# dt.net
KiCad netlist of a schematic drawn in EAGLE
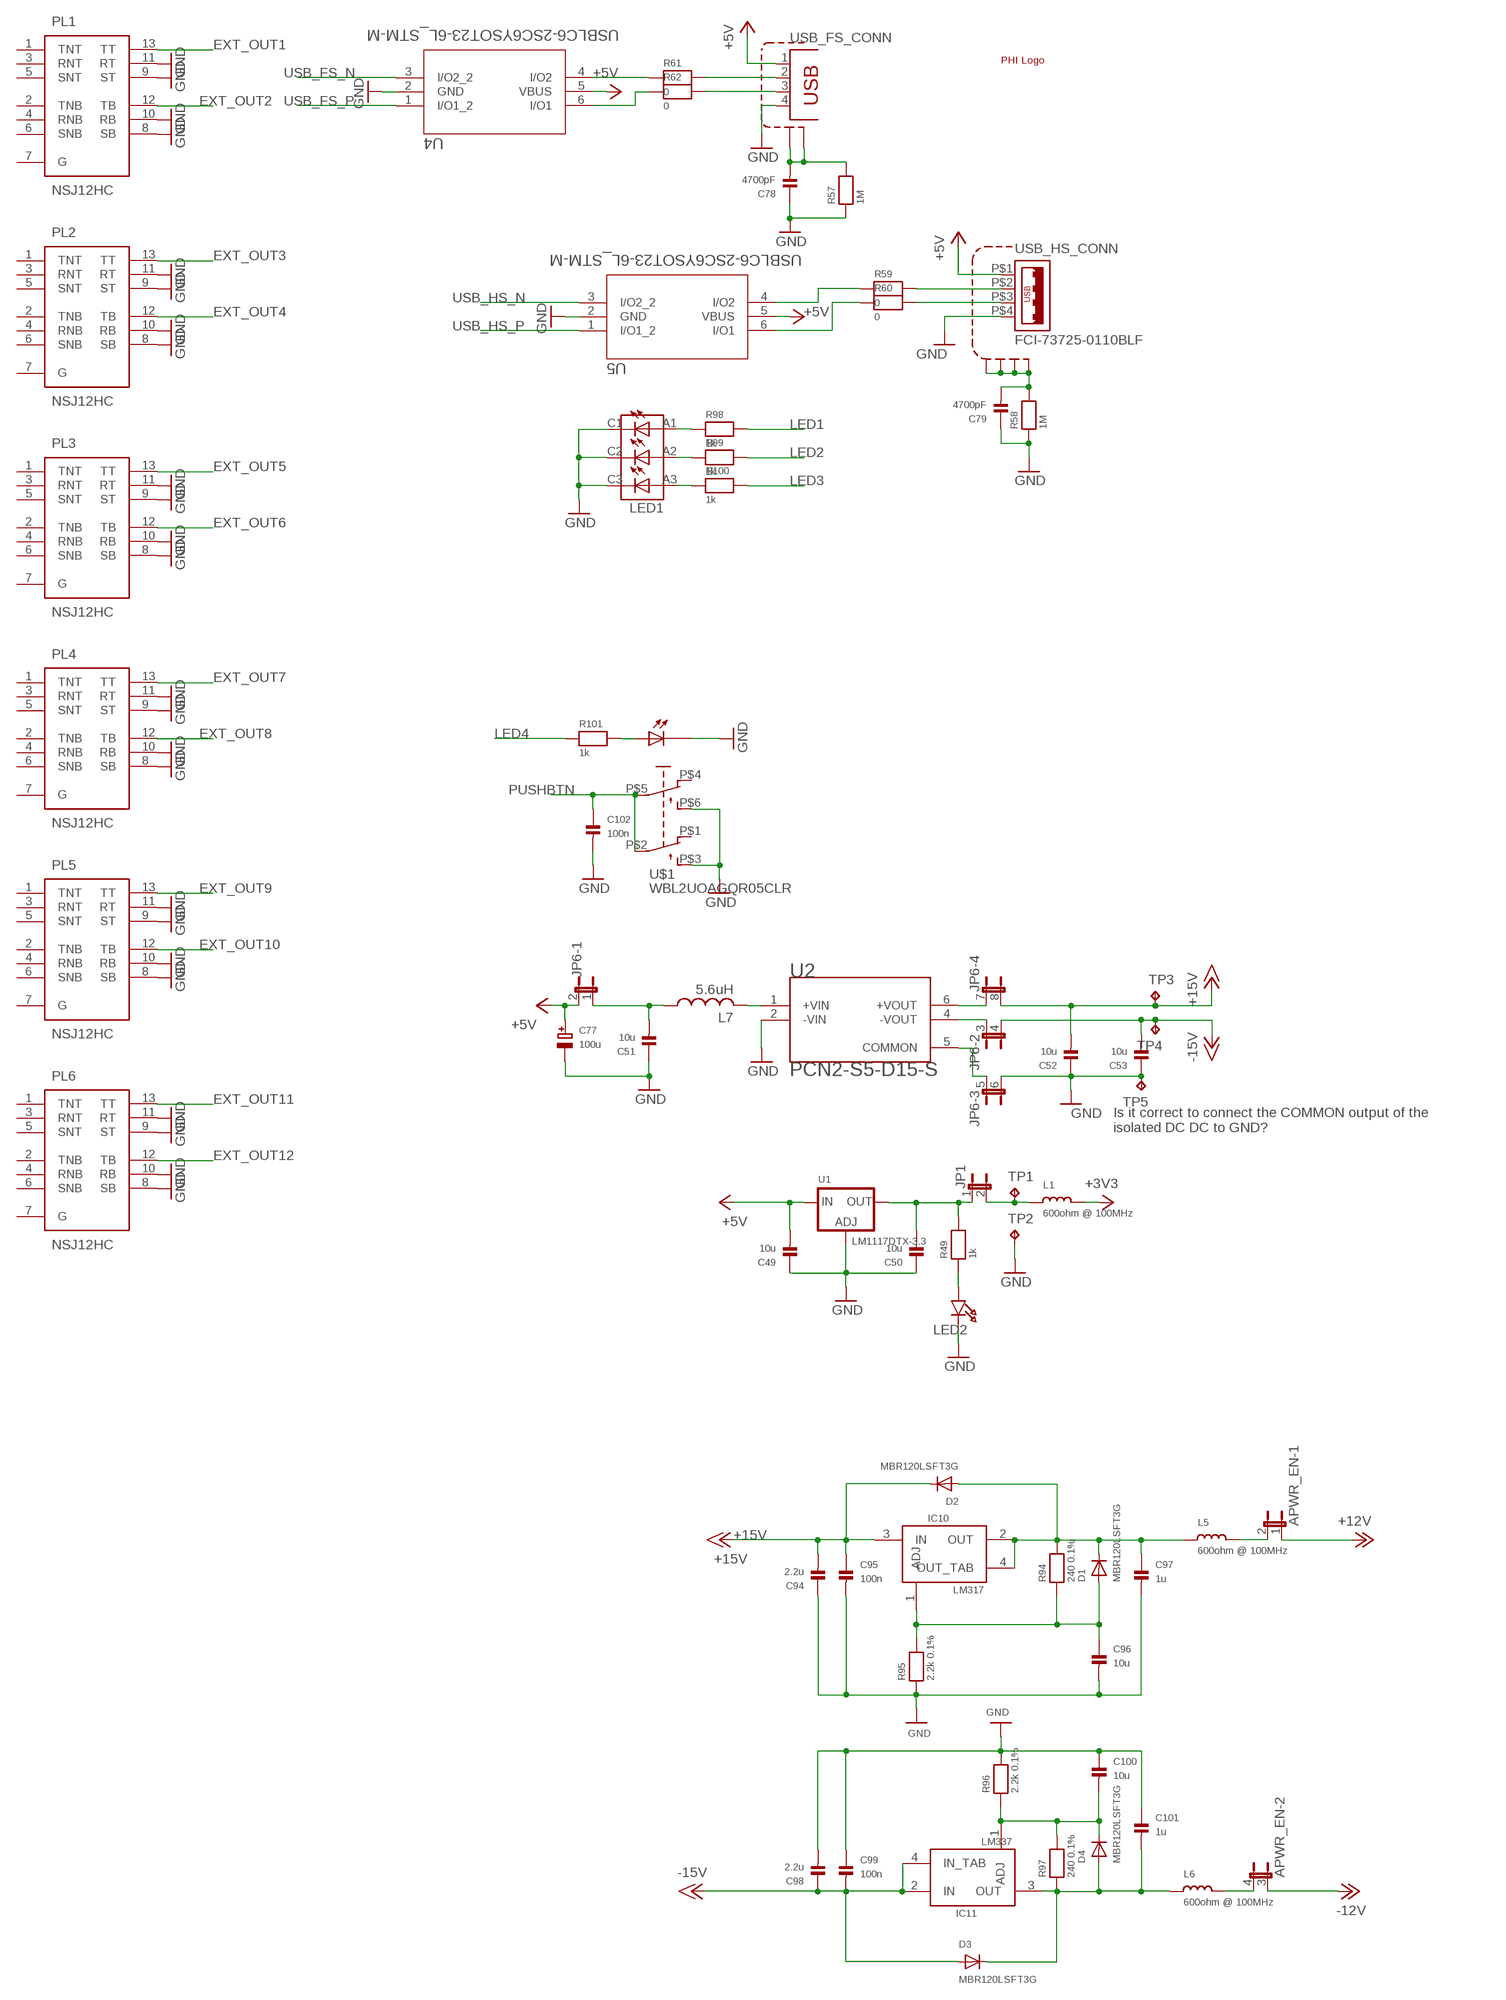
[diagram p0: schematic, sheet 1]
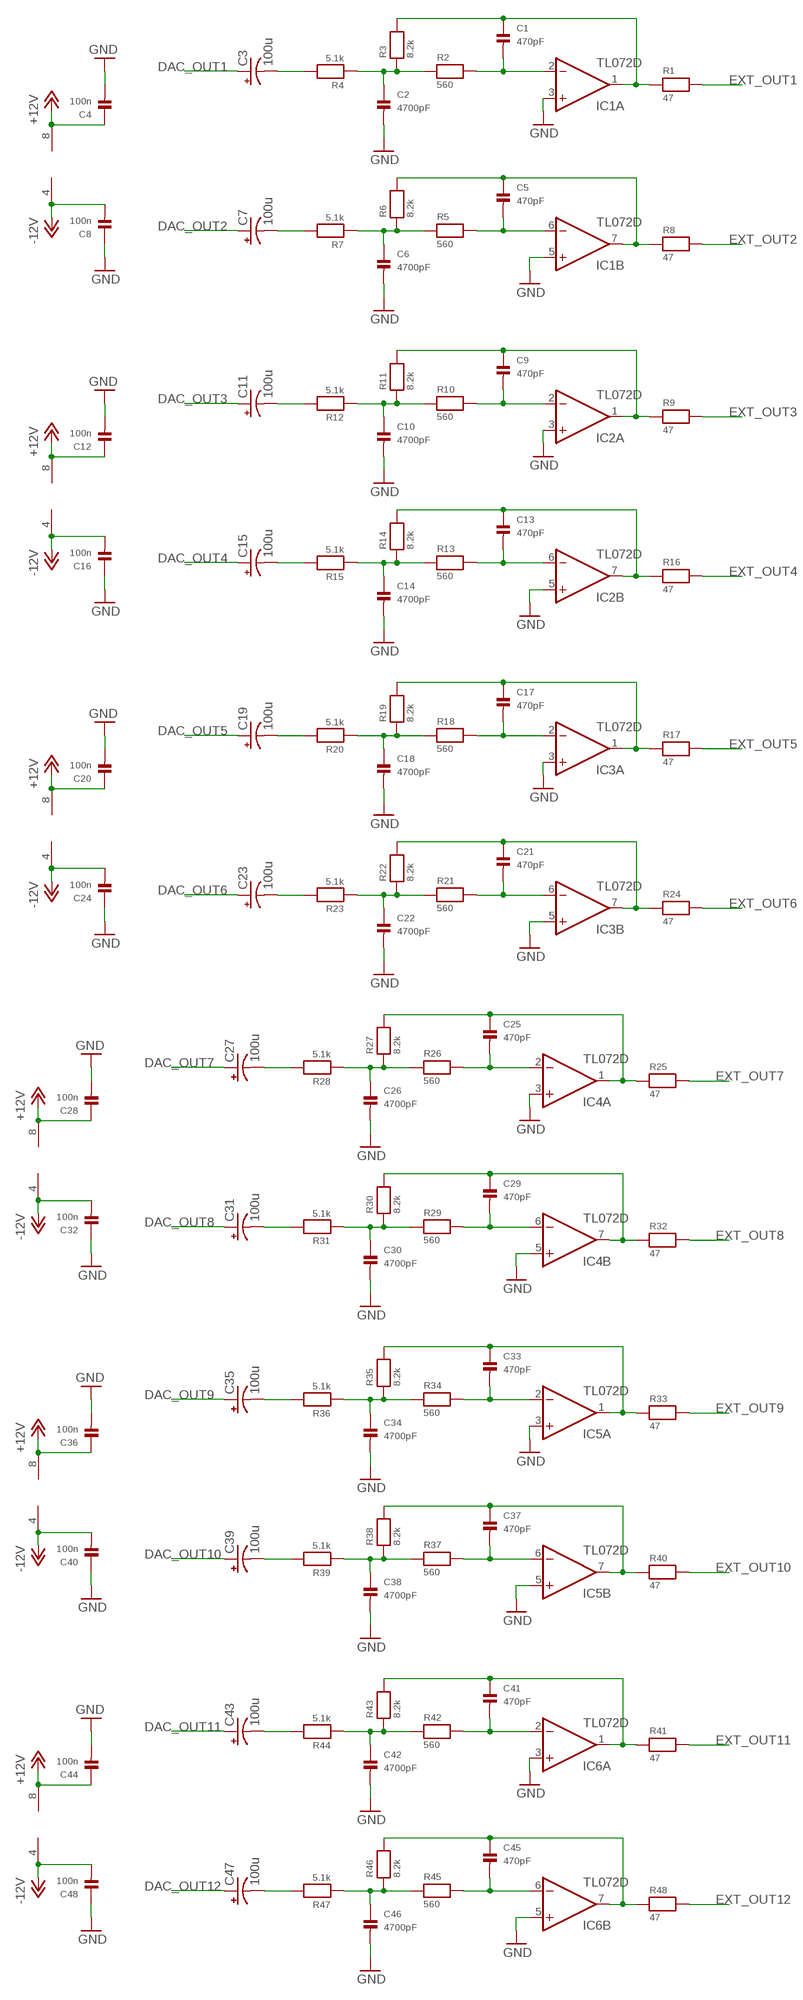
[diagram p1: schematic, sheet 2]
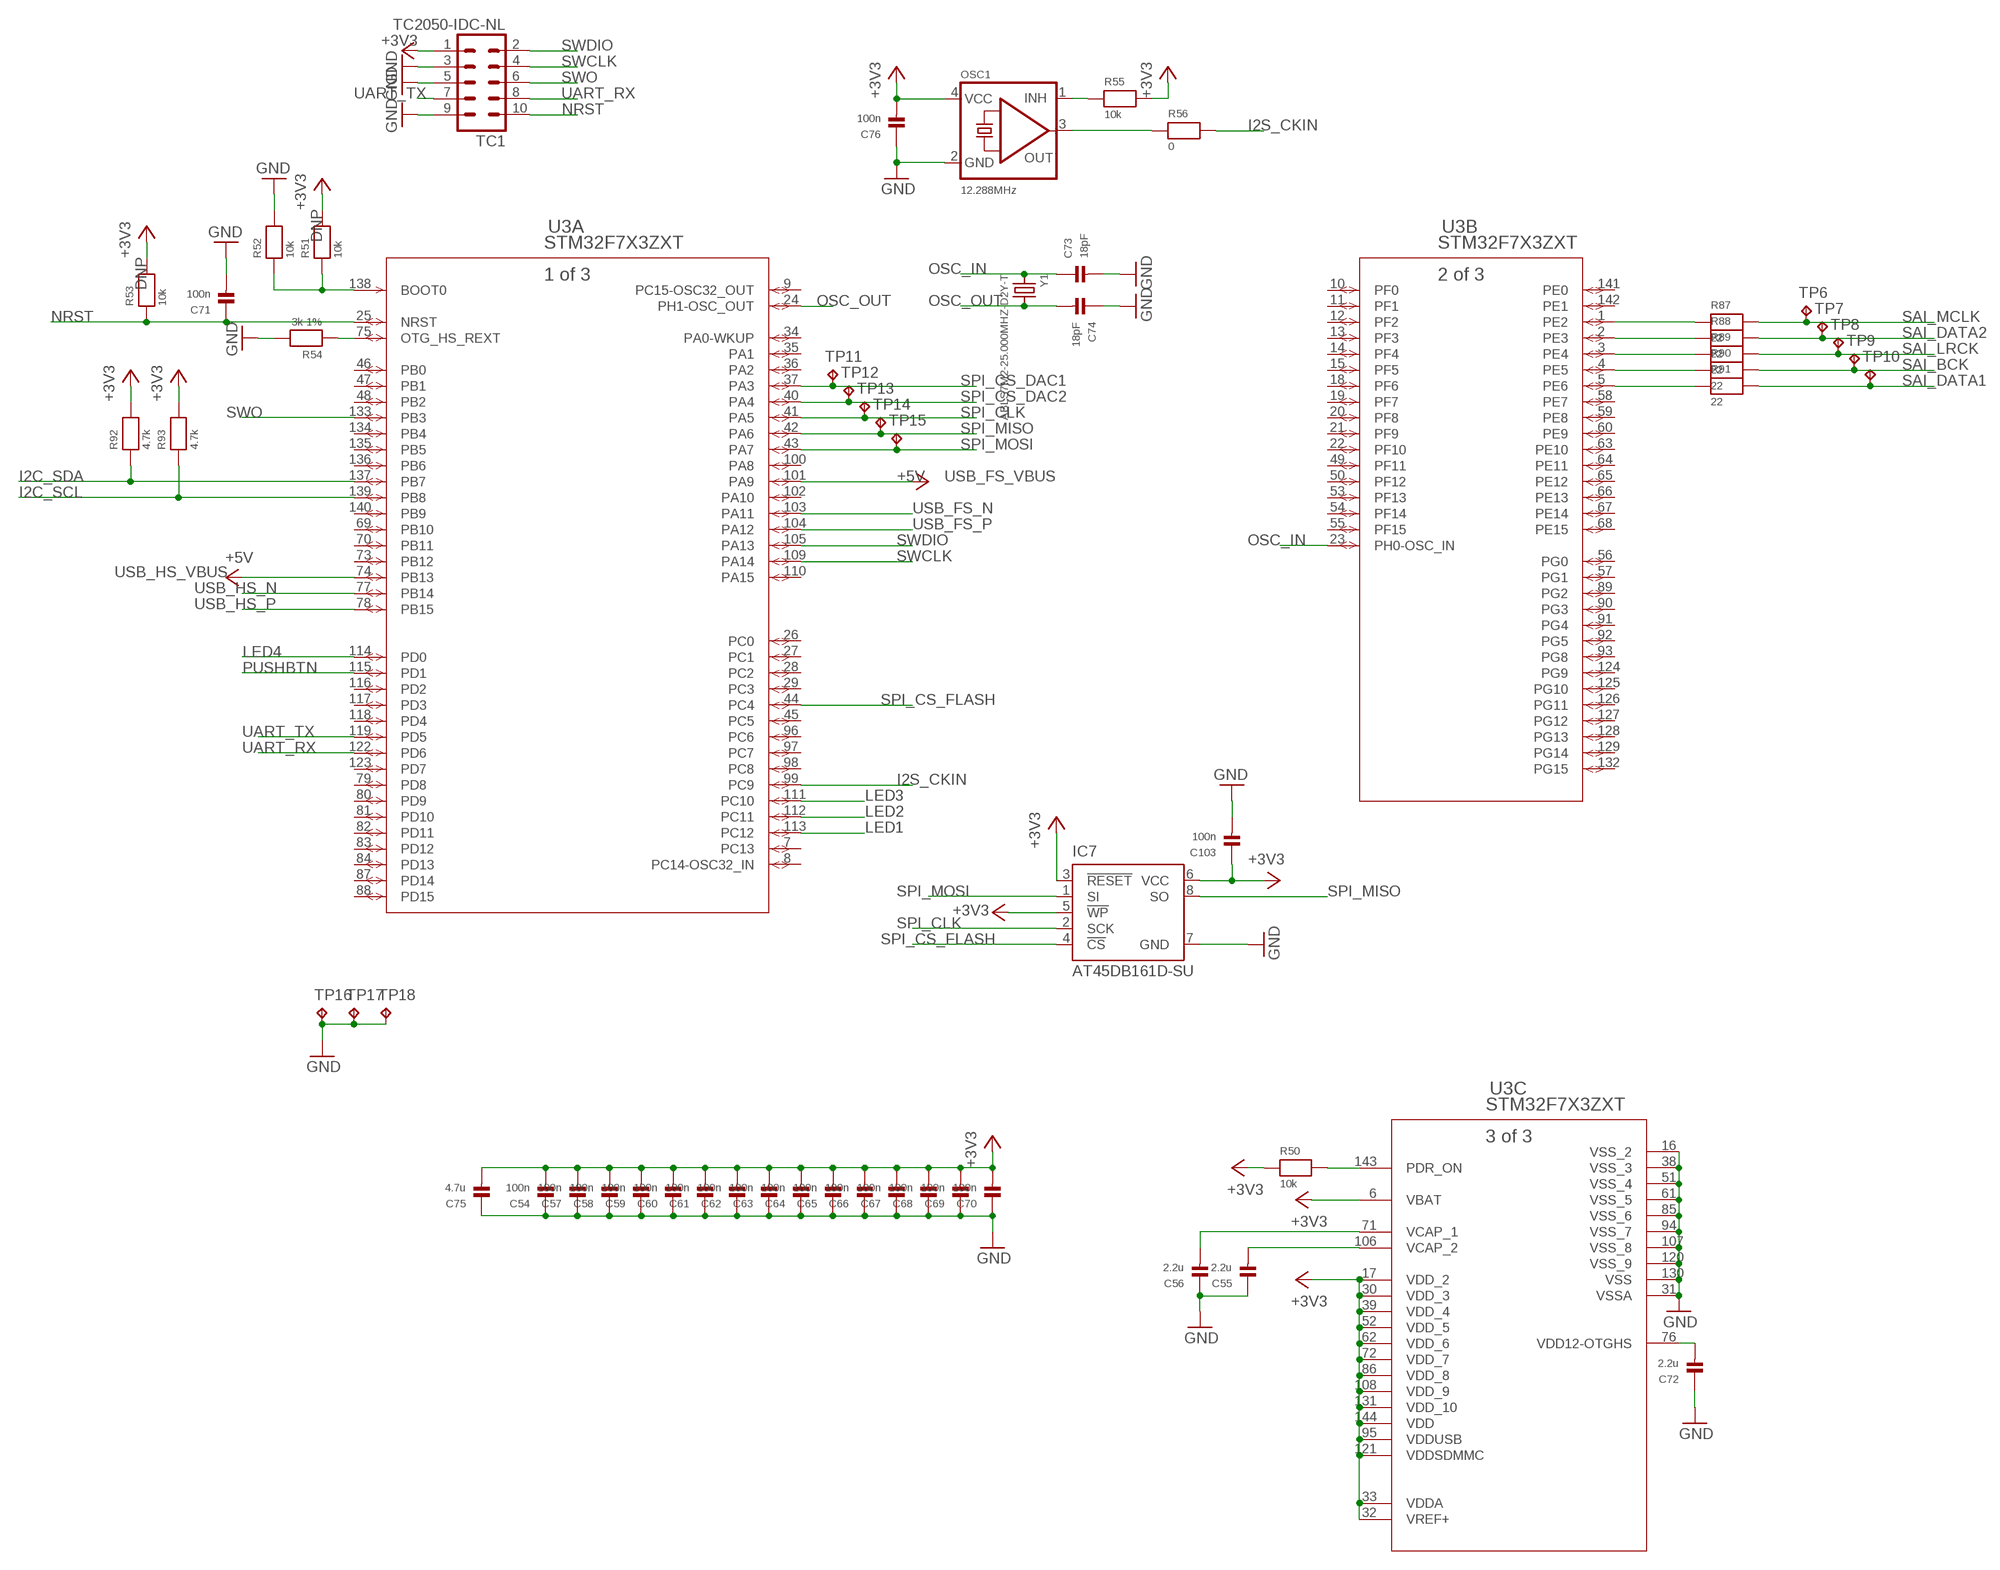
[diagram p2: schematic, sheet 3]
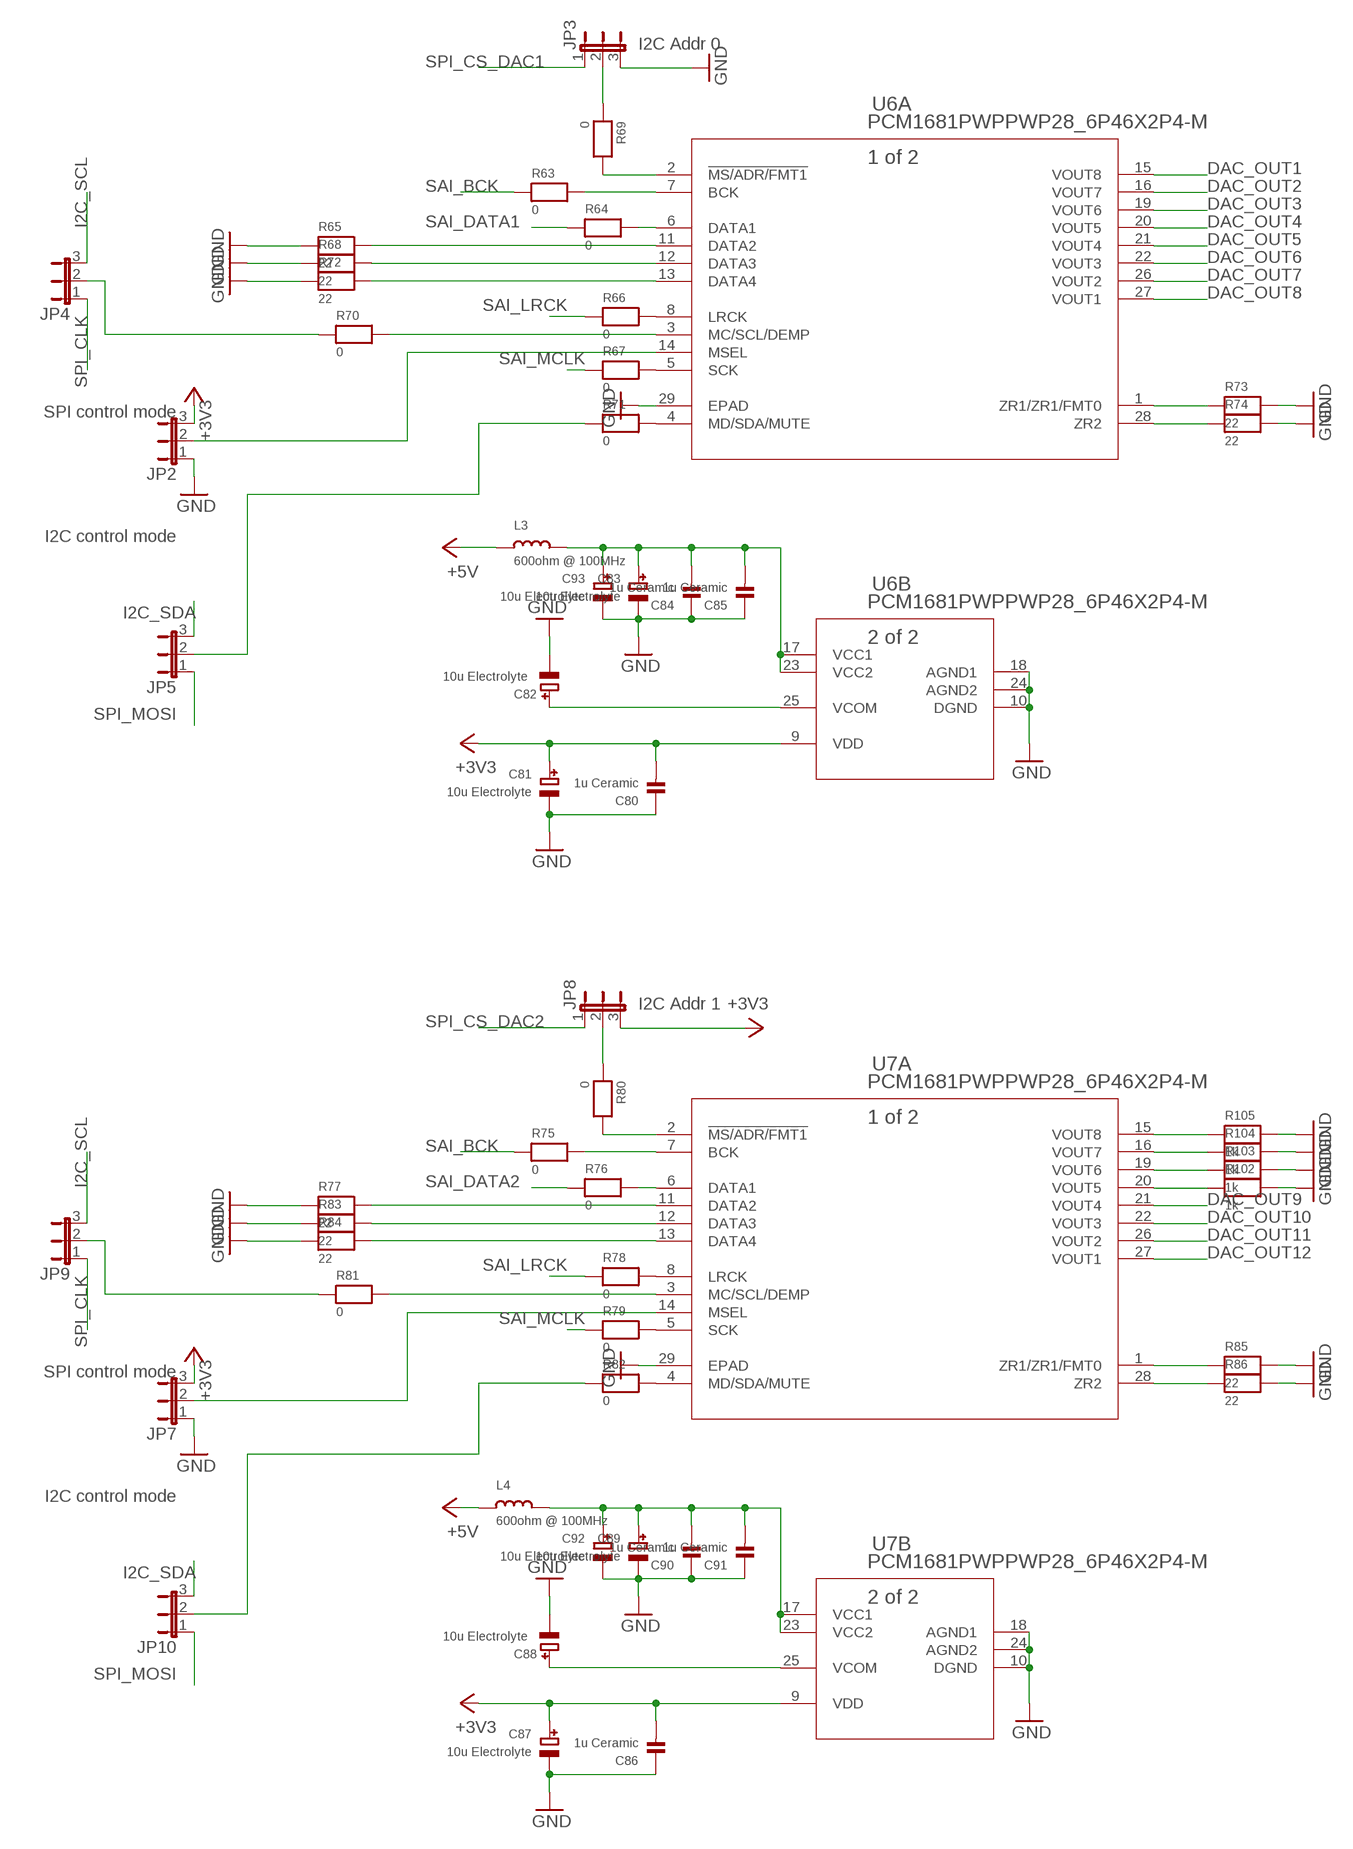
[diagram p3: schematic, sheet 4]

(export (version "E")
  (design (tool "Eeschema 10.0.6"))
  (components
    (comp (ref "APWR_EN")
      (value "JP2QE")
      (footprint "eagle-import:JP2Q")
      (fields (field (name "PARTNO") "TSW-102-07-T-D"))
      (libsource (lib "eagle-import") (part "JP2QE"))
    )
    (comp (ref "C49")
      (value "10u")
      (footprint "eagle-import:0805")
      (fields (field (name "PARTNO") "CL21A106KAYNNNE"))
      (libsource (lib "eagle-import") (part "CAP_CERAMIC0805"))
    )
    (comp (ref "C50")
      (value "10u")
      (footprint "eagle-import:0805")
      (fields (field (name "PARTNO") "CL21A106KAYNNNE"))
      (libsource (lib "eagle-import") (part "CAP_CERAMIC0805"))
    )
    (comp (ref "C51")
      (value "10u")
      (footprint "eagle-import:0805")
      (fields (field (name "PARTNO") "CL21A106KAYNNNE"))
      (libsource (lib "eagle-import") (part "CAP_CERAMIC0805"))
    )
    (comp (ref "C52")
      (value "10u")
      (footprint "eagle-import:0805")
      (fields (field (name "PARTNO") "CL21A106KAYNNNE"))
      (libsource (lib "eagle-import") (part "CAP_CERAMIC0805"))
    )
    (comp (ref "C53")
      (value "10u")
      (footprint "eagle-import:0805")
      (fields (field (name "PARTNO") "CL21A106KAYNNNE"))
      (libsource (lib "eagle-import") (part "CAP_CERAMIC0805"))
    )
    (comp (ref "C77")
      (value "100u")
      (footprint "eagle-import:PANASONIC_D")
      (fields (field (name "PARTNO") "EEE-HAV101XAP"))
      (libsource (lib "eagle-import") (part "CAP_ELECTROLYTICPANASONIC_D"))
    )
    (comp (ref "C78")
      (value "4700pF")
      (footprint "eagle-import:0603")
      (fields (field (name "PARTNO") "GRM1885C1H472JA01D"))
      (libsource (lib "eagle-import") (part "CAP_CERAMIC0603"))
    )
    (comp (ref "C79")
      (value "4700pF")
      (footprint "eagle-import:0603")
      (fields (field (name "PARTNO") "GRM1885C1H472JA01D"))
      (libsource (lib "eagle-import") (part "CAP_CERAMIC0603"))
    )
    (comp (ref "C94")
      (value "2.2u")
      (footprint "eagle-import:0805")
      (fields (field (name "PARTNO") "UMK212BB7225KG-T"))
      (libsource (lib "eagle-import") (part "CAP_CERAMIC0805"))
    )
    (comp (ref "C95")
      (value "100n")
      (footprint "eagle-import:0603")
      (fields (field (name "PARTNO") "CC0603KRX7R9BB104"))
      (libsource (lib "eagle-import") (part "CAP_CERAMIC0603"))
    )
    (comp (ref "C96")
      (value "10u")
      (footprint "eagle-import:0805")
      (fields (field (name "PARTNO") "CL21A106KAYNNNE"))
      (libsource (lib "eagle-import") (part "CAP_CERAMIC0805"))
    )
    (comp (ref "C97")
      (value "1u")
      (footprint "eagle-import:1206")
      (fields (field (name "PARTNO") "12065C105M4Z2A"))
      (libsource (lib "eagle-import") (part "CAP_CERAMIC1206"))
    )
    (comp (ref "C98")
      (value "2.2u")
      (footprint "eagle-import:0805")
      (fields (field (name "PARTNO") "UMK212BB7225KG-T"))
      (libsource (lib "eagle-import") (part "CAP_CERAMIC0805"))
    )
    (comp (ref "C99")
      (value "100n")
      (footprint "eagle-import:0603")
      (fields (field (name "PARTNO") "CC0603KRX7R9BB104"))
      (libsource (lib "eagle-import") (part "CAP_CERAMIC0603"))
    )
    (comp (ref "C100")
      (value "10u")
      (footprint "eagle-import:0805")
      (fields (field (name "PARTNO") "CL21A106KAYNNNE"))
      (libsource (lib "eagle-import") (part "CAP_CERAMIC0805"))
    )
    (comp (ref "C101")
      (value "1u")
      (footprint "eagle-import:1206")
      (fields (field (name "PARTNO") "12065C105M4Z2A"))
      (libsource (lib "eagle-import") (part "CAP_CERAMIC1206"))
    )
    (comp (ref "C102")
      (value "100n")
      (footprint "eagle-import:0603")
      (fields (field (name "PARTNO") "CC0603KRX7R9BB104"))
      (libsource (lib "eagle-import") (part "CAP_CERAMIC0603"))
    )
    (comp (ref "D1")
      (value "MBR120LSFT3G")
      (footprint "eagle-import:SOD-123")
      (libsource (lib "eagle-import") (part "DIODESOD-123"))
    )
    (comp (ref "D2")
      (value "MBR120LSFT3G")
      (footprint "eagle-import:SOD-123")
      (libsource (lib "eagle-import") (part "DIODESOD-123"))
    )
    (comp (ref "D3")
      (value "MBR120LSFT3G")
      (footprint "eagle-import:SOD-123")
      (libsource (lib "eagle-import") (part "DIODESOD-123"))
    )
    (comp (ref "D4")
      (value "MBR120LSFT3G")
      (footprint "eagle-import:SOD-123")
      (libsource (lib "eagle-import") (part "DIODESOD-123"))
    )
    (comp (ref "IC10")
      (value "LM317")
      (footprint "eagle-import:SOT223")
      (fields (field (name "PARTNO") "LM317MBSTT3G"))
      (libsource (lib "eagle-import") (part "LM317"))
    )
    (comp (ref "IC11")
      (value "LM337")
      (footprint "eagle-import:SOT223")
      (fields (field (name "PARTNO") "LM337IMPX/NOPB"))
      (libsource (lib "eagle-import") (part "LM337"))
    )
    (comp (ref "JP1")
      (value "JP1E")
      (footprint "eagle-import:JP1")
      (fields (field (name "PARTNO") "G800W306018EU"))
      (libsource (lib "eagle-import") (part "JP1E"))
    )
    (comp (ref "JP6")
      (value "JP4QE")
      (footprint "eagle-import:JP4Q")
      (fields (field (name "PARTNO") "M20-9760446"))
      (libsource (lib "eagle-import") (part "JP4QE"))
    )
    (comp (ref "L1")
      (value "600ohm @ 100MHz")
      (footprint "eagle-import:0603")
      (fields (field (name "PARTNO") "BLM18KG601SN1D"))
      (libsource (lib "eagle-import") (part "INDUCTOR0603"))
    )
    (comp (ref "L5")
      (value "600ohm @ 100MHz")
      (footprint "eagle-import:0603")
      (fields (field (name "PARTNO") "BLM18KG601SN1D"))
      (libsource (lib "eagle-import") (part "INDUCTOR0603"))
    )
    (comp (ref "L6")
      (value "600ohm @ 100MHz")
      (footprint "eagle-import:0603")
      (fields (field (name "PARTNO") "BLM18KG601SN1D"))
      (libsource (lib "eagle-import") (part "INDUCTOR0603"))
    )
    (comp (ref "L7")
      (value "5.6uH")
      (footprint "eagle-import:L1812")
      (fields (field (name "PARTNO") "PM1812-5R6J-RC"))
      (libsource (lib "eagle-import") (part "L-USL1812"))
    )
    (comp (ref "LED1")
      (value "WP934SA_LILYLGDLED")
      (footprint "eagle-import:WP934SALILYLGD")
      (fields (field (name "PARTNO") "WP934SA/LILYLGD"))
      (libsource (lib "eagle-import") (part "WP934SA_LILYLGDLED"))
    )
    (comp (ref "LED2")
      (value "LED0805")
      (footprint "eagle-import:CHIPLED_0805")
      (fields (field (name "PARTNO") "AP2012HD"))
      (libsource (lib "eagle-import") (part "LED0805"))
    )
    (comp (ref "PL1")
      (value "NSJ12HC")
      (footprint "eagle-import:NSJ12HF1")
      (fields
        (field (name "MANUFACTURER_PART_NUMBER") "NSJ12HF-1")
        (field (name "MOUSER_PART_NUMBER") "568-NSJ12HF-1")
      )
      (libsource (lib "eagle-import") (part "NSJ12HF-1"))
    )
    (comp (ref "PL2")
      (value "NSJ12HC")
      (footprint "eagle-import:NSJ12HF1")
      (fields
        (field (name "MANUFACTURER_PART_NUMBER") "NSJ12HF-1")
        (field (name "MOUSER_PART_NUMBER") "568-NSJ12HF-1")
      )
      (libsource (lib "eagle-import") (part "NSJ12HF-1"))
    )
    (comp (ref "PL3")
      (value "NSJ12HC")
      (footprint "eagle-import:NSJ12HF1")
      (fields
        (field (name "MANUFACTURER_PART_NUMBER") "NSJ12HF-1")
        (field (name "MOUSER_PART_NUMBER") "568-NSJ12HF-1")
      )
      (libsource (lib "eagle-import") (part "NSJ12HF-1"))
    )
    (comp (ref "PL4")
      (value "NSJ12HC")
      (footprint "eagle-import:NSJ12HF1")
      (fields
        (field (name "MANUFACTURER_PART_NUMBER") "NSJ12HF-1")
        (field (name "MOUSER_PART_NUMBER") "568-NSJ12HF-1")
      )
      (libsource (lib "eagle-import") (part "NSJ12HF-1"))
    )
    (comp (ref "PL5")
      (value "NSJ12HC")
      (footprint "eagle-import:NSJ12HF1")
      (fields
        (field (name "MANUFACTURER_PART_NUMBER") "NSJ12HF-1")
        (field (name "MOUSER_PART_NUMBER") "568-NSJ12HF-1")
      )
      (libsource (lib "eagle-import") (part "NSJ12HF-1"))
    )
    (comp (ref "PL6")
      (value "NSJ12HC")
      (footprint "eagle-import:NSJ12HF1")
      (fields
        (field (name "MANUFACTURER_PART_NUMBER") "NSJ12HF-1")
        (field (name "MOUSER_PART_NUMBER") "568-NSJ12HF-1")
      )
      (libsource (lib "eagle-import") (part "NSJ12HF-1"))
    )
    (comp (ref "R49")
      (value "1k")
      (footprint "eagle-import:0603")
      (fields (field (name "PARTNO") "CRCW06031K00FKEAC"))
      (libsource (lib "eagle-import") (part "RESISTOR0603"))
    )
    (comp (ref "R57")
      (value "1M")
      (footprint "eagle-import:0603")
      (fields (field (name "PARTNO") "AC0603FR-131ML"))
      (libsource (lib "eagle-import") (part "RESISTOR0603"))
    )
    (comp (ref "R58")
      (value "1M")
      (footprint "eagle-import:0603")
      (fields (field (name "PARTNO") "AC0603FR-131ML"))
      (libsource (lib "eagle-import") (part "RESISTOR0603"))
    )
    (comp (ref "R59")
      (value "0")
      (footprint "eagle-import:0603")
      (fields (field (name "PARTNO") "CRCW06030000Z0EBC"))
      (libsource (lib "eagle-import") (part "RESISTOR0603"))
    )
    (comp (ref "R60")
      (value "0")
      (footprint "eagle-import:0603")
      (fields (field (name "PARTNO") "CRCW06030000Z0EBC"))
      (libsource (lib "eagle-import") (part "RESISTOR0603"))
    )
    (comp (ref "R61")
      (value "0")
      (footprint "eagle-import:0603")
      (fields (field (name "PARTNO") "CRCW06030000Z0EBC"))
      (libsource (lib "eagle-import") (part "RESISTOR0603"))
    )
    (comp (ref "R62")
      (value "0")
      (footprint "eagle-import:0603")
      (fields (field (name "PARTNO") "CRCW06030000Z0EBC"))
      (libsource (lib "eagle-import") (part "RESISTOR0603"))
    )
    (comp (ref "R94")
      (value "240 0.1%")
      (footprint "eagle-import:0603")
      (fields (field (name "PARTNO") "ERA-3AEB241V"))
      (libsource (lib "eagle-import") (part "RESISTOR0603"))
    )
    (comp (ref "R95")
      (value "2.2k 0.1%")
      (footprint "eagle-import:0603")
      (fields (field (name "PARTNO") "ERA-3VEB2201V"))
      (libsource (lib "eagle-import") (part "RESISTOR0603"))
    )
    (comp (ref "R96")
      (value "2.2k 0.1%")
      (footprint "eagle-import:0603")
      (fields (field (name "PARTNO") "ERA-3VEB2201V"))
      (libsource (lib "eagle-import") (part "RESISTOR0603"))
    )
    (comp (ref "R97")
      (value "240 0.1%")
      (footprint "eagle-import:0603")
      (fields (field (name "PARTNO") "ERA-3AEB241V"))
      (libsource (lib "eagle-import") (part "RESISTOR0603"))
    )
    (comp (ref "R98")
      (value "1k")
      (footprint "eagle-import:0603")
      (fields (field (name "PARTNO") "CRCW06031K00FKEAC"))
      (libsource (lib "eagle-import") (part "RESISTOR0603"))
    )
    (comp (ref "R99")
      (value "1k")
      (footprint "eagle-import:0603")
      (fields (field (name "PARTNO") "CRCW06031K00FKEAC"))
      (libsource (lib "eagle-import") (part "RESISTOR0603"))
    )
    (comp (ref "R100")
      (value "1k")
      (footprint "eagle-import:0603")
      (fields (field (name "PARTNO") "CRCW06031K00FKEAC"))
      (libsource (lib "eagle-import") (part "RESISTOR0603"))
    )
    (comp (ref "R101")
      (value "1k")
      (footprint "eagle-import:0603")
      (fields (field (name "PARTNO") "CRCW06031K00FKEAC"))
      (libsource (lib "eagle-import") (part "RESISTOR0603"))
    )
    (comp (ref "TP1")
      (value "TPPAD1-13")
      (footprint "eagle-import:P1-13")
      (fields (field (name "PARTNO") "5001"))
      (libsource (lib "eagle-import") (part "TPPAD1-13"))
    )
    (comp (ref "TP2")
      (value "TPPAD1-13")
      (footprint "eagle-import:P1-13")
      (fields (field (name "PARTNO") "5001"))
      (libsource (lib "eagle-import") (part "TPPAD1-13"))
    )
    (comp (ref "TP3")
      (value "TPPAD1-13")
      (footprint "eagle-import:P1-13")
      (fields (field (name "PARTNO") "5001"))
      (libsource (lib "eagle-import") (part "TPPAD1-13"))
    )
    (comp (ref "TP4")
      (value "TPPAD1-13")
      (footprint "eagle-import:P1-13")
      (fields (field (name "PARTNO") "5001"))
      (libsource (lib "eagle-import") (part "TPPAD1-13"))
    )
    (comp (ref "TP5")
      (value "TPPAD1-13")
      (footprint "eagle-import:P1-13")
      (fields (field (name "PARTNO") "5001"))
      (libsource (lib "eagle-import") (part "TPPAD1-13"))
    )
    (comp (ref "U$1")
      (value "WBL2UOAGQR05CLR")
      (footprint "eagle-import:WBL2UOAGQ")
      (libsource (lib "eagle-import") (part "WBL2UOAGQR05CLR"))
    )
    (comp (ref "U$2")
      (value "PHI-LOGO")
      (footprint "eagle-import:PHI-LOGO")
      (libsource (lib "eagle-import") (part "PHI-LOGO"))
    )
    (comp (ref "U1")
      (value "LM1117DTX-3.3")
      (footprint "eagle-import:TO252")
      (fields (field (name "PARTNO") "LM1117DTX-3.3/NOPB"))
      (libsource (lib "eagle-import") (part "LM1117TO252"))
    )
    (comp (ref "U2")
      (value "PCN2-S5-D15-S")
      (footprint "eagle-import:CONV_PCN2-S5-D12-S")
      (fields (field (name "MANUFACTURER") "CUI INC"))
      (libsource (lib "eagle-import") (part "PCN2-S5-D12-S"))
    )
    (comp (ref "U4")
      (value "USBLC6-2SC6YSOT23-6L_STM-M")
      (footprint "eagle-import:SOT23-6L_STM-M")
      (fields (field (name "MANUFACTURER_PART_NUMBER") "USBLC6-2SC6Y"))
      (libsource (lib "eagle-import") (part "USBLC6-2SC6YSOT23-6L_STM-M"))
    )
    (comp (ref "U5")
      (value "USBLC6-2SC6YSOT23-6L_STM-M")
      (footprint "eagle-import:SOT23-6L_STM-M")
      (fields (field (name "MANUFACTURER_PART_NUMBER") "USBLC6-2SC6Y"))
      (libsource (lib "eagle-import") (part "USBLC6-2SC6YSOT23-6L_STM-M"))
    )
    (comp (ref "USB_FS")
      (value "TE-292304-1")
      (footprint "eagle-import:TE-292304-1")
      (fields (field (name "MPN") "292304-1 ") (field (name "PARTNO") "292304-1"))
      (libsource (lib "eagle-import") (part "TE-292304-1"))
    )
    (comp (ref "USB_HS")
      (value "FCI-73725-0110BLF")
      (footprint "eagle-import:FCI-73725-0110BLF")
      (fields (field (name "PARTNO") "73725-0110BLF"))
      (libsource (lib "eagle-import") (part "FCI-73725-0110BLF"))
    )
    (comp (ref "C54")
      (value "100n")
      (footprint "eagle-import:0603")
      (fields (field (name "PARTNO") "CC0603KRX7R9BB104"))
      (libsource (lib "eagle-import") (part "CAP_CERAMIC0603"))
    )
    (comp (ref "C55")
      (value "2.2u")
      (footprint "eagle-import:1206")
      (fields (field (name "PARTNO") "CL31B225KBHNNNE"))
      (libsource (lib "eagle-import") (part "CAP_CERAMIC1206"))
    )
    (comp (ref "C56")
      (value "2.2u")
      (footprint "eagle-import:1206")
      (fields (field (name "PARTNO") "CL31B225KBHNNNE"))
      (libsource (lib "eagle-import") (part "CAP_CERAMIC1206"))
    )
    (comp (ref "C57")
      (value "100n")
      (footprint "eagle-import:0603")
      (fields (field (name "PARTNO") "CC0603KRX7R9BB104"))
      (libsource (lib "eagle-import") (part "CAP_CERAMIC0603"))
    )
    (comp (ref "C58")
      (value "100n")
      (footprint "eagle-import:0603")
      (fields (field (name "PARTNO") "CC0603KRX7R9BB104"))
      (libsource (lib "eagle-import") (part "CAP_CERAMIC0603"))
    )
    (comp (ref "C59")
      (value "100n")
      (footprint "eagle-import:0603")
      (fields (field (name "PARTNO") "CC0603KRX7R9BB104"))
      (libsource (lib "eagle-import") (part "CAP_CERAMIC0603"))
    )
    (comp (ref "C60")
      (value "100n")
      (footprint "eagle-import:0603")
      (fields (field (name "PARTNO") "CC0603KRX7R9BB104"))
      (libsource (lib "eagle-import") (part "CAP_CERAMIC0603"))
    )
    (comp (ref "C61")
      (value "100n")
      (footprint "eagle-import:0603")
      (fields (field (name "PARTNO") "CC0603KRX7R9BB104"))
      (libsource (lib "eagle-import") (part "CAP_CERAMIC0603"))
    )
    (comp (ref "C62")
      (value "100n")
      (footprint "eagle-import:0603")
      (fields (field (name "PARTNO") "CC0603KRX7R9BB104"))
      (libsource (lib "eagle-import") (part "CAP_CERAMIC0603"))
    )
    (comp (ref "C63")
      (value "100n")
      (footprint "eagle-import:0603")
      (fields (field (name "PARTNO") "CC0603KRX7R9BB104"))
      (libsource (lib "eagle-import") (part "CAP_CERAMIC0603"))
    )
    (comp (ref "C64")
      (value "100n")
      (footprint "eagle-import:0603")
      (fields (field (name "PARTNO") "CC0603KRX7R9BB104"))
      (libsource (lib "eagle-import") (part "CAP_CERAMIC0603"))
    )
    (comp (ref "C65")
      (value "100n")
      (footprint "eagle-import:0603")
      (fields (field (name "PARTNO") "CC0603KRX7R9BB104"))
      (libsource (lib "eagle-import") (part "CAP_CERAMIC0603"))
    )
    (comp (ref "C66")
      (value "100n")
      (footprint "eagle-import:0603")
      (fields (field (name "PARTNO") "CC0603KRX7R9BB104"))
      (libsource (lib "eagle-import") (part "CAP_CERAMIC0603"))
    )
    (comp (ref "C67")
      (value "100n")
      (footprint "eagle-import:0603")
      (fields (field (name "PARTNO") "CC0603KRX7R9BB104"))
      (libsource (lib "eagle-import") (part "CAP_CERAMIC0603"))
    )
    (comp (ref "C68")
      (value "100n")
      (footprint "eagle-import:0603")
      (fields (field (name "PARTNO") "CC0603KRX7R9BB104"))
      (libsource (lib "eagle-import") (part "CAP_CERAMIC0603"))
    )
    (comp (ref "C69")
      (value "100n")
      (footprint "eagle-import:0603")
      (fields (field (name "PARTNO") "CC0603KRX7R9BB104"))
      (libsource (lib "eagle-import") (part "CAP_CERAMIC0603"))
    )
    (comp (ref "C70")
      (value "100n")
      (footprint "eagle-import:0603")
      (fields (field (name "PARTNO") "CC0603KRX7R9BB104"))
      (libsource (lib "eagle-import") (part "CAP_CERAMIC0603"))
    )
    (comp (ref "C71")
      (value "100n")
      (footprint "eagle-import:0603")
      (fields (field (name "PARTNO") "CC0603KRX7R9BB104"))
      (libsource (lib "eagle-import") (part "CAP_CERAMIC0603"))
    )
    (comp (ref "C72")
      (value "2.2u")
      (footprint "eagle-import:1206")
      (fields (field (name "PARTNO") "CL31B225KBHNNNE"))
      (libsource (lib "eagle-import") (part "CAP_CERAMIC1206"))
    )
    (comp (ref "C73")
      (value "18pF")
      (footprint "eagle-import:0603")
      (fields (field (name "PARTNO") "06035A180JAT2A"))
      (libsource (lib "eagle-import") (part "CAP_CERAMIC0603"))
    )
    (comp (ref "C74")
      (value "18pF")
      (footprint "eagle-import:0603")
      (fields (field (name "PARTNO") "06035A180JAT2A"))
      (libsource (lib "eagle-import") (part "CAP_CERAMIC0603"))
    )
    (comp (ref "C75")
      (value "4.7u")
      (footprint "eagle-import:0603")
      (fields (field (name "PARTNO") "GRM188Z71A475ME15D"))
      (libsource (lib "eagle-import") (part "CAP_CERAMIC0603"))
    )
    (comp (ref "C76")
      (value "100n")
      (footprint "eagle-import:0603")
      (fields (field (name "PARTNO") "CC0603KRX7R9BB104"))
      (libsource (lib "eagle-import") (part "CAP_CERAMIC0603"))
    )
    (comp (ref "C103")
      (value "100n")
      (footprint "eagle-import:0603")
      (fields (field (name "PARTNO") "CC0603KRX7R9BB104"))
      (libsource (lib "eagle-import") (part "CAP_CERAMIC0603"))
    )
    (comp (ref "IC7")
      (value "AT45DB161D-SU")
      (footprint "eagle-import:SOIC8")
      (fields (field (name "MF") "ATMEL"))
      (libsource (lib "eagle-import") (part "AT45DB161D-SU"))
    )
    (comp (ref "OSC1")
      (value "12.288MHz")
      (footprint "eagle-import:OSC_7X5MM")
      (fields (field (name "PARTNO") "C3391-12.288"))
      (libsource (lib "eagle-import") (part "OSCILLATOR"))
    )
    (comp (ref "R50")
      (value "10k")
      (footprint "eagle-import:0603")
      (fields (field (name "PARTNO") "CRCW060310K0JNEBC"))
      (libsource (lib "eagle-import") (part "RESISTOR0603"))
    )
    (comp (ref "R51")
      (value "10k")
      (footprint "eagle-import:0603")
      (fields (field (name "PARTNO") "CRCW060310K0JNEBC"))
      (libsource (lib "eagle-import") (part "RESISTOR0603"))
    )
    (comp (ref "R52")
      (value "10k")
      (footprint "eagle-import:0603")
      (fields (field (name "PARTNO") "CRCW060310K0JNEBC"))
      (libsource (lib "eagle-import") (part "RESISTOR0603"))
    )
    (comp (ref "R53")
      (value "10k")
      (footprint "eagle-import:0603")
      (fields (field (name "PARTNO") "CRCW060310K0JNEBC"))
      (libsource (lib "eagle-import") (part "RESISTOR0603"))
    )
    (comp (ref "R54")
      (value "3k 1%")
      (footprint "eagle-import:0603")
      (fields (field (name "PARTNO") "AF0603FR-073KL"))
      (libsource (lib "eagle-import") (part "RESISTOR0603"))
    )
    (comp (ref "R55")
      (value "10k")
      (footprint "eagle-import:0603")
      (fields (field (name "PARTNO") "CRCW060310K0JNEBC"))
      (libsource (lib "eagle-import") (part "RESISTOR0603"))
    )
    (comp (ref "R56")
      (value "0")
      (footprint "eagle-import:0603")
      (fields (field (name "PARTNO") "CRCW06030000Z0EBC"))
      (libsource (lib "eagle-import") (part "RESISTOR0603"))
    )
    (comp (ref "R87")
      (value "22")
      (footprint "eagle-import:0603")
      (fields (field (name "PARTNO") "CRCW060322R0FKEAC"))
      (libsource (lib "eagle-import") (part "RESISTOR0603"))
    )
    (comp (ref "R88")
      (value "22")
      (footprint "eagle-import:0603")
      (fields (field (name "PARTNO") "CRCW060322R0FKEAC"))
      (libsource (lib "eagle-import") (part "RESISTOR0603"))
    )
    (comp (ref "R89")
      (value "22")
      (footprint "eagle-import:0603")
      (fields (field (name "PARTNO") "CRCW060322R0FKEAC"))
      (libsource (lib "eagle-import") (part "RESISTOR0603"))
    )
    (comp (ref "R90")
      (value "22")
      (footprint "eagle-import:0603")
      (fields (field (name "PARTNO") "CRCW060322R0FKEAC"))
      (libsource (lib "eagle-import") (part "RESISTOR0603"))
    )
    (comp (ref "R91")
      (value "22")
      (footprint "eagle-import:0603")
      (fields (field (name "PARTNO") "CRCW060322R0FKEAC"))
      (libsource (lib "eagle-import") (part "RESISTOR0603"))
    )
    (comp (ref "R92")
      (value "4.7k")
      (footprint "eagle-import:0603")
      (fields (field (name "PARTNO") "CRCW06034K70FKEA"))
      (libsource (lib "eagle-import") (part "RESISTOR0603"))
    )
    (comp (ref "R93")
      (value "4.7k")
      (footprint "eagle-import:0603")
      (fields (field (name "PARTNO") "CRCW06034K70FKEA"))
      (libsource (lib "eagle-import") (part "RESISTOR0603"))
    )
    (comp (ref "TC1")
      (value "TC2050-IDC-NL")
      (footprint "eagle-import:TC2050-IDC-NL")
      (libsource (lib "eagle-import") (part "TC2050-IDC-NL"))
    )
    (comp (ref "TP6")
      (value "TPPAD1-13")
      (footprint "eagle-import:P1-13")
      (libsource (lib "eagle-import") (part "TPPAD1-13"))
    )
    (comp (ref "TP7")
      (value "TPPAD1-13")
      (footprint "eagle-import:P1-13")
      (libsource (lib "eagle-import") (part "TPPAD1-13"))
    )
    (comp (ref "TP8")
      (value "TPPAD1-13")
      (footprint "eagle-import:P1-13")
      (libsource (lib "eagle-import") (part "TPPAD1-13"))
    )
    (comp (ref "TP9")
      (value "TPPAD1-13")
      (footprint "eagle-import:P1-13")
      (libsource (lib "eagle-import") (part "TPPAD1-13"))
    )
    (comp (ref "TP10")
      (value "TPPAD1-13")
      (footprint "eagle-import:P1-13")
      (libsource (lib "eagle-import") (part "TPPAD1-13"))
    )
    (comp (ref "TP11")
      (value "TPPAD1-13")
      (footprint "eagle-import:P1-13")
      (libsource (lib "eagle-import") (part "TPPAD1-13"))
    )
    (comp (ref "TP12")
      (value "TPPAD1-13")
      (footprint "eagle-import:P1-13")
      (libsource (lib "eagle-import") (part "TPPAD1-13"))
    )
    (comp (ref "TP13")
      (value "TPPAD1-13")
      (footprint "eagle-import:P1-13")
      (libsource (lib "eagle-import") (part "TPPAD1-13"))
    )
    (comp (ref "TP14")
      (value "TPPAD1-13")
      (footprint "eagle-import:P1-13")
      (libsource (lib "eagle-import") (part "TPPAD1-13"))
    )
    (comp (ref "TP15")
      (value "TPPAD1-13")
      (footprint "eagle-import:P1-13")
      (libsource (lib "eagle-import") (part "TPPAD1-13"))
    )
    (comp (ref "TP16")
      (value "TPPAD1-13")
      (footprint "eagle-import:P1-13")
      (libsource (lib "eagle-import") (part "TPPAD1-13"))
    )
    (comp (ref "TP17")
      (value "TPPAD1-13")
      (footprint "eagle-import:P1-13")
      (libsource (lib "eagle-import") (part "TPPAD1-13"))
    )
    (comp (ref "TP18")
      (value "TPPAD1-13")
      (footprint "eagle-import:P1-13")
      (libsource (lib "eagle-import") (part "TPPAD1-13"))
    )
    (comp (ref "U3")
      (value "STM32F7X3ZXT")
      (footprint "eagle-import:LQFP144-20X20MM")
      (fields
        (field (name "PARTNO") "STM32F733ZET6")
        (field (name "COPYRIGHT") "Copyright (C) 2016 Accelerated Designs. All rights reserved")
      )
      (libsource (lib "eagle-import") (part "STM32F7X3ZXT"))
    )
    (comp (ref "Y1")
      (value "ABLS7M2-25.000MHZ-D2Y-T")
      (footprint "eagle-import:ABLS7M225000MHZD2YT")
      (libsource (lib "eagle-import") (part "CRYSTALABLS7M2"))
    )
    (comp (ref "C80")
      (value "1u Ceramic")
      (footprint "eagle-import:0603")
      (fields (field (name "PARTNO") "GMK107AB7105KAHT"))
      (libsource (lib "eagle-import") (part "CAP_CERAMIC0603"))
    )
    (comp (ref "C81")
      (value "10u Electrolyte")
      (footprint "eagle-import:PANASONIC_C")
      (fields (field (name "PARTNO") "EEE-HA1V100R"))
      (libsource (lib "eagle-import") (part "CAP_ELECTROLYTICPANASONIC_C"))
    )
    (comp (ref "C82")
      (value "10u Electrolyte")
      (footprint "eagle-import:PANASONIC_C")
      (fields (field (name "PARTNO") "EEE-HA1V100R"))
      (libsource (lib "eagle-import") (part "CAP_ELECTROLYTICPANASONIC_C"))
    )
    (comp (ref "C83")
      (value "10u Electrolyte")
      (footprint "eagle-import:PANASONIC_C")
      (fields (field (name "PARTNO") "EEE-HA1V100R"))
      (libsource (lib "eagle-import") (part "CAP_ELECTROLYTICPANASONIC_C"))
    )
    (comp (ref "C84")
      (value "1u Ceramic")
      (footprint "eagle-import:0603")
      (fields (field (name "PARTNO") "GMK107AB7105KAHT"))
      (libsource (lib "eagle-import") (part "CAP_CERAMIC0603"))
    )
    (comp (ref "C85")
      (value "1u Ceramic")
      (footprint "eagle-import:0603")
      (fields (field (name "PARTNO") "GMK107AB7105KAHT"))
      (libsource (lib "eagle-import") (part "CAP_CERAMIC0603"))
    )
    (comp (ref "C86")
      (value "1u Ceramic")
      (footprint "eagle-import:0603")
      (fields (field (name "PARTNO") "GMK107AB7105KAHT"))
      (libsource (lib "eagle-import") (part "CAP_CERAMIC0603"))
    )
    (comp (ref "C87")
      (value "10u Electrolyte")
      (footprint "eagle-import:PANASONIC_C")
      (fields (field (name "PARTNO") "EEE-HA1V100R"))
      (libsource (lib "eagle-import") (part "CAP_ELECTROLYTICPANASONIC_C"))
    )
    (comp (ref "C88")
      (value "10u Electrolyte")
      (footprint "eagle-import:PANASONIC_C")
      (fields (field (name "PARTNO") "EEE-HA1V100R"))
      (libsource (lib "eagle-import") (part "CAP_ELECTROLYTICPANASONIC_C"))
    )
    (comp (ref "C89")
      (value "10u Electrolyte")
      (footprint "eagle-import:PANASONIC_C")
      (fields (field (name "PARTNO") "EEE-HA1V100R"))
      (libsource (lib "eagle-import") (part "CAP_ELECTROLYTICPANASONIC_C"))
    )
    (comp (ref "C90")
      (value "1u Ceramic")
      (footprint "eagle-import:0603")
      (fields (field (name "PARTNO") "GMK107AB7105KAHT"))
      (libsource (lib "eagle-import") (part "CAP_CERAMIC0603"))
    )
    (comp (ref "C91")
      (value "1u Ceramic")
      (footprint "eagle-import:0603")
      (fields (field (name "PARTNO") "GMK107AB7105KAHT"))
      (libsource (lib "eagle-import") (part "CAP_CERAMIC0603"))
    )
    (comp (ref "C92")
      (value "10u Electrolyte")
      (footprint "eagle-import:PANASONIC_C")
      (fields (field (name "PARTNO") "EEE-HA1V100R"))
      (libsource (lib "eagle-import") (part "CAP_ELECTROLYTICPANASONIC_C"))
    )
    (comp (ref "C93")
      (value "10u Electrolyte")
      (footprint "eagle-import:PANASONIC_C")
      (fields (field (name "PARTNO") "EEE-HA1V100R"))
      (libsource (lib "eagle-import") (part "CAP_ELECTROLYTICPANASONIC_C"))
    )
    (comp (ref "JP2")
      (value "JP2E")
      (footprint "eagle-import:JP2")
      (fields (field (name "PARTNO") "61300311121"))
      (libsource (lib "eagle-import") (part "JP2E"))
    )
    (comp (ref "JP3")
      (value "JP2E")
      (footprint "eagle-import:JP2")
      (fields (field (name "PARTNO") "61300311121"))
      (libsource (lib "eagle-import") (part "JP2E"))
    )
    (comp (ref "JP4")
      (value "JP2E")
      (footprint "eagle-import:JP2")
      (fields (field (name "PARTNO") "61300311121"))
      (libsource (lib "eagle-import") (part "JP2E"))
    )
    (comp (ref "JP5")
      (value "JP2E")
      (footprint "eagle-import:JP2")
      (fields (field (name "PARTNO") "61300311121"))
      (libsource (lib "eagle-import") (part "JP2E"))
    )
    (comp (ref "JP7")
      (value "JP2E")
      (footprint "eagle-import:JP2")
      (fields (field (name "PARTNO") "61300311121"))
      (libsource (lib "eagle-import") (part "JP2E"))
    )
    (comp (ref "JP8")
      (value "JP2E")
      (footprint "eagle-import:JP2")
      (fields (field (name "PARTNO") "61300311121"))
      (libsource (lib "eagle-import") (part "JP2E"))
    )
    (comp (ref "JP9")
      (value "JP2E")
      (footprint "eagle-import:JP2")
      (fields (field (name "PARTNO") "61300311121"))
      (libsource (lib "eagle-import") (part "JP2E"))
    )
    (comp (ref "JP10")
      (value "JP2E")
      (footprint "eagle-import:JP2")
      (fields (field (name "PARTNO") "61300311121"))
      (libsource (lib "eagle-import") (part "JP2E"))
    )
    (comp (ref "L3")
      (value "600ohm @ 100MHz")
      (footprint "eagle-import:0603")
      (fields (field (name "PARTNO") "BLM18KG601SN1D"))
      (libsource (lib "eagle-import") (part "INDUCTOR0603"))
    )
    (comp (ref "L4")
      (value "600ohm @ 100MHz")
      (footprint "eagle-import:0603")
      (fields (field (name "PARTNO") "BLM18KG601SN1D"))
      (libsource (lib "eagle-import") (part "INDUCTOR0603"))
    )
    (comp (ref "R63")
      (value "0")
      (footprint "eagle-import:0603")
      (fields (field (name "PARTNO") "CRCW06030000Z0EBC"))
      (libsource (lib "eagle-import") (part "RESISTOR0603"))
    )
    (comp (ref "R64")
      (value "0")
      (footprint "eagle-import:0603")
      (fields (field (name "PARTNO") "CRCW06030000Z0EBC"))
      (libsource (lib "eagle-import") (part "RESISTOR0603"))
    )
    (comp (ref "R65")
      (value "22")
      (footprint "eagle-import:0603")
      (fields (field (name "PARTNO") "CRCW060322R0FKEAC"))
      (libsource (lib "eagle-import") (part "RESISTOR0603"))
    )
    (comp (ref "R66")
      (value "0")
      (footprint "eagle-import:0603")
      (fields (field (name "PARTNO") "CRCW06030000Z0EBC"))
      (libsource (lib "eagle-import") (part "RESISTOR0603"))
    )
    (comp (ref "R67")
      (value "0")
      (footprint "eagle-import:0603")
      (fields (field (name "PARTNO") "CRCW06030000Z0EBC"))
      (libsource (lib "eagle-import") (part "RESISTOR0603"))
    )
    (comp (ref "R68")
      (value "22")
      (footprint "eagle-import:0603")
      (fields (field (name "PARTNO") "CRCW060322R0FKEAC"))
      (libsource (lib "eagle-import") (part "RESISTOR0603"))
    )
    (comp (ref "R69")
      (value "0")
      (footprint "eagle-import:0603")
      (fields (field (name "PARTNO") "CRCW06030000Z0EBC"))
      (libsource (lib "eagle-import") (part "RESISTOR0603"))
    )
    (comp (ref "R70")
      (value "0")
      (footprint "eagle-import:0603")
      (fields (field (name "PARTNO") "CRCW06030000Z0EBC"))
      (libsource (lib "eagle-import") (part "RESISTOR0603"))
    )
    (comp (ref "R71")
      (value "0")
      (footprint "eagle-import:0603")
      (fields (field (name "PARTNO") "CRCW06030000Z0EBC"))
      (libsource (lib "eagle-import") (part "RESISTOR0603"))
    )
    (comp (ref "R72")
      (value "22")
      (footprint "eagle-import:0603")
      (fields (field (name "PARTNO") "CRCW060322R0FKEAC"))
      (libsource (lib "eagle-import") (part "RESISTOR0603"))
    )
    (comp (ref "R73")
      (value "22")
      (footprint "eagle-import:0603")
      (fields (field (name "PARTNO") "CRCW060322R0FKEAC"))
      (libsource (lib "eagle-import") (part "RESISTOR0603"))
    )
    (comp (ref "R74")
      (value "22")
      (footprint "eagle-import:0603")
      (fields (field (name "PARTNO") "CRCW060322R0FKEAC"))
      (libsource (lib "eagle-import") (part "RESISTOR0603"))
    )
    (comp (ref "R75")
      (value "0")
      (footprint "eagle-import:0603")
      (fields (field (name "PARTNO") "CRCW06030000Z0EBC"))
      (libsource (lib "eagle-import") (part "RESISTOR0603"))
    )
    (comp (ref "R76")
      (value "0")
      (footprint "eagle-import:0603")
      (fields (field (name "PARTNO") "CRCW06030000Z0EBC"))
      (libsource (lib "eagle-import") (part "RESISTOR0603"))
    )
    (comp (ref "R77")
      (value "22")
      (footprint "eagle-import:0603")
      (fields (field (name "PARTNO") "CRCW060322R0FKEAC"))
      (libsource (lib "eagle-import") (part "RESISTOR0603"))
    )
    (comp (ref "R78")
      (value "0")
      (footprint "eagle-import:0603")
      (fields (field (name "PARTNO") "CRCW06030000Z0EBC"))
      (libsource (lib "eagle-import") (part "RESISTOR0603"))
    )
    (comp (ref "R79")
      (value "0")
      (footprint "eagle-import:0603")
      (fields (field (name "PARTNO") "CRCW06030000Z0EBC"))
      (libsource (lib "eagle-import") (part "RESISTOR0603"))
    )
    (comp (ref "R80")
      (value "0")
      (footprint "eagle-import:0603")
      (fields (field (name "PARTNO") "CRCW06030000Z0EBC"))
      (libsource (lib "eagle-import") (part "RESISTOR0603"))
    )
    (comp (ref "R81")
      (value "0")
      (footprint "eagle-import:0603")
      (fields (field (name "PARTNO") "CRCW06030000Z0EBC"))
      (libsource (lib "eagle-import") (part "RESISTOR0603"))
    )
    (comp (ref "R82")
      (value "0")
      (footprint "eagle-import:0603")
      (fields (field (name "PARTNO") "CRCW06030000Z0EBC"))
      (libsource (lib "eagle-import") (part "RESISTOR0603"))
    )
    (comp (ref "R83")
      (value "22")
      (footprint "eagle-import:0603")
      (fields (field (name "PARTNO") "CRCW060322R0FKEAC"))
      (libsource (lib "eagle-import") (part "RESISTOR0603"))
    )
    (comp (ref "R84")
      (value "22")
      (footprint "eagle-import:0603")
      (fields (field (name "PARTNO") "CRCW060322R0FKEAC"))
      (libsource (lib "eagle-import") (part "RESISTOR0603"))
    )
    (comp (ref "R85")
      (value "22")
      (footprint "eagle-import:0603")
      (fields (field (name "PARTNO") "CRCW060322R0FKEAC"))
      (libsource (lib "eagle-import") (part "RESISTOR0603"))
    )
    (comp (ref "R86")
      (value "22")
      (footprint "eagle-import:0603")
      (fields (field (name "PARTNO") "CRCW060322R0FKEAC"))
      (libsource (lib "eagle-import") (part "RESISTOR0603"))
    )
    (comp (ref "R102")
      (value "1k")
      (footprint "eagle-import:0603")
      (fields (field (name "PARTNO") "CRCW06031K00FKEAC"))
      (libsource (lib "eagle-import") (part "RESISTOR0603"))
    )
    (comp (ref "R103")
      (value "1k")
      (footprint "eagle-import:0603")
      (fields (field (name "PARTNO") "CRCW06031K00FKEAC"))
      (libsource (lib "eagle-import") (part "RESISTOR0603"))
    )
    (comp (ref "R104")
      (value "1k")
      (footprint "eagle-import:0603")
      (fields (field (name "PARTNO") "CRCW06031K00FKEAC"))
      (libsource (lib "eagle-import") (part "RESISTOR0603"))
    )
    (comp (ref "R105")
      (value "1k")
      (footprint "eagle-import:0603")
      (fields (field (name "PARTNO") "CRCW06031K00FKEAC"))
      (libsource (lib "eagle-import") (part "RESISTOR0603"))
    )
    (comp (ref "U6")
      (value "PCM1681PWPPWP28_6P46X2P4-M")
      (footprint "eagle-import:PWP28_6P46X2P4-M")
      (fields
        (field (name "GENERIC_PART_NUMBER") "PCM1681")
        (field (name "MANUFACTURER") "Texas Instruments")
        (field (name "MANUFACTURER_PART_NUMBER") "PCM1681PWP")
        (field (name "PARTNO") "PCM1681PWP")
      )
      (libsource (lib "eagle-import") (part "PCM1681PWPPWP28_6P46X2P4-M"))
    )
    (comp (ref "U7")
      (value "PCM1681PWPPWP28_6P46X2P4-M")
      (footprint "eagle-import:PWP28_6P46X2P4-M")
      (fields
        (field (name "GENERIC_PART_NUMBER") "PCM1681")
        (field (name "MANUFACTURER") "Texas Instruments")
        (field (name "MANUFACTURER_PART_NUMBER") "PCM1681PWP")
        (field (name "PARTNO") "PCM1681PWP")
      )
      (libsource (lib "eagle-import") (part "PCM1681PWPPWP28_6P46X2P4-M"))
    )
    (comp (ref "C1")
      (value "470pF")
      (footprint "eagle-import:0603")
      (fields (field (name "PARTNO") "C0603C471J5GACTU"))
      (libsource (lib "eagle-import") (part "CAP_CERAMIC0603"))
    )
    (comp (ref "C2")
      (value "4700pF")
      (footprint "eagle-import:0603")
      (fields (field (name "PARTNO") "GRM1885C1H472JA01D"))
      (libsource (lib "eagle-import") (part "CAP_CERAMIC0603"))
    )
    (comp (ref "C3")
      (value "100u")
      (footprint "eagle-import:E2-5")
      (fields (field (name "PARTNO") "ESK107M025AC3AA"))
      (libsource (lib "eagle-import") (part "CPOL-USE2-5"))
    )
    (comp (ref "C4")
      (value "100n")
      (footprint "eagle-import:0603")
      (fields (field (name "PARTNO") "CC0603KRX7R9BB104"))
      (libsource (lib "eagle-import") (part "CAP_CERAMIC0603"))
    )
    (comp (ref "C5")
      (value "470pF")
      (footprint "eagle-import:0603")
      (fields (field (name "PARTNO") "C0603C471J5GACTU"))
      (libsource (lib "eagle-import") (part "CAP_CERAMIC0603"))
    )
    (comp (ref "C6")
      (value "4700pF")
      (footprint "eagle-import:0603")
      (fields (field (name "PARTNO") "GRM1885C1H472JA01D"))
      (libsource (lib "eagle-import") (part "CAP_CERAMIC0603"))
    )
    (comp (ref "C7")
      (value "100u")
      (footprint "eagle-import:E2-5")
      (fields (field (name "PARTNO") "ESK107M025AC3AA"))
      (libsource (lib "eagle-import") (part "CPOL-USE2-5"))
    )
    (comp (ref "C8")
      (value "100n")
      (footprint "eagle-import:0603")
      (fields (field (name "PARTNO") "CC0603KRX7R9BB104"))
      (libsource (lib "eagle-import") (part "CAP_CERAMIC0603"))
    )
    (comp (ref "C9")
      (value "470pF")
      (footprint "eagle-import:0603")
      (fields (field (name "PARTNO") "C0603C471J5GACTU"))
      (libsource (lib "eagle-import") (part "CAP_CERAMIC0603"))
    )
    (comp (ref "C10")
      (value "4700pF")
      (footprint "eagle-import:0603")
      (fields (field (name "PARTNO") "GRM1885C1H472JA01D"))
      (libsource (lib "eagle-import") (part "CAP_CERAMIC0603"))
    )
    (comp (ref "C11")
      (value "100u")
      (footprint "eagle-import:E2-5")
      (fields (field (name "PARTNO") "ESK107M025AC3AA"))
      (libsource (lib "eagle-import") (part "CPOL-USE2-5"))
    )
    (comp (ref "C12")
      (value "100n")
      (footprint "eagle-import:0603")
      (fields (field (name "PARTNO") "CC0603KRX7R9BB104"))
      (libsource (lib "eagle-import") (part "CAP_CERAMIC0603"))
    )
    (comp (ref "C13")
      (value "470pF")
      (footprint "eagle-import:0603")
      (fields (field (name "PARTNO") "C0603C471J5GACTU"))
      (libsource (lib "eagle-import") (part "CAP_CERAMIC0603"))
    )
    (comp (ref "C14")
      (value "4700pF")
      (footprint "eagle-import:0603")
      (fields (field (name "PARTNO") "GRM1885C1H472JA01D"))
      (libsource (lib "eagle-import") (part "CAP_CERAMIC0603"))
    )
    (comp (ref "C15")
      (value "100u")
      (footprint "eagle-import:E2-5")
      (fields (field (name "PARTNO") "ESK107M025AC3AA"))
      (libsource (lib "eagle-import") (part "CPOL-USE2-5"))
    )
    (comp (ref "C16")
      (value "100n")
      (footprint "eagle-import:0603")
      (fields (field (name "PARTNO") "CC0603KRX7R9BB104"))
      (libsource (lib "eagle-import") (part "CAP_CERAMIC0603"))
    )
    (comp (ref "C17")
      (value "470pF")
      (footprint "eagle-import:0603")
      (fields (field (name "PARTNO") "C0603C471J5GACTU"))
      (libsource (lib "eagle-import") (part "CAP_CERAMIC0603"))
    )
    (comp (ref "C18")
      (value "4700pF")
      (footprint "eagle-import:0603")
      (fields (field (name "PARTNO") "GRM1885C1H472JA01D"))
      (libsource (lib "eagle-import") (part "CAP_CERAMIC0603"))
    )
    (comp (ref "C19")
      (value "100u")
      (footprint "eagle-import:E2-5")
      (fields (field (name "PARTNO") "ESK107M025AC3AA"))
      (libsource (lib "eagle-import") (part "CPOL-USE2-5"))
    )
    (comp (ref "C20")
      (value "100n")
      (footprint "eagle-import:0603")
      (fields (field (name "PARTNO") "CC0603KRX7R9BB104"))
      (libsource (lib "eagle-import") (part "CAP_CERAMIC0603"))
    )
    (comp (ref "C21")
      (value "470pF")
      (footprint "eagle-import:0603")
      (fields (field (name "PARTNO") "C0603C471J5GACTU"))
      (libsource (lib "eagle-import") (part "CAP_CERAMIC0603"))
    )
    (comp (ref "C22")
      (value "4700pF")
      (footprint "eagle-import:0603")
      (fields (field (name "PARTNO") "GRM1885C1H472JA01D"))
      (libsource (lib "eagle-import") (part "CAP_CERAMIC0603"))
    )
    (comp (ref "C23")
      (value "100u")
      (footprint "eagle-import:E2-5")
      (fields (field (name "PARTNO") "ESK107M025AC3AA"))
      (libsource (lib "eagle-import") (part "CPOL-USE2-5"))
    )
    (comp (ref "C24")
      (value "100n")
      (footprint "eagle-import:0603")
      (fields (field (name "PARTNO") "CC0603KRX7R9BB104"))
      (libsource (lib "eagle-import") (part "CAP_CERAMIC0603"))
    )
    (comp (ref "C25")
      (value "470pF")
      (footprint "eagle-import:0603")
      (fields (field (name "PARTNO") "C0603C471J5GACTU"))
      (libsource (lib "eagle-import") (part "CAP_CERAMIC0603"))
    )
    (comp (ref "C26")
      (value "4700pF")
      (footprint "eagle-import:0603")
      (fields (field (name "PARTNO") "GRM1885C1H472JA01D"))
      (libsource (lib "eagle-import") (part "CAP_CERAMIC0603"))
    )
    (comp (ref "C27")
      (value "100u")
      (footprint "eagle-import:E2-5")
      (fields (field (name "PARTNO") "ESK107M025AC3AA"))
      (libsource (lib "eagle-import") (part "CPOL-USE2-5"))
    )
    (comp (ref "C28")
      (value "100n")
      (footprint "eagle-import:0603")
      (fields (field (name "PARTNO") "CC0603KRX7R9BB104"))
      (libsource (lib "eagle-import") (part "CAP_CERAMIC0603"))
    )
    (comp (ref "C29")
      (value "470pF")
      (footprint "eagle-import:0603")
      (fields (field (name "PARTNO") "C0603C471J5GACTU"))
      (libsource (lib "eagle-import") (part "CAP_CERAMIC0603"))
    )
    (comp (ref "C30")
      (value "4700pF")
      (footprint "eagle-import:0603")
      (fields (field (name "PARTNO") "GRM1885C1H472JA01D"))
      (libsource (lib "eagle-import") (part "CAP_CERAMIC0603"))
    )
    (comp (ref "C31")
      (value "100u")
      (footprint "eagle-import:E2-5")
      (fields (field (name "PARTNO") "ESK107M025AC3AA"))
      (libsource (lib "eagle-import") (part "CPOL-USE2-5"))
    )
    (comp (ref "C32")
      (value "100n")
      (footprint "eagle-import:0603")
      (fields (field (name "PARTNO") "CC0603KRX7R9BB104"))
      (libsource (lib "eagle-import") (part "CAP_CERAMIC0603"))
    )
    (comp (ref "C33")
      (value "470pF")
      (footprint "eagle-import:0603")
      (fields (field (name "PARTNO") "C0603C471J5GACTU"))
      (libsource (lib "eagle-import") (part "CAP_CERAMIC0603"))
    )
    (comp (ref "C34")
      (value "4700pF")
      (footprint "eagle-import:0603")
      (fields (field (name "PARTNO") "GRM1885C1H472JA01D"))
      (libsource (lib "eagle-import") (part "CAP_CERAMIC0603"))
    )
    (comp (ref "C35")
      (value "100u")
      (footprint "eagle-import:E2-5")
      (fields (field (name "PARTNO") "ESK107M025AC3AA"))
      (libsource (lib "eagle-import") (part "CPOL-USE2-5"))
    )
    (comp (ref "C36")
      (value "100n")
      (footprint "eagle-import:0603")
      (fields (field (name "PARTNO") "CC0603KRX7R9BB104"))
      (libsource (lib "eagle-import") (part "CAP_CERAMIC0603"))
    )
    (comp (ref "C37")
      (value "470pF")
      (footprint "eagle-import:0603")
      (fields (field (name "PARTNO") "C0603C471J5GACTU"))
      (libsource (lib "eagle-import") (part "CAP_CERAMIC0603"))
    )
    (comp (ref "C38")
      (value "4700pF")
      (footprint "eagle-import:0603")
      (fields (field (name "PARTNO") "GRM1885C1H472JA01D"))
      (libsource (lib "eagle-import") (part "CAP_CERAMIC0603"))
    )
    (comp (ref "C39")
      (value "100u")
      (footprint "eagle-import:E2-5")
      (fields (field (name "PARTNO") "ESK107M025AC3AA"))
      (libsource (lib "eagle-import") (part "CPOL-USE2-5"))
    )
    (comp (ref "C40")
      (value "100n")
      (footprint "eagle-import:0603")
      (fields (field (name "PARTNO") "CC0603KRX7R9BB104"))
      (libsource (lib "eagle-import") (part "CAP_CERAMIC0603"))
    )
    (comp (ref "C41")
      (value "470pF")
      (footprint "eagle-import:0603")
      (fields (field (name "PARTNO") "C0603C471J5GACTU"))
      (libsource (lib "eagle-import") (part "CAP_CERAMIC0603"))
    )
    (comp (ref "C42")
      (value "4700pF")
      (footprint "eagle-import:0603")
      (fields (field (name "PARTNO") "GRM1885C1H472JA01D"))
      (libsource (lib "eagle-import") (part "CAP_CERAMIC0603"))
    )
    (comp (ref "C43")
      (value "100u")
      (footprint "eagle-import:E2-5")
      (fields (field (name "PARTNO") "ESK107M025AC3AA"))
      (libsource (lib "eagle-import") (part "CPOL-USE2-5"))
    )
    (comp (ref "C44")
      (value "100n")
      (footprint "eagle-import:0603")
      (fields (field (name "PARTNO") "CC0603KRX7R9BB104"))
      (libsource (lib "eagle-import") (part "CAP_CERAMIC0603"))
    )
    (comp (ref "C45")
      (value "470pF")
      (footprint "eagle-import:0603")
      (fields (field (name "PARTNO") "C0603C471J5GACTU"))
      (libsource (lib "eagle-import") (part "CAP_CERAMIC0603"))
    )
    (comp (ref "C46")
      (value "4700pF")
      (footprint "eagle-import:0603")
      (fields (field (name "PARTNO") "GRM1885C1H472JA01D"))
      (libsource (lib "eagle-import") (part "CAP_CERAMIC0603"))
    )
    (comp (ref "C47")
      (value "100u")
      (footprint "eagle-import:E2-5")
      (fields (field (name "PARTNO") "ESK107M025AC3AA"))
      (libsource (lib "eagle-import") (part "CPOL-USE2-5"))
    )
    (comp (ref "C48")
      (value "100n")
      (footprint "eagle-import:0603")
      (fields (field (name "PARTNO") "CC0603KRX7R9BB104"))
      (libsource (lib "eagle-import") (part "CAP_CERAMIC0603"))
    )
    (comp (ref "IC1")
      (value "TL072D")
      (footprint "eagle-import:SO08")
      (fields (field (name "PARTNO") "TL072SG-13"))
      (libsource (lib "eagle-import") (part "TL072D"))
    )
    (comp (ref "IC2")
      (value "TL072D")
      (footprint "eagle-import:SO08")
      (fields (field (name "PARTNO") "TL072SG-13"))
      (libsource (lib "eagle-import") (part "TL072D"))
    )
    (comp (ref "IC3")
      (value "TL072D")
      (footprint "eagle-import:SO08")
      (fields (field (name "PARTNO") "TL072SG-13"))
      (libsource (lib "eagle-import") (part "TL072D"))
    )
    (comp (ref "IC4")
      (value "TL072D")
      (footprint "eagle-import:SO08")
      (fields (field (name "PARTNO") "TL072SG-13"))
      (libsource (lib "eagle-import") (part "TL072D"))
    )
    (comp (ref "IC5")
      (value "TL072D")
      (footprint "eagle-import:SO08")
      (fields (field (name "PARTNO") "TL072SG-13"))
      (libsource (lib "eagle-import") (part "TL072D"))
    )
    (comp (ref "IC6")
      (value "TL072D")
      (footprint "eagle-import:SO08")
      (fields (field (name "PARTNO") "TL072SG-13"))
      (libsource (lib "eagle-import") (part "TL072D"))
    )
    (comp (ref "R1")
      (value "47")
      (footprint "eagle-import:0603")
      (fields (field (name "PARTNO") "CRCW060347R0FKEAC"))
      (libsource (lib "eagle-import") (part "RESISTOR0603"))
    )
    (comp (ref "R2")
      (value "560")
      (footprint "eagle-import:0603")
      (fields (field (name "PARTNO") "RC0603FR-07560RL"))
      (libsource (lib "eagle-import") (part "RESISTOR0603"))
    )
    (comp (ref "R3")
      (value "8.2k")
      (footprint "eagle-import:0603")
      (fields (field (name "PARTNO") "ERJ-3EKF8201V"))
      (libsource (lib "eagle-import") (part "RESISTOR0603"))
    )
    (comp (ref "R4")
      (value "5.1k")
      (footprint "eagle-import:0603")
      (fields (field (name "PARTNO") "CRCW06035K10FKEAC"))
      (libsource (lib "eagle-import") (part "RESISTOR0603"))
    )
    (comp (ref "R5")
      (value "560")
      (footprint "eagle-import:0603")
      (fields (field (name "PARTNO") "RC0603FR-07560RL"))
      (libsource (lib "eagle-import") (part "RESISTOR0603"))
    )
    (comp (ref "R6")
      (value "8.2k")
      (footprint "eagle-import:0603")
      (fields (field (name "PARTNO") "ERJ-3EKF8201V"))
      (libsource (lib "eagle-import") (part "RESISTOR0603"))
    )
    (comp (ref "R7")
      (value "5.1k")
      (footprint "eagle-import:0603")
      (fields (field (name "PARTNO") "CRCW06035K10FKEAC"))
      (libsource (lib "eagle-import") (part "RESISTOR0603"))
    )
    (comp (ref "R8")
      (value "47")
      (footprint "eagle-import:0603")
      (fields (field (name "PARTNO") "CRCW060347R0FKEAC"))
      (libsource (lib "eagle-import") (part "RESISTOR0603"))
    )
    (comp (ref "R9")
      (value "47")
      (footprint "eagle-import:0603")
      (fields (field (name "PARTNO") "CRCW060347R0FKEAC"))
      (libsource (lib "eagle-import") (part "RESISTOR0603"))
    )
    (comp (ref "R10")
      (value "560")
      (footprint "eagle-import:0603")
      (fields (field (name "PARTNO") "RC0603FR-07560RL"))
      (libsource (lib "eagle-import") (part "RESISTOR0603"))
    )
    (comp (ref "R11")
      (value "8.2k")
      (footprint "eagle-import:0603")
      (fields (field (name "PARTNO") "ERJ-3EKF8201V"))
      (libsource (lib "eagle-import") (part "RESISTOR0603"))
    )
    (comp (ref "R12")
      (value "5.1k")
      (footprint "eagle-import:0603")
      (fields (field (name "PARTNO") "CRCW06035K10FKEAC"))
      (libsource (lib "eagle-import") (part "RESISTOR0603"))
    )
    (comp (ref "R13")
      (value "560")
      (footprint "eagle-import:0603")
      (fields (field (name "PARTNO") "RC0603FR-07560RL"))
      (libsource (lib "eagle-import") (part "RESISTOR0603"))
    )
    (comp (ref "R14")
      (value "8.2k")
      (footprint "eagle-import:0603")
      (fields (field (name "PARTNO") "ERJ-3EKF8201V"))
      (libsource (lib "eagle-import") (part "RESISTOR0603"))
    )
    (comp (ref "R15")
      (value "5.1k")
      (footprint "eagle-import:0603")
      (fields (field (name "PARTNO") "CRCW06035K10FKEAC"))
      (libsource (lib "eagle-import") (part "RESISTOR0603"))
    )
    (comp (ref "R16")
      (value "47")
      (footprint "eagle-import:0603")
      (fields (field (name "PARTNO") "CRCW060347R0FKEAC"))
      (libsource (lib "eagle-import") (part "RESISTOR0603"))
    )
    (comp (ref "R17")
      (value "47")
      (footprint "eagle-import:0603")
      (fields (field (name "PARTNO") "CRCW060347R0FKEAC"))
      (libsource (lib "eagle-import") (part "RESISTOR0603"))
    )
    (comp (ref "R18")
      (value "560")
      (footprint "eagle-import:0603")
      (fields (field (name "PARTNO") "RC0603FR-07560RL"))
      (libsource (lib "eagle-import") (part "RESISTOR0603"))
    )
    (comp (ref "R19")
      (value "8.2k")
      (footprint "eagle-import:0603")
      (fields (field (name "PARTNO") "ERJ-3EKF8201V"))
      (libsource (lib "eagle-import") (part "RESISTOR0603"))
    )
    (comp (ref "R20")
      (value "5.1k")
      (footprint "eagle-import:0603")
      (fields (field (name "PARTNO") "CRCW06035K10FKEAC"))
      (libsource (lib "eagle-import") (part "RESISTOR0603"))
    )
    (comp (ref "R21")
      (value "560")
      (footprint "eagle-import:0603")
      (fields (field (name "PARTNO") "RC0603FR-07560RL"))
      (libsource (lib "eagle-import") (part "RESISTOR0603"))
    )
    (comp (ref "R22")
      (value "8.2k")
      (footprint "eagle-import:0603")
      (fields (field (name "PARTNO") "ERJ-3EKF8201V"))
      (libsource (lib "eagle-import") (part "RESISTOR0603"))
    )
    (comp (ref "R23")
      (value "5.1k")
      (footprint "eagle-import:0603")
      (fields (field (name "PARTNO") "CRCW06035K10FKEAC"))
      (libsource (lib "eagle-import") (part "RESISTOR0603"))
    )
    (comp (ref "R24")
      (value "47")
      (footprint "eagle-import:0603")
      (fields (field (name "PARTNO") "CRCW060347R0FKEAC"))
      (libsource (lib "eagle-import") (part "RESISTOR0603"))
    )
    (comp (ref "R25")
      (value "47")
      (footprint "eagle-import:0603")
      (fields (field (name "PARTNO") "CRCW060347R0FKEAC"))
      (libsource (lib "eagle-import") (part "RESISTOR0603"))
    )
    (comp (ref "R26")
      (value "560")
      (footprint "eagle-import:0603")
      (fields (field (name "PARTNO") "RC0603FR-07560RL"))
      (libsource (lib "eagle-import") (part "RESISTOR0603"))
    )
    (comp (ref "R27")
      (value "8.2k")
      (footprint "eagle-import:0603")
      (fields (field (name "PARTNO") "ERJ-3EKF8201V"))
      (libsource (lib "eagle-import") (part "RESISTOR0603"))
    )
    (comp (ref "R28")
      (value "5.1k")
      (footprint "eagle-import:0603")
      (fields (field (name "PARTNO") "CRCW06035K10FKEAC"))
      (libsource (lib "eagle-import") (part "RESISTOR0603"))
    )
    (comp (ref "R29")
      (value "560")
      (footprint "eagle-import:0603")
      (fields (field (name "PARTNO") "RC0603FR-07560RL"))
      (libsource (lib "eagle-import") (part "RESISTOR0603"))
    )
    (comp (ref "R30")
      (value "8.2k")
      (footprint "eagle-import:0603")
      (fields (field (name "PARTNO") "ERJ-3EKF8201V"))
      (libsource (lib "eagle-import") (part "RESISTOR0603"))
    )
    (comp (ref "R31")
      (value "5.1k")
      (footprint "eagle-import:0603")
      (fields (field (name "PARTNO") "CRCW06035K10FKEAC"))
      (libsource (lib "eagle-import") (part "RESISTOR0603"))
    )
    (comp (ref "R32")
      (value "47")
      (footprint "eagle-import:0603")
      (fields (field (name "PARTNO") "CRCW060347R0FKEAC"))
      (libsource (lib "eagle-import") (part "RESISTOR0603"))
    )
    (comp (ref "R33")
      (value "47")
      (footprint "eagle-import:0603")
      (fields (field (name "PARTNO") "CRCW060347R0FKEAC"))
      (libsource (lib "eagle-import") (part "RESISTOR0603"))
    )
    (comp (ref "R34")
      (value "560")
      (footprint "eagle-import:0603")
      (fields (field (name "PARTNO") "RC0603FR-07560RL"))
      (libsource (lib "eagle-import") (part "RESISTOR0603"))
    )
    (comp (ref "R35")
      (value "8.2k")
      (footprint "eagle-import:0603")
      (fields (field (name "PARTNO") "ERJ-3EKF8201V"))
      (libsource (lib "eagle-import") (part "RESISTOR0603"))
    )
    (comp (ref "R36")
      (value "5.1k")
      (footprint "eagle-import:0603")
      (fields (field (name "PARTNO") "CRCW06035K10FKEAC"))
      (libsource (lib "eagle-import") (part "RESISTOR0603"))
    )
    (comp (ref "R37")
      (value "560")
      (footprint "eagle-import:0603")
      (fields (field (name "PARTNO") "RC0603FR-07560RL"))
      (libsource (lib "eagle-import") (part "RESISTOR0603"))
    )
    (comp (ref "R38")
      (value "8.2k")
      (footprint "eagle-import:0603")
      (fields (field (name "PARTNO") "ERJ-3EKF8201V"))
      (libsource (lib "eagle-import") (part "RESISTOR0603"))
    )
    (comp (ref "R39")
      (value "5.1k")
      (footprint "eagle-import:0603")
      (fields (field (name "PARTNO") "CRCW06035K10FKEAC"))
      (libsource (lib "eagle-import") (part "RESISTOR0603"))
    )
    (comp (ref "R40")
      (value "47")
      (footprint "eagle-import:0603")
      (fields (field (name "PARTNO") "CRCW060347R0FKEAC"))
      (libsource (lib "eagle-import") (part "RESISTOR0603"))
    )
    (comp (ref "R41")
      (value "47")
      (footprint "eagle-import:0603")
      (fields (field (name "PARTNO") "CRCW060347R0FKEAC"))
      (libsource (lib "eagle-import") (part "RESISTOR0603"))
    )
    (comp (ref "R42")
      (value "560")
      (footprint "eagle-import:0603")
      (fields (field (name "PARTNO") "RC0603FR-07560RL"))
      (libsource (lib "eagle-import") (part "RESISTOR0603"))
    )
    (comp (ref "R43")
      (value "8.2k")
      (footprint "eagle-import:0603")
      (fields (field (name "PARTNO") "ERJ-3EKF8201V"))
      (libsource (lib "eagle-import") (part "RESISTOR0603"))
    )
    (comp (ref "R44")
      (value "5.1k")
      (footprint "eagle-import:0603")
      (fields (field (name "PARTNO") "CRCW06035K10FKEAC"))
      (libsource (lib "eagle-import") (part "RESISTOR0603"))
    )
    (comp (ref "R45")
      (value "560")
      (footprint "eagle-import:0603")
      (fields (field (name "PARTNO") "RC0603FR-07560RL"))
      (libsource (lib "eagle-import") (part "RESISTOR0603"))
    )
    (comp (ref "R46")
      (value "8.2k")
      (footprint "eagle-import:0603")
      (fields (field (name "PARTNO") "ERJ-3EKF8201V"))
      (libsource (lib "eagle-import") (part "RESISTOR0603"))
    )
    (comp (ref "R47")
      (value "5.1k")
      (footprint "eagle-import:0603")
      (fields (field (name "PARTNO") "CRCW06035K10FKEAC"))
      (libsource (lib "eagle-import") (part "RESISTOR0603"))
    )
    (comp (ref "R48")
      (value "47")
      (footprint "eagle-import:0603")
      (fields (field (name "PARTNO") "CRCW060347R0FKEAC"))
      (libsource (lib "eagle-import") (part "RESISTOR0603"))
    )
  )
  (nets
    (net (code "1") (name "+3V3") (class "Default")
      (node (ref "C103") (pin "1") (pinfunction "P$1_1") (pintype "passive"))
      (node (ref "C54") (pin "2") (pinfunction "P$2_2") (pintype "passive"))
      (node (ref "C57") (pin "2") (pinfunction "P$2_2") (pintype "passive"))
      (node (ref "C58") (pin "2") (pinfunction "P$2_2") (pintype "passive"))
      (node (ref "C59") (pin "2") (pinfunction "P$2_2") (pintype "passive"))
      (node (ref "C60") (pin "2") (pinfunction "P$2_2") (pintype "passive"))
      (node (ref "C61") (pin "2") (pinfunction "P$2_2") (pintype "passive"))
      (node (ref "C62") (pin "2") (pinfunction "P$2_2") (pintype "passive"))
      (node (ref "C63") (pin "2") (pinfunction "P$2_2") (pintype "passive"))
      (node (ref "C64") (pin "2") (pinfunction "P$2_2") (pintype "passive"))
      (node (ref "C65") (pin "2") (pinfunction "P$2_2") (pintype "passive"))
      (node (ref "C66") (pin "2") (pinfunction "P$2_2") (pintype "passive"))
      (node (ref "C67") (pin "2") (pinfunction "P$2_2") (pintype "passive"))
      (node (ref "C68") (pin "2") (pinfunction "P$2_2") (pintype "passive"))
      (node (ref "C69") (pin "2") (pinfunction "P$2_2") (pintype "passive"))
      (node (ref "C70") (pin "2") (pinfunction "P$2_2") (pintype "passive"))
      (node (ref "C75") (pin "2") (pinfunction "P$2_2") (pintype "passive"))
      (node (ref "C76") (pin "2") (pinfunction "P$2_2") (pintype "passive"))
      (node (ref "C80") (pin "2") (pinfunction "P$2_2") (pintype "passive"))
      (node (ref "C81") (pin "+") (pinfunction "+_+") (pintype "passive"))
      (node (ref "C86") (pin "2") (pinfunction "P$2_2") (pintype "passive"))
      (node (ref "C87") (pin "+") (pinfunction "+_+") (pintype "passive"))
      (node (ref "IC7") (pin "3") (pinfunction "~{RESET}_3") (pintype "input"))
      (node (ref "IC7") (pin "5") (pinfunction "~{WP}_5") (pintype "input"))
      (node (ref "IC7") (pin "6") (pinfunction "VCC_6") (pintype "power_in"))
      (node (ref "JP2") (pin "3") (pinfunction "3_3") (pintype "passive"))
      (node (ref "JP7") (pin "3") (pinfunction "3_3") (pintype "passive"))
      (node (ref "JP8") (pin "3") (pinfunction "3_3") (pintype "passive"))
      (node (ref "L1") (pin "2") (pinfunction "2_2") (pintype "passive"))
      (node (ref "OSC1") (pin "4") (pinfunction "VCC_4") (pintype "power_in"))
      (node (ref "R50") (pin "1") (pinfunction "1_1") (pintype "passive"))
      (node (ref "R51") (pin "2") (pinfunction "2_2") (pintype "passive"))
      (node (ref "R53") (pin "2") (pinfunction "2_2") (pintype "passive"))
      (node (ref "R55") (pin "2") (pinfunction "2_2") (pintype "passive"))
      (node (ref "R92") (pin "2") (pinfunction "2_2") (pintype "passive"))
      (node (ref "R93") (pin "2") (pinfunction "2_2") (pintype "passive"))
      (node (ref "TC1") (pin "1") (pinfunction "1_1") (pintype "passive"))
      (node (ref "U3") (pin "108") (pinfunction "VDD_9_108") (pintype "power_in"))
      (node (ref "U3") (pin "121") (pinfunction "VDDSDMMC_121") (pintype "power_in"))
      (node (ref "U3") (pin "131") (pinfunction "VDD_10_131") (pintype "power_in"))
      (node (ref "U3") (pin "144") (pinfunction "VDD_144") (pintype "power_in"))
      (node (ref "U3") (pin "17") (pinfunction "VDD_2_17") (pintype "power_in"))
      (node (ref "U3") (pin "30") (pinfunction "VDD_3_30") (pintype "power_in"))
      (node (ref "U3") (pin "32") (pinfunction "VREF+_32") (pintype "power_in"))
      (node (ref "U3") (pin "33") (pinfunction "VDDA_33") (pintype "power_in"))
      (node (ref "U3") (pin "39") (pinfunction "VDD_4_39") (pintype "power_in"))
      (node (ref "U3") (pin "52") (pinfunction "VDD_5_52") (pintype "bidirectional"))
      (node (ref "U3") (pin "6") (pinfunction "VBAT_6") (pintype "power_in"))
      (node (ref "U3") (pin "62") (pinfunction "VDD_6_62") (pintype "power_in"))
      (node (ref "U3") (pin "72") (pinfunction "VDD_7_72") (pintype "power_in"))
      (node (ref "U3") (pin "86") (pinfunction "VDD_8_86") (pintype "power_in"))
      (node (ref "U3") (pin "95") (pinfunction "VDDUSB_95") (pintype "power_in"))
      (node (ref "U6") (pin "9") (pinfunction "VDD_9") (pintype "power_in"))
      (node (ref "U7") (pin "9") (pinfunction "VDD_9") (pintype "power_in"))
    )
    (net (code "2") (name "+5V") (class "Default")
      (node (ref "C49") (pin "2") (pinfunction "P$2_2") (pintype "passive"))
      (node (ref "C77") (pin "+") (pinfunction "+_+") (pintype "passive"))
      (node (ref "JP6") (pin "2") (pinfunction "2_2") (pintype "passive"))
      (node (ref "L3") (pin "1") (pinfunction "1_1") (pintype "passive"))
      (node (ref "L4") (pin "1") (pinfunction "1_1") (pintype "passive"))
      (node (ref "U1") (pin "2") (pinfunction "IN_2") (pintype "input"))
      (node (ref "U3") (pin "101") (pinfunction "PA9_101") (pintype "bidirectional"))
      (node (ref "U3") (pin "74") (pinfunction "PB13_74") (pintype "bidirectional"))
      (node (ref "U4") (pin "5") (pinfunction "VBUS_5") (pintype "power_in"))
      (node (ref "U5") (pin "5") (pinfunction "VBUS_5") (pintype "power_in"))
      (node (ref "USB_FS") (pin "1") (pinfunction "1_1") (pintype "bidirectional"))
      (node (ref "USB_HS") (pin "P$1") (pinfunction "1_P$1") (pintype "passive"))
    )
    (net (code "3") (name "+12V") (class "Default")
      (node (ref "APWR_EN") (pin "1") (pinfunction "1_1") (pintype "passive"))
      (node (ref "C12") (pin "1") (pinfunction "P$1_1") (pintype "passive"))
      (node (ref "C20") (pin "1") (pinfunction "P$1_1") (pintype "passive"))
      (node (ref "C28") (pin "1") (pinfunction "P$1_1") (pintype "passive"))
      (node (ref "C36") (pin "1") (pinfunction "P$1_1") (pintype "passive"))
      (node (ref "C4") (pin "1") (pinfunction "P$1_1") (pintype "passive"))
      (node (ref "C44") (pin "1") (pinfunction "P$1_1") (pintype "passive"))
      (node (ref "IC1") (pin "8") (pinfunction "V+_8") (pintype "power_in"))
      (node (ref "IC2") (pin "8") (pinfunction "V+_8") (pintype "power_in"))
      (node (ref "IC3") (pin "8") (pinfunction "V+_8") (pintype "power_in"))
      (node (ref "IC4") (pin "8") (pinfunction "V+_8") (pintype "power_in"))
      (node (ref "IC5") (pin "8") (pinfunction "V+_8") (pintype "power_in"))
      (node (ref "IC6") (pin "8") (pinfunction "V+_8") (pintype "power_in"))
    )
    (net (code "4") (name "+15V") (class "Default")
      (node (ref "C52") (pin "2") (pinfunction "P$2_2") (pintype "passive"))
      (node (ref "C94") (pin "2") (pinfunction "P$2_2") (pintype "passive"))
      (node (ref "C95") (pin "1") (pinfunction "P$1_1") (pintype "passive"))
      (node (ref "D2") (pin "C") (pinfunction "C_C") (pintype "passive"))
      (node (ref "IC10") (pin "3") (pinfunction "IN_3") (pintype "bidirectional"))
      (node (ref "JP6") (pin "8") (pinfunction "2_8") (pintype "passive"))
      (node (ref "TP3") (pin "TP") (pinfunction "TP_TP") (pintype "input"))
    )
    (net (code "5") (name "-12V") (class "Default")
      (node (ref "APWR_EN") (pin "3") (pinfunction "1_3") (pintype "passive"))
      (node (ref "C16") (pin "2") (pinfunction "P$2_2") (pintype "passive"))
      (node (ref "C24") (pin "2") (pinfunction "P$2_2") (pintype "passive"))
      (node (ref "C32") (pin "2") (pinfunction "P$2_2") (pintype "passive"))
      (node (ref "C40") (pin "2") (pinfunction "P$2_2") (pintype "passive"))
      (node (ref "C48") (pin "2") (pinfunction "P$2_2") (pintype "passive"))
      (node (ref "C8") (pin "2") (pinfunction "P$2_2") (pintype "passive"))
      (node (ref "IC1") (pin "4") (pinfunction "V-_4") (pintype "power_in"))
      (node (ref "IC2") (pin "4") (pinfunction "V-_4") (pintype "power_in"))
      (node (ref "IC3") (pin "4") (pinfunction "V-_4") (pintype "power_in"))
      (node (ref "IC4") (pin "4") (pinfunction "V-_4") (pintype "power_in"))
      (node (ref "IC5") (pin "4") (pinfunction "V-_4") (pintype "power_in"))
      (node (ref "IC6") (pin "4") (pinfunction "V-_4") (pintype "power_in"))
    )
    (net (code "6") (name "-15V") (class "Default")
      (node (ref "C53") (pin "2") (pinfunction "P$2_2") (pintype "passive"))
      (node (ref "C98") (pin "1") (pinfunction "P$1_1") (pintype "passive"))
      (node (ref "C99") (pin "2") (pinfunction "P$2_2") (pintype "passive"))
      (node (ref "D3") (pin "A") (pinfunction "A_A") (pintype "passive"))
      (node (ref "IC11") (pin "2") (pinfunction "IN_2") (pintype "bidirectional"))
      (node (ref "IC11") (pin "4") (pinfunction "IN_TAB_4") (pintype "bidirectional"))
      (node (ref "JP6") (pin "4") (pinfunction "2_4") (pintype "passive"))
      (node (ref "TP4") (pin "TP") (pinfunction "TP_TP") (pintype "input"))
    )
    (net (code "7") (name "DAC_OUT1") (class "Default")
      (node (ref "C3") (pin "+") (pinfunction "+_+") (pintype "passive"))
      (node (ref "U6") (pin "15") (pinfunction "VOUT8_15") (pintype "output"))
    )
    (net (code "8") (name "DAC_OUT2") (class "Default")
      (node (ref "C7") (pin "+") (pinfunction "+_+") (pintype "passive"))
      (node (ref "U6") (pin "16") (pinfunction "VOUT7_16") (pintype "output"))
    )
    (net (code "9") (name "DAC_OUT3") (class "Default")
      (node (ref "C11") (pin "+") (pinfunction "+_+") (pintype "passive"))
      (node (ref "U6") (pin "19") (pinfunction "VOUT6_19") (pintype "output"))
    )
    (net (code "10") (name "DAC_OUT4") (class "Default")
      (node (ref "C15") (pin "+") (pinfunction "+_+") (pintype "passive"))
      (node (ref "U6") (pin "20") (pinfunction "VOUT5_20") (pintype "output"))
    )
    (net (code "11") (name "DAC_OUT5") (class "Default")
      (node (ref "C19") (pin "+") (pinfunction "+_+") (pintype "passive"))
      (node (ref "U6") (pin "21") (pinfunction "VOUT4_21") (pintype "output"))
    )
    (net (code "12") (name "DAC_OUT6") (class "Default")
      (node (ref "C23") (pin "+") (pinfunction "+_+") (pintype "passive"))
      (node (ref "U6") (pin "22") (pinfunction "VOUT3_22") (pintype "output"))
    )
    (net (code "13") (name "DAC_OUT7") (class "Default")
      (node (ref "C27") (pin "+") (pinfunction "+_+") (pintype "passive"))
      (node (ref "U6") (pin "26") (pinfunction "VOUT2_26") (pintype "output"))
    )
    (net (code "14") (name "DAC_OUT8") (class "Default")
      (node (ref "C31") (pin "+") (pinfunction "+_+") (pintype "passive"))
      (node (ref "U6") (pin "27") (pinfunction "VOUT1_27") (pintype "output"))
    )
    (net (code "15") (name "DAC_OUT9") (class "Default")
      (node (ref "C35") (pin "+") (pinfunction "+_+") (pintype "passive"))
      (node (ref "U7") (pin "21") (pinfunction "VOUT4_21") (pintype "output"))
    )
    (net (code "16") (name "DAC_OUT10") (class "Default")
      (node (ref "C39") (pin "+") (pinfunction "+_+") (pintype "passive"))
      (node (ref "U7") (pin "22") (pinfunction "VOUT3_22") (pintype "output"))
    )
    (net (code "17") (name "DAC_OUT11") (class "Default")
      (node (ref "C43") (pin "+") (pinfunction "+_+") (pintype "passive"))
      (node (ref "U7") (pin "26") (pinfunction "VOUT2_26") (pintype "output"))
    )
    (net (code "18") (name "DAC_OUT12") (class "Default")
      (node (ref "C47") (pin "+") (pinfunction "+_+") (pintype "passive"))
      (node (ref "U7") (pin "27") (pinfunction "VOUT1_27") (pintype "output"))
    )
    (net (code "19") (name "EXT_OUT1") (class "Default")
      (node (ref "PL1") (pin "13") (pinfunction "TT_13") (pintype "bidirectional"))
      (node (ref "R1") (pin "2") (pinfunction "2_2") (pintype "passive"))
    )
    (net (code "20") (name "EXT_OUT2") (class "Default")
      (node (ref "PL1") (pin "12") (pinfunction "TB_12") (pintype "bidirectional"))
      (node (ref "R8") (pin "2") (pinfunction "2_2") (pintype "passive"))
    )
    (net (code "21") (name "EXT_OUT3") (class "Default")
      (node (ref "PL2") (pin "13") (pinfunction "TT_13") (pintype "bidirectional"))
      (node (ref "R9") (pin "2") (pinfunction "2_2") (pintype "passive"))
    )
    (net (code "22") (name "EXT_OUT4") (class "Default")
      (node (ref "PL2") (pin "12") (pinfunction "TB_12") (pintype "bidirectional"))
      (node (ref "R16") (pin "2") (pinfunction "2_2") (pintype "passive"))
    )
    (net (code "23") (name "EXT_OUT5") (class "Default")
      (node (ref "PL3") (pin "13") (pinfunction "TT_13") (pintype "bidirectional"))
      (node (ref "R17") (pin "2") (pinfunction "2_2") (pintype "passive"))
    )
    (net (code "24") (name "EXT_OUT6") (class "Default")
      (node (ref "PL3") (pin "12") (pinfunction "TB_12") (pintype "bidirectional"))
      (node (ref "R24") (pin "2") (pinfunction "2_2") (pintype "passive"))
    )
    (net (code "25") (name "EXT_OUT7") (class "Default")
      (node (ref "PL4") (pin "13") (pinfunction "TT_13") (pintype "bidirectional"))
      (node (ref "R25") (pin "2") (pinfunction "2_2") (pintype "passive"))
    )
    (net (code "26") (name "EXT_OUT8") (class "Default")
      (node (ref "PL4") (pin "12") (pinfunction "TB_12") (pintype "bidirectional"))
      (node (ref "R32") (pin "2") (pinfunction "2_2") (pintype "passive"))
    )
    (net (code "27") (name "EXT_OUT9") (class "Default")
      (node (ref "PL5") (pin "13") (pinfunction "TT_13") (pintype "bidirectional"))
      (node (ref "R33") (pin "2") (pinfunction "2_2") (pintype "passive"))
    )
    (net (code "28") (name "EXT_OUT10") (class "Default")
      (node (ref "PL5") (pin "12") (pinfunction "TB_12") (pintype "bidirectional"))
      (node (ref "R40") (pin "2") (pinfunction "2_2") (pintype "passive"))
    )
    (net (code "29") (name "EXT_OUT11") (class "Default")
      (node (ref "PL6") (pin "13") (pinfunction "TT_13") (pintype "bidirectional"))
      (node (ref "R41") (pin "2") (pinfunction "2_2") (pintype "passive"))
    )
    (net (code "30") (name "EXT_OUT12") (class "Default")
      (node (ref "PL6") (pin "12") (pinfunction "TB_12") (pintype "bidirectional"))
      (node (ref "R48") (pin "2") (pinfunction "2_2") (pintype "passive"))
    )
    (net (code "31") (name "GND") (class "Default")
      (node (ref "C10") (pin "2") (pinfunction "P$2_2") (pintype "passive"))
      (node (ref "C100") (pin "1") (pinfunction "P$1_1") (pintype "passive"))
      (node (ref "C101") (pin "1") (pinfunction "P$1_1") (pintype "passive"))
      (node (ref "C102") (pin "2") (pinfunction "P$2_2") (pintype "passive"))
      (node (ref "C103") (pin "2") (pinfunction "P$2_2") (pintype "passive"))
      (node (ref "C12") (pin "2") (pinfunction "P$2_2") (pintype "passive"))
      (node (ref "C14") (pin "2") (pinfunction "P$2_2") (pintype "passive"))
      (node (ref "C16") (pin "1") (pinfunction "P$1_1") (pintype "passive"))
      (node (ref "C18") (pin "2") (pinfunction "P$2_2") (pintype "passive"))
      (node (ref "C2") (pin "2") (pinfunction "P$2_2") (pintype "passive"))
      (node (ref "C20") (pin "2") (pinfunction "P$2_2") (pintype "passive"))
      (node (ref "C22") (pin "2") (pinfunction "P$2_2") (pintype "passive"))
      (node (ref "C24") (pin "1") (pinfunction "P$1_1") (pintype "passive"))
      (node (ref "C26") (pin "2") (pinfunction "P$2_2") (pintype "passive"))
      (node (ref "C28") (pin "2") (pinfunction "P$2_2") (pintype "passive"))
      (node (ref "C30") (pin "2") (pinfunction "P$2_2") (pintype "passive"))
      (node (ref "C32") (pin "1") (pinfunction "P$1_1") (pintype "passive"))
      (node (ref "C34") (pin "2") (pinfunction "P$2_2") (pintype "passive"))
      (node (ref "C36") (pin "2") (pinfunction "P$2_2") (pintype "passive"))
      (node (ref "C38") (pin "2") (pinfunction "P$2_2") (pintype "passive"))
      (node (ref "C4") (pin "2") (pinfunction "P$2_2") (pintype "passive"))
      (node (ref "C40") (pin "1") (pinfunction "P$1_1") (pintype "passive"))
      (node (ref "C42") (pin "2") (pinfunction "P$2_2") (pintype "passive"))
      (node (ref "C44") (pin "2") (pinfunction "P$2_2") (pintype "passive"))
      (node (ref "C46") (pin "2") (pinfunction "P$2_2") (pintype "passive"))
      (node (ref "C48") (pin "1") (pinfunction "P$1_1") (pintype "passive"))
      (node (ref "C49") (pin "1") (pinfunction "P$1_1") (pintype "passive"))
      (node (ref "C50") (pin "1") (pinfunction "P$1_1") (pintype "passive"))
      (node (ref "C51") (pin "1") (pinfunction "P$1_1") (pintype "passive"))
      (node (ref "C52") (pin "1") (pinfunction "P$1_1") (pintype "passive"))
      (node (ref "C53") (pin "1") (pinfunction "P$1_1") (pintype "passive"))
      (node (ref "C54") (pin "1") (pinfunction "P$1_1") (pintype "passive"))
      (node (ref "C55") (pin "1") (pinfunction "P$1_1") (pintype "passive"))
      (node (ref "C56") (pin "1") (pinfunction "P$1_1") (pintype "passive"))
      (node (ref "C57") (pin "1") (pinfunction "P$1_1") (pintype "passive"))
      (node (ref "C58") (pin "1") (pinfunction "P$1_1") (pintype "passive"))
      (node (ref "C59") (pin "1") (pinfunction "P$1_1") (pintype "passive"))
      (node (ref "C6") (pin "2") (pinfunction "P$2_2") (pintype "passive"))
      (node (ref "C60") (pin "1") (pinfunction "P$1_1") (pintype "passive"))
      (node (ref "C61") (pin "1") (pinfunction "P$1_1") (pintype "passive"))
      (node (ref "C62") (pin "1") (pinfunction "P$1_1") (pintype "passive"))
      (node (ref "C63") (pin "1") (pinfunction "P$1_1") (pintype "passive"))
      (node (ref "C64") (pin "1") (pinfunction "P$1_1") (pintype "passive"))
      (node (ref "C65") (pin "1") (pinfunction "P$1_1") (pintype "passive"))
      (node (ref "C66") (pin "1") (pinfunction "P$1_1") (pintype "passive"))
      (node (ref "C67") (pin "1") (pinfunction "P$1_1") (pintype "passive"))
      (node (ref "C68") (pin "1") (pinfunction "P$1_1") (pintype "passive"))
      (node (ref "C69") (pin "1") (pinfunction "P$1_1") (pintype "passive"))
      (node (ref "C70") (pin "1") (pinfunction "P$1_1") (pintype "passive"))
      (node (ref "C71") (pin "2") (pinfunction "P$2_2") (pintype "passive"))
      (node (ref "C72") (pin "1") (pinfunction "P$1_1") (pintype "passive"))
      (node (ref "C73") (pin "2") (pinfunction "P$2_2") (pintype "passive"))
      (node (ref "C74") (pin "1") (pinfunction "P$1_1") (pintype "passive"))
      (node (ref "C75") (pin "1") (pinfunction "P$1_1") (pintype "passive"))
      (node (ref "C76") (pin "1") (pinfunction "P$1_1") (pintype "passive"))
      (node (ref "C77") (pin "-") (pinfunction "-_-") (pintype "passive"))
      (node (ref "C78") (pin "1") (pinfunction "P$1_1") (pintype "passive"))
      (node (ref "C79") (pin "1") (pinfunction "P$1_1") (pintype "passive"))
      (node (ref "C8") (pin "1") (pinfunction "P$1_1") (pintype "passive"))
      (node (ref "C80") (pin "1") (pinfunction "P$1_1") (pintype "passive"))
      (node (ref "C81") (pin "-") (pinfunction "-_-") (pintype "passive"))
      (node (ref "C82") (pin "-") (pinfunction "-_-") (pintype "passive"))
      (node (ref "C83") (pin "-") (pinfunction "-_-") (pintype "passive"))
      (node (ref "C84") (pin "1") (pinfunction "P$1_1") (pintype "passive"))
      (node (ref "C85") (pin "1") (pinfunction "P$1_1") (pintype "passive"))
      (node (ref "C86") (pin "1") (pinfunction "P$1_1") (pintype "passive"))
      (node (ref "C87") (pin "-") (pinfunction "-_-") (pintype "passive"))
      (node (ref "C88") (pin "-") (pinfunction "-_-") (pintype "passive"))
      (node (ref "C89") (pin "-") (pinfunction "-_-") (pintype "passive"))
      (node (ref "C90") (pin "1") (pinfunction "P$1_1") (pintype "passive"))
      (node (ref "C91") (pin "1") (pinfunction "P$1_1") (pintype "passive"))
      (node (ref "C92") (pin "-") (pinfunction "-_-") (pintype "passive"))
      (node (ref "C93") (pin "-") (pinfunction "-_-") (pintype "passive"))
      (node (ref "C94") (pin "1") (pinfunction "P$1_1") (pintype "passive"))
      (node (ref "C95") (pin "2") (pinfunction "P$2_2") (pintype "passive"))
      (node (ref "C96") (pin "2") (pinfunction "P$2_2") (pintype "passive"))
      (node (ref "C97") (pin "2") (pinfunction "P$2_2") (pintype "passive"))
      (node (ref "C98") (pin "2") (pinfunction "P$2_2") (pintype "passive"))
      (node (ref "C99") (pin "1") (pinfunction "P$1_1") (pintype "passive"))
      (node (ref "IC1") (pin "3") (pinfunction "+IN_3") (pintype "input"))
      (node (ref "IC1") (pin "5") (pinfunction "+IN_5") (pintype "input"))
      (node (ref "IC2") (pin "3") (pinfunction "+IN_3") (pintype "input"))
      (node (ref "IC2") (pin "5") (pinfunction "+IN_5") (pintype "input"))
      (node (ref "IC3") (pin "3") (pinfunction "+IN_3") (pintype "input"))
      (node (ref "IC3") (pin "5") (pinfunction "+IN_5") (pintype "input"))
      (node (ref "IC4") (pin "3") (pinfunction "+IN_3") (pintype "input"))
      (node (ref "IC4") (pin "5") (pinfunction "+IN_5") (pintype "input"))
      (node (ref "IC5") (pin "3") (pinfunction "+IN_3") (pintype "input"))
      (node (ref "IC5") (pin "5") (pinfunction "+IN_5") (pintype "input"))
      (node (ref "IC6") (pin "3") (pinfunction "+IN_3") (pintype "input"))
      (node (ref "IC6") (pin "5") (pinfunction "+IN_5") (pintype "input"))
      (node (ref "IC7") (pin "7") (pinfunction "GND_7") (pintype "power_in"))
      (node (ref "JP2") (pin "1") (pinfunction "1_1") (pintype "passive"))
      (node (ref "JP3") (pin "3") (pinfunction "3_3") (pintype "passive"))
      (node (ref "JP6") (pin "6") (pinfunction "2_6") (pintype "passive"))
      (node (ref "JP7") (pin "1") (pinfunction "1_1") (pintype "passive"))
      (node (ref "LED1") (pin "C1") (pinfunction "K_1_C1") (pintype "bidirectional"))
      (node (ref "LED1") (pin "C2") (pinfunction "K_2_C2") (pintype "bidirectional"))
      (node (ref "LED1") (pin "C3") (pinfunction "K_3_C3") (pintype "bidirectional"))
      (node (ref "LED2") (pin "C") (pinfunction "C_C") (pintype "passive"))
      (node (ref "OSC1") (pin "2") (pinfunction "GND_2") (pintype "power_in"))
      (node (ref "PL1") (pin "10") (pinfunction "RB_10") (pintype "bidirectional"))
      (node (ref "PL1") (pin "11") (pinfunction "RT_11") (pintype "bidirectional"))
      (node (ref "PL1") (pin "8") (pinfunction "SB_8") (pintype "bidirectional"))
      (node (ref "PL1") (pin "9") (pinfunction "ST_9") (pintype "bidirectional"))
      (node (ref "PL2") (pin "10") (pinfunction "RB_10") (pintype "bidirectional"))
      (node (ref "PL2") (pin "11") (pinfunction "RT_11") (pintype "bidirectional"))
      (node (ref "PL2") (pin "8") (pinfunction "SB_8") (pintype "bidirectional"))
      (node (ref "PL2") (pin "9") (pinfunction "ST_9") (pintype "bidirectional"))
      (node (ref "PL3") (pin "10") (pinfunction "RB_10") (pintype "bidirectional"))
      (node (ref "PL3") (pin "11") (pinfunction "RT_11") (pintype "bidirectional"))
      (node (ref "PL3") (pin "8") (pinfunction "SB_8") (pintype "bidirectional"))
      (node (ref "PL3") (pin "9") (pinfunction "ST_9") (pintype "bidirectional"))
      (node (ref "PL4") (pin "10") (pinfunction "RB_10") (pintype "bidirectional"))
      (node (ref "PL4") (pin "11") (pinfunction "RT_11") (pintype "bidirectional"))
      (node (ref "PL4") (pin "8") (pinfunction "SB_8") (pintype "bidirectional"))
      (node (ref "PL4") (pin "9") (pinfunction "ST_9") (pintype "bidirectional"))
      (node (ref "PL5") (pin "10") (pinfunction "RB_10") (pintype "bidirectional"))
      (node (ref "PL5") (pin "11") (pinfunction "RT_11") (pintype "bidirectional"))
      (node (ref "PL5") (pin "8") (pinfunction "SB_8") (pintype "bidirectional"))
      (node (ref "PL5") (pin "9") (pinfunction "ST_9") (pintype "bidirectional"))
      (node (ref "PL6") (pin "10") (pinfunction "RB_10") (pintype "bidirectional"))
      (node (ref "PL6") (pin "11") (pinfunction "RT_11") (pintype "bidirectional"))
      (node (ref "PL6") (pin "8") (pinfunction "SB_8") (pintype "bidirectional"))
      (node (ref "PL6") (pin "9") (pinfunction "ST_9") (pintype "bidirectional"))
      (node (ref "R102") (pin "2") (pinfunction "2_2") (pintype "passive"))
      (node (ref "R103") (pin "2") (pinfunction "2_2") (pintype "passive"))
      (node (ref "R104") (pin "2") (pinfunction "2_2") (pintype "passive"))
      (node (ref "R105") (pin "2") (pinfunction "2_2") (pintype "passive"))
      (node (ref "R52") (pin "2") (pinfunction "2_2") (pintype "passive"))
      (node (ref "R54") (pin "2") (pinfunction "2_2") (pintype "passive"))
      (node (ref "R57") (pin "1") (pinfunction "1_1") (pintype "passive"))
      (node (ref "R58") (pin "1") (pinfunction "1_1") (pintype "passive"))
      (node (ref "R65") (pin "1") (pinfunction "1_1") (pintype "passive"))
      (node (ref "R68") (pin "1") (pinfunction "1_1") (pintype "passive"))
      (node (ref "R72") (pin "1") (pinfunction "1_1") (pintype "passive"))
      (node (ref "R73") (pin "2") (pinfunction "2_2") (pintype "passive"))
      (node (ref "R74") (pin "2") (pinfunction "2_2") (pintype "passive"))
      (node (ref "R77") (pin "1") (pinfunction "1_1") (pintype "passive"))
      (node (ref "R83") (pin "1") (pinfunction "1_1") (pintype "passive"))
      (node (ref "R84") (pin "1") (pinfunction "1_1") (pintype "passive"))
      (node (ref "R85") (pin "2") (pinfunction "2_2") (pintype "passive"))
      (node (ref "R86") (pin "2") (pinfunction "2_2") (pintype "passive"))
      (node (ref "R95") (pin "1") (pinfunction "1_1") (pintype "passive"))
      (node (ref "R96") (pin "2") (pinfunction "2_2") (pintype "passive"))
      (node (ref "TC1") (pin "3") (pinfunction "3_3") (pintype "passive"))
      (node (ref "TC1") (pin "5") (pinfunction "5_5") (pintype "passive"))
      (node (ref "TC1") (pin "9") (pinfunction "9_9") (pintype "passive"))
      (node (ref "TP16") (pin "TP") (pinfunction "TP_TP") (pintype "input"))
      (node (ref "TP17") (pin "TP") (pinfunction "TP_TP") (pintype "input"))
      (node (ref "TP18") (pin "TP") (pinfunction "TP_TP") (pintype "input"))
      (node (ref "TP2") (pin "TP") (pinfunction "TP_TP") (pintype "input"))
      (node (ref "TP5") (pin "TP") (pinfunction "TP_TP") (pintype "input"))
      (node (ref "U$1") (pin "LED-") (pinfunction "LED-_LED-") (pintype "passive"))
      (node (ref "U$1") (pin "P$3") (pinfunction "OUT1_NO_P$3") (pintype "passive"))
      (node (ref "U$1") (pin "P$6") (pinfunction "OUT2_NO_P$6") (pintype "passive"))
      (node (ref "U1") (pin "1") (pinfunction "ADJ_1") (pintype "input"))
      (node (ref "U2") (pin "2") (pinfunction "-VIN_2") (pintype "input"))
      (node (ref "U3") (pin "107") (pinfunction "VSS_8_107") (pintype "power_in"))
      (node (ref "U3") (pin "120") (pinfunction "VSS_9_120") (pintype "power_in"))
      (node (ref "U3") (pin "130") (pinfunction "VSS_130") (pintype "power_in"))
      (node (ref "U3") (pin "16") (pinfunction "VSS_2_16") (pintype "power_in"))
      (node (ref "U3") (pin "31") (pinfunction "VSSA_31") (pintype "power_in"))
      (node (ref "U3") (pin "38") (pinfunction "VSS_3_38") (pintype "power_in"))
      (node (ref "U3") (pin "51") (pinfunction "VSS_4_51") (pintype "power_in"))
      (node (ref "U3") (pin "61") (pinfunction "VSS_5_61") (pintype "power_in"))
      (node (ref "U3") (pin "85") (pinfunction "VSS_6_85") (pintype "power_in"))
      (node (ref "U3") (pin "94") (pinfunction "VSS_7_94") (pintype "power_in"))
      (node (ref "U4") (pin "2") (pinfunction "GND_2") (pintype "power_in"))
      (node (ref "U5") (pin "2") (pinfunction "GND_2") (pintype "power_in"))
      (node (ref "U6") (pin "10") (pinfunction "DGND_10") (pintype "power_in"))
      (node (ref "U6") (pin "18") (pinfunction "AGND1_18") (pintype "power_in"))
      (node (ref "U6") (pin "24") (pinfunction "AGND2_24") (pintype "power_in"))
      (node (ref "U6") (pin "29") (pinfunction "EPAD_29") (pintype "passive"))
      (node (ref "U7") (pin "10") (pinfunction "DGND_10") (pintype "power_in"))
      (node (ref "U7") (pin "18") (pinfunction "AGND1_18") (pintype "power_in"))
      (node (ref "U7") (pin "24") (pinfunction "AGND2_24") (pintype "power_in"))
      (node (ref "U7") (pin "29") (pinfunction "EPAD_29") (pintype "passive"))
      (node (ref "USB_FS") (pin "4") (pinfunction "4_4") (pintype "bidirectional"))
      (node (ref "USB_HS") (pin "P$4") (pinfunction "4_P$4") (pintype "passive"))
    )
    (net (code "32") (name "I2C_SCL") (class "Default")
      (node (ref "JP4") (pin "3") (pinfunction "3_3") (pintype "passive"))
      (node (ref "JP9") (pin "3") (pinfunction "3_3") (pintype "passive"))
      (node (ref "R93") (pin "1") (pinfunction "1_1") (pintype "passive"))
      (node (ref "U3") (pin "139") (pinfunction "PB8_139") (pintype "bidirectional"))
    )
    (net (code "33") (name "I2C_SDA") (class "Default")
      (node (ref "JP10") (pin "3") (pinfunction "3_3") (pintype "passive"))
      (node (ref "JP5") (pin "3") (pinfunction "3_3") (pintype "passive"))
      (node (ref "R92") (pin "1") (pinfunction "1_1") (pintype "passive"))
      (node (ref "U3") (pin "137") (pinfunction "PB7_137") (pintype "bidirectional"))
    )
    (net (code "34") (name "I2S_CKIN") (class "Default")
      (node (ref "R56") (pin "2") (pinfunction "2_2") (pintype "passive"))
      (node (ref "U3") (pin "99") (pinfunction "PC9_99") (pintype "bidirectional"))
    )
    (net (code "35") (name "LED1") (class "Default")
      (node (ref "R98") (pin "2") (pinfunction "2_2") (pintype "passive"))
      (node (ref "U3") (pin "113") (pinfunction "PC12_113") (pintype "bidirectional"))
    )
    (net (code "36") (name "LED2") (class "Default")
      (node (ref "R99") (pin "2") (pinfunction "2_2") (pintype "passive"))
      (node (ref "U3") (pin "112") (pinfunction "PC11_112") (pintype "bidirectional"))
    )
    (net (code "37") (name "LED3") (class "Default")
      (node (ref "R100") (pin "2") (pinfunction "2_2") (pintype "passive"))
      (node (ref "U3") (pin "111") (pinfunction "PC10_111") (pintype "bidirectional"))
    )
    (net (code "38") (name "LED4") (class "Default")
      (node (ref "R101") (pin "1") (pinfunction "1_1") (pintype "passive"))
      (node (ref "U3") (pin "114") (pinfunction "PD0_114") (pintype "bidirectional"))
    )
    (net (code "39") (name "NRST") (class "Default")
      (node (ref "C71") (pin "1") (pinfunction "P$1_1") (pintype "passive"))
      (node (ref "R53") (pin "1") (pinfunction "1_1") (pintype "passive"))
      (node (ref "TC1") (pin "10") (pinfunction "10_10") (pintype "passive"))
      (node (ref "U3") (pin "25") (pinfunction "NRST_25") (pintype "bidirectional"))
    )
    (net (code "40") (name "Net-(APWR_EN-Pad2)") (class "Default")
      (node (ref "APWR_EN") (pin "2") (pinfunction "2_2") (pintype "passive"))
      (node (ref "L5") (pin "2") (pinfunction "2_2") (pintype "passive"))
    )
    (net (code "41") (name "Net-(APWR_ENB-2)") (class "Default")
      (node (ref "APWR_EN") (pin "4") (pinfunction "2_4") (pintype "passive"))
      (node (ref "L6") (pin "2") (pinfunction "2_2") (pintype "passive"))
    )
    (net (code "42") (name "Net-(C1-P$1)") (class "Default")
      (node (ref "C1") (pin "1") (pinfunction "P$1_1") (pintype "passive"))
      (node (ref "IC1") (pin "1") (pinfunction "OUT_1") (pintype "output"))
      (node (ref "R1") (pin "1") (pinfunction "1_1") (pintype "passive"))
      (node (ref "R3") (pin "2") (pinfunction "2_2") (pintype "passive"))
    )
    (net (code "43") (name "Net-(C1-P$2)") (class "Default")
      (node (ref "C1") (pin "2") (pinfunction "P$2_2") (pintype "passive"))
      (node (ref "IC1") (pin "2") (pinfunction "-IN_2") (pintype "input"))
      (node (ref "R2") (pin "2") (pinfunction "2_2") (pintype "passive"))
    )
    (net (code "44") (name "Net-(C2-P$1)") (class "Default")
      (node (ref "C2") (pin "1") (pinfunction "P$1_1") (pintype "passive"))
      (node (ref "R2") (pin "1") (pinfunction "1_1") (pintype "passive"))
      (node (ref "R3") (pin "1") (pinfunction "1_1") (pintype "passive"))
      (node (ref "R4") (pin "1") (pinfunction "1_1") (pintype "passive"))
    )
    (net (code "45") (name "Net-(C3-Pad-)") (class "Default")
      (node (ref "C3") (pin "-") (pinfunction "-_-") (pintype "passive"))
      (node (ref "R4") (pin "2") (pinfunction "2_2") (pintype "passive"))
    )
    (net (code "46") (name "Net-(C5-P$1)") (class "Default")
      (node (ref "C5") (pin "1") (pinfunction "P$1_1") (pintype "passive"))
      (node (ref "IC1") (pin "7") (pinfunction "OUT_7") (pintype "output"))
      (node (ref "R6") (pin "2") (pinfunction "2_2") (pintype "passive"))
      (node (ref "R8") (pin "1") (pinfunction "1_1") (pintype "passive"))
    )
    (net (code "47") (name "Net-(C5-P$2)") (class "Default")
      (node (ref "C5") (pin "2") (pinfunction "P$2_2") (pintype "passive"))
      (node (ref "IC1") (pin "6") (pinfunction "-IN_6") (pintype "input"))
      (node (ref "R5") (pin "2") (pinfunction "2_2") (pintype "passive"))
    )
    (net (code "48") (name "Net-(C6-P$1)") (class "Default")
      (node (ref "C6") (pin "1") (pinfunction "P$1_1") (pintype "passive"))
      (node (ref "R5") (pin "1") (pinfunction "1_1") (pintype "passive"))
      (node (ref "R6") (pin "1") (pinfunction "1_1") (pintype "passive"))
      (node (ref "R7") (pin "1") (pinfunction "1_1") (pintype "passive"))
    )
    (net (code "49") (name "Net-(C7-Pad-)") (class "Default")
      (node (ref "C7") (pin "-") (pinfunction "-_-") (pintype "passive"))
      (node (ref "R7") (pin "2") (pinfunction "2_2") (pintype "passive"))
    )
    (net (code "50") (name "Net-(C9-P$1)") (class "Default")
      (node (ref "C9") (pin "1") (pinfunction "P$1_1") (pintype "passive"))
      (node (ref "IC2") (pin "1") (pinfunction "OUT_1") (pintype "output"))
      (node (ref "R11") (pin "2") (pinfunction "2_2") (pintype "passive"))
      (node (ref "R9") (pin "1") (pinfunction "1_1") (pintype "passive"))
    )
    (net (code "51") (name "Net-(C9-P$2)") (class "Default")
      (node (ref "C9") (pin "2") (pinfunction "P$2_2") (pintype "passive"))
      (node (ref "IC2") (pin "2") (pinfunction "-IN_2") (pintype "input"))
      (node (ref "R10") (pin "2") (pinfunction "2_2") (pintype "passive"))
    )
    (net (code "52") (name "Net-(C10-P$1)") (class "Default")
      (node (ref "C10") (pin "1") (pinfunction "P$1_1") (pintype "passive"))
      (node (ref "R10") (pin "1") (pinfunction "1_1") (pintype "passive"))
      (node (ref "R11") (pin "1") (pinfunction "1_1") (pintype "passive"))
      (node (ref "R12") (pin "1") (pinfunction "1_1") (pintype "passive"))
    )
    (net (code "53") (name "Net-(C11-Pad-)") (class "Default")
      (node (ref "C11") (pin "-") (pinfunction "-_-") (pintype "passive"))
      (node (ref "R12") (pin "2") (pinfunction "2_2") (pintype "passive"))
    )
    (net (code "54") (name "Net-(C13-P$1)") (class "Default")
      (node (ref "C13") (pin "1") (pinfunction "P$1_1") (pintype "passive"))
      (node (ref "IC2") (pin "7") (pinfunction "OUT_7") (pintype "output"))
      (node (ref "R14") (pin "2") (pinfunction "2_2") (pintype "passive"))
      (node (ref "R16") (pin "1") (pinfunction "1_1") (pintype "passive"))
    )
    (net (code "55") (name "Net-(C13-P$2)") (class "Default")
      (node (ref "C13") (pin "2") (pinfunction "P$2_2") (pintype "passive"))
      (node (ref "IC2") (pin "6") (pinfunction "-IN_6") (pintype "input"))
      (node (ref "R13") (pin "2") (pinfunction "2_2") (pintype "passive"))
    )
    (net (code "56") (name "Net-(C14-P$1)") (class "Default")
      (node (ref "C14") (pin "1") (pinfunction "P$1_1") (pintype "passive"))
      (node (ref "R13") (pin "1") (pinfunction "1_1") (pintype "passive"))
      (node (ref "R14") (pin "1") (pinfunction "1_1") (pintype "passive"))
      (node (ref "R15") (pin "1") (pinfunction "1_1") (pintype "passive"))
    )
    (net (code "57") (name "Net-(C15-Pad-)") (class "Default")
      (node (ref "C15") (pin "-") (pinfunction "-_-") (pintype "passive"))
      (node (ref "R15") (pin "2") (pinfunction "2_2") (pintype "passive"))
    )
    (net (code "58") (name "Net-(C17-P$1)") (class "Default")
      (node (ref "C17") (pin "1") (pinfunction "P$1_1") (pintype "passive"))
      (node (ref "IC3") (pin "1") (pinfunction "OUT_1") (pintype "output"))
      (node (ref "R17") (pin "1") (pinfunction "1_1") (pintype "passive"))
      (node (ref "R19") (pin "2") (pinfunction "2_2") (pintype "passive"))
    )
    (net (code "59") (name "Net-(C17-P$2)") (class "Default")
      (node (ref "C17") (pin "2") (pinfunction "P$2_2") (pintype "passive"))
      (node (ref "IC3") (pin "2") (pinfunction "-IN_2") (pintype "input"))
      (node (ref "R18") (pin "2") (pinfunction "2_2") (pintype "passive"))
    )
    (net (code "60") (name "Net-(C18-P$1)") (class "Default")
      (node (ref "C18") (pin "1") (pinfunction "P$1_1") (pintype "passive"))
      (node (ref "R18") (pin "1") (pinfunction "1_1") (pintype "passive"))
      (node (ref "R19") (pin "1") (pinfunction "1_1") (pintype "passive"))
      (node (ref "R20") (pin "1") (pinfunction "1_1") (pintype "passive"))
    )
    (net (code "61") (name "Net-(C19-Pad-)") (class "Default")
      (node (ref "C19") (pin "-") (pinfunction "-_-") (pintype "passive"))
      (node (ref "R20") (pin "2") (pinfunction "2_2") (pintype "passive"))
    )
    (net (code "62") (name "Net-(C21-P$1)") (class "Default")
      (node (ref "C21") (pin "1") (pinfunction "P$1_1") (pintype "passive"))
      (node (ref "IC3") (pin "7") (pinfunction "OUT_7") (pintype "output"))
      (node (ref "R22") (pin "2") (pinfunction "2_2") (pintype "passive"))
      (node (ref "R24") (pin "1") (pinfunction "1_1") (pintype "passive"))
    )
    (net (code "63") (name "Net-(C21-P$2)") (class "Default")
      (node (ref "C21") (pin "2") (pinfunction "P$2_2") (pintype "passive"))
      (node (ref "IC3") (pin "6") (pinfunction "-IN_6") (pintype "input"))
      (node (ref "R21") (pin "2") (pinfunction "2_2") (pintype "passive"))
    )
    (net (code "64") (name "Net-(C22-P$1)") (class "Default")
      (node (ref "C22") (pin "1") (pinfunction "P$1_1") (pintype "passive"))
      (node (ref "R21") (pin "1") (pinfunction "1_1") (pintype "passive"))
      (node (ref "R22") (pin "1") (pinfunction "1_1") (pintype "passive"))
      (node (ref "R23") (pin "1") (pinfunction "1_1") (pintype "passive"))
    )
    (net (code "65") (name "Net-(C23-Pad-)") (class "Default")
      (node (ref "C23") (pin "-") (pinfunction "-_-") (pintype "passive"))
      (node (ref "R23") (pin "2") (pinfunction "2_2") (pintype "passive"))
    )
    (net (code "66") (name "Net-(C25-P$1)") (class "Default")
      (node (ref "C25") (pin "1") (pinfunction "P$1_1") (pintype "passive"))
      (node (ref "IC4") (pin "1") (pinfunction "OUT_1") (pintype "output"))
      (node (ref "R25") (pin "1") (pinfunction "1_1") (pintype "passive"))
      (node (ref "R27") (pin "2") (pinfunction "2_2") (pintype "passive"))
    )
    (net (code "67") (name "Net-(C25-P$2)") (class "Default")
      (node (ref "C25") (pin "2") (pinfunction "P$2_2") (pintype "passive"))
      (node (ref "IC4") (pin "2") (pinfunction "-IN_2") (pintype "input"))
      (node (ref "R26") (pin "2") (pinfunction "2_2") (pintype "passive"))
    )
    (net (code "68") (name "Net-(C26-P$1)") (class "Default")
      (node (ref "C26") (pin "1") (pinfunction "P$1_1") (pintype "passive"))
      (node (ref "R26") (pin "1") (pinfunction "1_1") (pintype "passive"))
      (node (ref "R27") (pin "1") (pinfunction "1_1") (pintype "passive"))
      (node (ref "R28") (pin "1") (pinfunction "1_1") (pintype "passive"))
    )
    (net (code "69") (name "Net-(C27-Pad-)") (class "Default")
      (node (ref "C27") (pin "-") (pinfunction "-_-") (pintype "passive"))
      (node (ref "R28") (pin "2") (pinfunction "2_2") (pintype "passive"))
    )
    (net (code "70") (name "Net-(C29-P$1)") (class "Default")
      (node (ref "C29") (pin "1") (pinfunction "P$1_1") (pintype "passive"))
      (node (ref "IC4") (pin "7") (pinfunction "OUT_7") (pintype "output"))
      (node (ref "R30") (pin "2") (pinfunction "2_2") (pintype "passive"))
      (node (ref "R32") (pin "1") (pinfunction "1_1") (pintype "passive"))
    )
    (net (code "71") (name "Net-(C29-P$2)") (class "Default")
      (node (ref "C29") (pin "2") (pinfunction "P$2_2") (pintype "passive"))
      (node (ref "IC4") (pin "6") (pinfunction "-IN_6") (pintype "input"))
      (node (ref "R29") (pin "2") (pinfunction "2_2") (pintype "passive"))
    )
    (net (code "72") (name "Net-(C30-P$1)") (class "Default")
      (node (ref "C30") (pin "1") (pinfunction "P$1_1") (pintype "passive"))
      (node (ref "R29") (pin "1") (pinfunction "1_1") (pintype "passive"))
      (node (ref "R30") (pin "1") (pinfunction "1_1") (pintype "passive"))
      (node (ref "R31") (pin "1") (pinfunction "1_1") (pintype "passive"))
    )
    (net (code "73") (name "Net-(C31-Pad-)") (class "Default")
      (node (ref "C31") (pin "-") (pinfunction "-_-") (pintype "passive"))
      (node (ref "R31") (pin "2") (pinfunction "2_2") (pintype "passive"))
    )
    (net (code "74") (name "Net-(C33-P$1)") (class "Default")
      (node (ref "C33") (pin "1") (pinfunction "P$1_1") (pintype "passive"))
      (node (ref "IC5") (pin "1") (pinfunction "OUT_1") (pintype "output"))
      (node (ref "R33") (pin "1") (pinfunction "1_1") (pintype "passive"))
      (node (ref "R35") (pin "2") (pinfunction "2_2") (pintype "passive"))
    )
    (net (code "75") (name "Net-(C33-P$2)") (class "Default")
      (node (ref "C33") (pin "2") (pinfunction "P$2_2") (pintype "passive"))
      (node (ref "IC5") (pin "2") (pinfunction "-IN_2") (pintype "input"))
      (node (ref "R34") (pin "2") (pinfunction "2_2") (pintype "passive"))
    )
    (net (code "76") (name "Net-(C34-P$1)") (class "Default")
      (node (ref "C34") (pin "1") (pinfunction "P$1_1") (pintype "passive"))
      (node (ref "R34") (pin "1") (pinfunction "1_1") (pintype "passive"))
      (node (ref "R35") (pin "1") (pinfunction "1_1") (pintype "passive"))
      (node (ref "R36") (pin "1") (pinfunction "1_1") (pintype "passive"))
    )
    (net (code "77") (name "Net-(C35-Pad-)") (class "Default")
      (node (ref "C35") (pin "-") (pinfunction "-_-") (pintype "passive"))
      (node (ref "R36") (pin "2") (pinfunction "2_2") (pintype "passive"))
    )
    (net (code "78") (name "Net-(C37-P$1)") (class "Default")
      (node (ref "C37") (pin "1") (pinfunction "P$1_1") (pintype "passive"))
      (node (ref "IC5") (pin "7") (pinfunction "OUT_7") (pintype "output"))
      (node (ref "R38") (pin "2") (pinfunction "2_2") (pintype "passive"))
      (node (ref "R40") (pin "1") (pinfunction "1_1") (pintype "passive"))
    )
    (net (code "79") (name "Net-(C37-P$2)") (class "Default")
      (node (ref "C37") (pin "2") (pinfunction "P$2_2") (pintype "passive"))
      (node (ref "IC5") (pin "6") (pinfunction "-IN_6") (pintype "input"))
      (node (ref "R37") (pin "2") (pinfunction "2_2") (pintype "passive"))
    )
    (net (code "80") (name "Net-(C38-P$1)") (class "Default")
      (node (ref "C38") (pin "1") (pinfunction "P$1_1") (pintype "passive"))
      (node (ref "R37") (pin "1") (pinfunction "1_1") (pintype "passive"))
      (node (ref "R38") (pin "1") (pinfunction "1_1") (pintype "passive"))
      (node (ref "R39") (pin "1") (pinfunction "1_1") (pintype "passive"))
    )
    (net (code "81") (name "Net-(C39-Pad-)") (class "Default")
      (node (ref "C39") (pin "-") (pinfunction "-_-") (pintype "passive"))
      (node (ref "R39") (pin "2") (pinfunction "2_2") (pintype "passive"))
    )
    (net (code "82") (name "Net-(C41-P$1)") (class "Default")
      (node (ref "C41") (pin "1") (pinfunction "P$1_1") (pintype "passive"))
      (node (ref "IC6") (pin "1") (pinfunction "OUT_1") (pintype "output"))
      (node (ref "R41") (pin "1") (pinfunction "1_1") (pintype "passive"))
      (node (ref "R43") (pin "2") (pinfunction "2_2") (pintype "passive"))
    )
    (net (code "83") (name "Net-(C41-P$2)") (class "Default")
      (node (ref "C41") (pin "2") (pinfunction "P$2_2") (pintype "passive"))
      (node (ref "IC6") (pin "2") (pinfunction "-IN_2") (pintype "input"))
      (node (ref "R42") (pin "2") (pinfunction "2_2") (pintype "passive"))
    )
    (net (code "84") (name "Net-(C42-P$1)") (class "Default")
      (node (ref "C42") (pin "1") (pinfunction "P$1_1") (pintype "passive"))
      (node (ref "R42") (pin "1") (pinfunction "1_1") (pintype "passive"))
      (node (ref "R43") (pin "1") (pinfunction "1_1") (pintype "passive"))
      (node (ref "R44") (pin "1") (pinfunction "1_1") (pintype "passive"))
    )
    (net (code "85") (name "Net-(C43-Pad-)") (class "Default")
      (node (ref "C43") (pin "-") (pinfunction "-_-") (pintype "passive"))
      (node (ref "R44") (pin "2") (pinfunction "2_2") (pintype "passive"))
    )
    (net (code "86") (name "Net-(C45-P$1)") (class "Default")
      (node (ref "C45") (pin "1") (pinfunction "P$1_1") (pintype "passive"))
      (node (ref "IC6") (pin "7") (pinfunction "OUT_7") (pintype "output"))
      (node (ref "R46") (pin "2") (pinfunction "2_2") (pintype "passive"))
      (node (ref "R48") (pin "1") (pinfunction "1_1") (pintype "passive"))
    )
    (net (code "87") (name "Net-(C45-P$2)") (class "Default")
      (node (ref "C45") (pin "2") (pinfunction "P$2_2") (pintype "passive"))
      (node (ref "IC6") (pin "6") (pinfunction "-IN_6") (pintype "input"))
      (node (ref "R45") (pin "2") (pinfunction "2_2") (pintype "passive"))
    )
    (net (code "88") (name "Net-(C46-P$1)") (class "Default")
      (node (ref "C46") (pin "1") (pinfunction "P$1_1") (pintype "passive"))
      (node (ref "R45") (pin "1") (pinfunction "1_1") (pintype "passive"))
      (node (ref "R46") (pin "1") (pinfunction "1_1") (pintype "passive"))
      (node (ref "R47") (pin "1") (pinfunction "1_1") (pintype "passive"))
    )
    (net (code "89") (name "Net-(C47-Pad-)") (class "Default")
      (node (ref "C47") (pin "-") (pinfunction "-_-") (pintype "passive"))
      (node (ref "R47") (pin "2") (pinfunction "2_2") (pintype "passive"))
    )
    (net (code "90") (name "Net-(C50-P$2)") (class "Default")
      (node (ref "C50") (pin "2") (pinfunction "P$2_2") (pintype "passive"))
      (node (ref "JP1") (pin "1") (pinfunction "1_1") (pintype "passive"))
      (node (ref "R49") (pin "2") (pinfunction "2_2") (pintype "passive"))
      (node (ref "U1") (pin "3") (pinfunction "OUT_3") (pintype "passive"))
    )
    (net (code "91") (name "Net-(C51-P$2)") (class "Default")
      (node (ref "C51") (pin "2") (pinfunction "P$2_2") (pintype "passive"))
      (node (ref "JP6") (pin "1") (pinfunction "1_1") (pintype "passive"))
      (node (ref "L7") (pin "1") (pinfunction "1_1") (pintype "passive"))
    )
    (net (code "92") (name "Net-(C55-P$2)") (class "Default")
      (node (ref "C55") (pin "2") (pinfunction "P$2_2") (pintype "passive"))
      (node (ref "U3") (pin "106") (pinfunction "VCAP_2_106") (pintype "power_in"))
    )
    (net (code "93") (name "Net-(C56-P$2)") (class "Default")
      (node (ref "C56") (pin "2") (pinfunction "P$2_2") (pintype "passive"))
      (node (ref "U3") (pin "71") (pinfunction "VCAP_1_71") (pintype "power_in"))
    )
    (net (code "94") (name "Net-(C72-P$2)") (class "Default")
      (node (ref "C72") (pin "2") (pinfunction "P$2_2") (pintype "passive"))
      (node (ref "U3") (pin "76") (pinfunction "VDD12-OTGHS_76") (pintype "power_in"))
    )
    (net (code "95") (name "Net-(C78-P$2)") (class "Default")
      (node (ref "C78") (pin "2") (pinfunction "P$2_2") (pintype "passive"))
      (node (ref "R57") (pin "2") (pinfunction "2_2") (pintype "passive"))
      (node (ref "USB_FS") (pin "P$1") (pinfunction "S1_P$1") (pintype "passive"))
      (node (ref "USB_FS") (pin "P$2") (pinfunction "S2_P$2") (pintype "passive"))
    )
    (net (code "96") (name "Net-(C79-P$2)") (class "Default")
      (node (ref "C79") (pin "2") (pinfunction "P$2_2") (pintype "passive"))
      (node (ref "R58") (pin "2") (pinfunction "2_2") (pintype "passive"))
      (node (ref "USB_HS") (pin "M1") (pinfunction "S1_M1") (pintype "passive"))
      (node (ref "USB_HS") (pin "M2") (pinfunction "S2_M2") (pintype "passive"))
      (node (ref "USB_HS") (pin "M3") (pinfunction "S3_M3") (pintype "passive"))
      (node (ref "USB_HS") (pin "M4") (pinfunction "S4_M4") (pintype "passive"))
    )
    (net (code "97") (name "Net-(C84-P$2)") (class "Default")
      (node (ref "C83") (pin "+") (pinfunction "+_+") (pintype "passive"))
      (node (ref "C84") (pin "2") (pinfunction "P$2_2") (pintype "passive"))
      (node (ref "C85") (pin "2") (pinfunction "P$2_2") (pintype "passive"))
      (node (ref "C93") (pin "+") (pinfunction "+_+") (pintype "passive"))
      (node (ref "L3") (pin "2") (pinfunction "2_2") (pintype "passive"))
      (node (ref "U6") (pin "17") (pinfunction "VCC1_17") (pintype "power_in"))
      (node (ref "U6") (pin "23") (pinfunction "VCC2_23") (pintype "power_in"))
    )
    (net (code "98") (name "Net-(C90-P$2)") (class "Default")
      (node (ref "C89") (pin "+") (pinfunction "+_+") (pintype "passive"))
      (node (ref "C90") (pin "2") (pinfunction "P$2_2") (pintype "passive"))
      (node (ref "C91") (pin "2") (pinfunction "P$2_2") (pintype "passive"))
      (node (ref "C92") (pin "+") (pinfunction "+_+") (pintype "passive"))
      (node (ref "L4") (pin "2") (pinfunction "2_2") (pintype "passive"))
      (node (ref "U7") (pin "17") (pinfunction "VCC1_17") (pintype "power_in"))
      (node (ref "U7") (pin "23") (pinfunction "VCC2_23") (pintype "power_in"))
    )
    (net (code "99") (name "Net-(C96-P$1)") (class "Default")
      (node (ref "C96") (pin "1") (pinfunction "P$1_1") (pintype "passive"))
      (node (ref "D1") (pin "A") (pinfunction "A_A") (pintype "passive"))
      (node (ref "IC10") (pin "1") (pinfunction "ADJ_1") (pintype "bidirectional"))
      (node (ref "R94") (pin "1") (pinfunction "1_1") (pintype "passive"))
      (node (ref "R95") (pin "2") (pinfunction "2_2") (pintype "passive"))
    )
    (net (code "100") (name "Net-(C97-P$1)") (class "Default")
      (node (ref "C97") (pin "1") (pinfunction "P$1_1") (pintype "passive"))
      (node (ref "D1") (pin "C") (pinfunction "C_C") (pintype "passive"))
      (node (ref "D2") (pin "A") (pinfunction "A_A") (pintype "passive"))
      (node (ref "IC10") (pin "2") (pinfunction "OUT_2") (pintype "bidirectional"))
      (node (ref "IC10") (pin "4") (pinfunction "OUT_TAB_4") (pintype "bidirectional"))
      (node (ref "L5") (pin "1") (pinfunction "1_1") (pintype "passive"))
      (node (ref "R94") (pin "2") (pinfunction "2_2") (pintype "passive"))
    )
    (net (code "101") (name "Net-(C100-P$2)") (class "Default")
      (node (ref "C100") (pin "2") (pinfunction "P$2_2") (pintype "passive"))
      (node (ref "D4") (pin "C") (pinfunction "C_C") (pintype "passive"))
      (node (ref "IC11") (pin "1") (pinfunction "ADJ_1") (pintype "bidirectional"))
      (node (ref "R96") (pin "1") (pinfunction "1_1") (pintype "passive"))
      (node (ref "R97") (pin "2") (pinfunction "2_2") (pintype "passive"))
    )
    (net (code "102") (name "Net-(C101-P$2)") (class "Default")
      (node (ref "C101") (pin "2") (pinfunction "P$2_2") (pintype "passive"))
      (node (ref "D3") (pin "C") (pinfunction "C_C") (pintype "passive"))
      (node (ref "D4") (pin "A") (pinfunction "A_A") (pintype "passive"))
      (node (ref "IC11") (pin "3") (pinfunction "OUT_3") (pintype "bidirectional"))
      (node (ref "L6") (pin "1") (pinfunction "1_1") (pintype "passive"))
      (node (ref "R97") (pin "1") (pinfunction "1_1") (pintype "passive"))
    )
    (net (code "103") (name "Net-(JP1-Pad2)") (class "Default")
      (node (ref "JP1") (pin "2") (pinfunction "2_2") (pintype "passive"))
      (node (ref "L1") (pin "1") (pinfunction "1_1") (pintype "passive"))
      (node (ref "TP1") (pin "TP") (pinfunction "TP_TP") (pintype "input"))
    )
    (net (code "104") (name "Net-(JP3-Pad2)") (class "Default")
      (node (ref "JP3") (pin "2") (pinfunction "2_2") (pintype "passive"))
      (node (ref "R69") (pin "1") (pinfunction "1_1") (pintype "passive"))
    )
    (net (code "105") (name "Net-(JP4-Pad2)") (class "Default")
      (node (ref "JP4") (pin "2") (pinfunction "2_2") (pintype "passive"))
      (node (ref "R70") (pin "1") (pinfunction "1_1") (pintype "passive"))
    )
    (net (code "106") (name "Net-(JP5-Pad2)") (class "Default")
      (node (ref "JP5") (pin "2") (pinfunction "2_2") (pintype "passive"))
      (node (ref "R71") (pin "1") (pinfunction "1_1") (pintype "passive"))
    )
    (net (code "107") (name "Net-(JP6B-1)") (class "Default")
      (node (ref "JP6") (pin "3") (pinfunction "1_3") (pintype "passive"))
      (node (ref "U2") (pin "4") (pinfunction "-VOUT_4") (pintype "output"))
    )
    (net (code "108") (name "Net-(JP6C-1)") (class "Default")
      (node (ref "JP6") (pin "5") (pinfunction "1_5") (pintype "passive"))
      (node (ref "U2") (pin "5") (pinfunction "COMMON_5") (pintype "power_in"))
    )
    (net (code "109") (name "Net-(JP6D-1)") (class "Default")
      (node (ref "JP6") (pin "7") (pinfunction "1_7") (pintype "passive"))
      (node (ref "U2") (pin "6") (pinfunction "+VOUT_6") (pintype "output"))
    )
    (net (code "110") (name "Net-(JP8-Pad2)") (class "Default")
      (node (ref "JP8") (pin "2") (pinfunction "2_2") (pintype "passive"))
      (node (ref "R80") (pin "1") (pinfunction "1_1") (pintype "passive"))
    )
    (net (code "111") (name "Net-(JP9-Pad2)") (class "Default")
      (node (ref "JP9") (pin "2") (pinfunction "2_2") (pintype "passive"))
      (node (ref "R81") (pin "1") (pinfunction "1_1") (pintype "passive"))
    )
    (net (code "112") (name "Net-(JP10-Pad2)") (class "Default")
      (node (ref "JP10") (pin "2") (pinfunction "2_2") (pintype "passive"))
      (node (ref "R82") (pin "1") (pinfunction "1_1") (pintype "passive"))
    )
    (net (code "113") (name "Net-(LED1-A_1)") (class "Default")
      (node (ref "LED1") (pin "A1") (pinfunction "A_1_A1") (pintype "bidirectional"))
      (node (ref "R98") (pin "1") (pinfunction "1_1") (pintype "passive"))
    )
    (net (code "114") (name "Net-(LED1-A_2)") (class "Default")
      (node (ref "LED1") (pin "A2") (pinfunction "A_2_A2") (pintype "bidirectional"))
      (node (ref "R99") (pin "1") (pinfunction "1_1") (pintype "passive"))
    )
    (net (code "115") (name "Net-(LED1-A_3)") (class "Default")
      (node (ref "LED1") (pin "A3") (pinfunction "A_3_A3") (pintype "bidirectional"))
      (node (ref "R100") (pin "1") (pinfunction "1_1") (pintype "passive"))
    )
    (net (code "116") (name "Net-(LED2-PadA)") (class "Default")
      (node (ref "LED2") (pin "A") (pinfunction "A_A") (pintype "passive"))
      (node (ref "R49") (pin "1") (pinfunction "1_1") (pintype "passive"))
    )
    (net (code "117") (name "Net-(OSC1-INH)") (class "Default")
      (node (ref "OSC1") (pin "1") (pinfunction "INH_1") (pintype "bidirectional"))
      (node (ref "R55") (pin "1") (pinfunction "1_1") (pintype "passive"))
    )
    (net (code "118") (name "Net-(OSC1-OUT)") (class "Default")
      (node (ref "OSC1") (pin "3") (pinfunction "OUT_3") (pintype "output"))
      (node (ref "R56") (pin "1") (pinfunction "1_1") (pintype "passive"))
    )
    (net (code "119") (name "Net-(R61-Pad2)") (class "Default")
      (node (ref "R61") (pin "2") (pinfunction "2_2") (pintype "passive"))
      (node (ref "USB_FS") (pin "2") (pinfunction "2_2") (pintype "bidirectional"))
    )
    (net (code "120") (name "Net-(R62-Pad2)") (class "Default")
      (node (ref "R62") (pin "2") (pinfunction "2_2") (pintype "passive"))
      (node (ref "USB_FS") (pin "3") (pinfunction "3_3") (pintype "bidirectional"))
    )
    (net (code "121") (name "Net-(R101-Pad2)") (class "Default")
      (node (ref "R101") (pin "2") (pinfunction "2_2") (pintype "passive"))
      (node (ref "U$1") (pin "LED+") (pinfunction "LED+_LED+") (pintype "passive"))
    )
    (net (code "122") (name "Net-(U2-+VIN)") (class "Default")
      (node (ref "L7") (pin "2") (pinfunction "2_2") (pintype "passive"))
      (node (ref "U2") (pin "1") (pinfunction "+VIN_1") (pintype "input"))
    )
    (net (code "123") (name "Net-(U3A-BOOT0)") (class "Default")
      (node (ref "R51") (pin "1") (pinfunction "1_1") (pintype "passive"))
      (node (ref "R52") (pin "1") (pinfunction "1_1") (pintype "passive"))
      (node (ref "U3") (pin "138") (pinfunction "BOOT0_138") (pintype "input"))
    )
    (net (code "124") (name "Net-(U3A-OTG_HS_REXT)") (class "Default")
      (node (ref "R54") (pin "1") (pinfunction "1_1") (pintype "passive"))
      (node (ref "U3") (pin "75") (pinfunction "OTG_HS_REXT_75") (pintype "bidirectional"))
    )
    (net (code "125") (name "Net-(U3B-PE2)") (class "Default")
      (node (ref "R87") (pin "1") (pinfunction "1_1") (pintype "passive"))
      (node (ref "U3") (pin "1") (pinfunction "PE2_1") (pintype "bidirectional"))
    )
    (net (code "126") (name "Net-(U3B-PE3)") (class "Default")
      (node (ref "R88") (pin "1") (pinfunction "1_1") (pintype "passive"))
      (node (ref "U3") (pin "2") (pinfunction "PE3_2") (pintype "bidirectional"))
    )
    (net (code "127") (name "Net-(U3B-PE4)") (class "Default")
      (node (ref "R89") (pin "1") (pinfunction "1_1") (pintype "passive"))
      (node (ref "U3") (pin "3") (pinfunction "PE4_3") (pintype "bidirectional"))
    )
    (net (code "128") (name "Net-(U3B-PE5)") (class "Default")
      (node (ref "R90") (pin "1") (pinfunction "1_1") (pintype "passive"))
      (node (ref "U3") (pin "4") (pinfunction "PE5_4") (pintype "bidirectional"))
    )
    (net (code "129") (name "Net-(U3B-PE6)") (class "Default")
      (node (ref "R91") (pin "1") (pinfunction "1_1") (pintype "passive"))
      (node (ref "U3") (pin "5") (pinfunction "PE6_5") (pintype "bidirectional"))
    )
    (net (code "130") (name "Net-(U3C-PDR_ON)") (class "Default")
      (node (ref "R50") (pin "2") (pinfunction "2_2") (pintype "passive"))
      (node (ref "U3") (pin "143") (pinfunction "PDR_ON_143") (pintype "power_in"))
    )
    (net (code "131") (name "Net-(U4-I{slash}O1)") (class "Default")
      (node (ref "R62") (pin "1") (pinfunction "1_1") (pintype "passive"))
      (node (ref "U4") (pin "6") (pinfunction "I/O1_6") (pintype "bidirectional"))
    )
    (net (code "132") (name "Net-(U4-I{slash}O2)") (class "Default")
      (node (ref "R61") (pin "1") (pinfunction "1_1") (pintype "passive"))
      (node (ref "U4") (pin "4") (pinfunction "I/O2_4") (pintype "bidirectional"))
    )
    (net (code "133") (name "Net-(U5-I{slash}O1)") (class "Default")
      (node (ref "R60") (pin "1") (pinfunction "1_1") (pintype "passive"))
      (node (ref "U5") (pin "6") (pinfunction "I/O1_6") (pintype "bidirectional"))
    )
    (net (code "134") (name "Net-(U5-I{slash}O2)") (class "Default")
      (node (ref "R59") (pin "1") (pinfunction "1_1") (pintype "passive"))
      (node (ref "U5") (pin "4") (pinfunction "I/O2_4") (pintype "bidirectional"))
    )
    (net (code "135") (name "Net-(U6A-BCK)") (class "Default")
      (node (ref "R63") (pin "2") (pinfunction "2_2") (pintype "passive"))
      (node (ref "U6") (pin "7") (pinfunction "BCK_7") (pintype "input"))
    )
    (net (code "136") (name "Net-(U6A-DATA1)") (class "Default")
      (node (ref "R64") (pin "2") (pinfunction "2_2") (pintype "passive"))
      (node (ref "U6") (pin "6") (pinfunction "DATA1_6") (pintype "input"))
    )
    (net (code "137") (name "Net-(U6A-DATA2)") (class "Default")
      (node (ref "R65") (pin "2") (pinfunction "2_2") (pintype "passive"))
      (node (ref "U6") (pin "11") (pinfunction "DATA2_11") (pintype "input"))
    )
    (net (code "138") (name "Net-(U6A-DATA3)") (class "Default")
      (node (ref "R68") (pin "2") (pinfunction "2_2") (pintype "passive"))
      (node (ref "U6") (pin "12") (pinfunction "DATA3_12") (pintype "input"))
    )
    (net (code "139") (name "Net-(U6A-DATA4)") (class "Default")
      (node (ref "R72") (pin "2") (pinfunction "2_2") (pintype "passive"))
      (node (ref "U6") (pin "13") (pinfunction "DATA4_13") (pintype "input"))
    )
    (net (code "140") (name "Net-(U6A-LRCK)") (class "Default")
      (node (ref "R66") (pin "2") (pinfunction "2_2") (pintype "passive"))
      (node (ref "U6") (pin "8") (pinfunction "LRCK_8") (pintype "input"))
    )
    (net (code "141") (name "Net-(U6A-MC{slash}SCL{slash}DEMP)") (class "Default")
      (node (ref "R70") (pin "2") (pinfunction "2_2") (pintype "passive"))
      (node (ref "U6") (pin "3") (pinfunction "MC/SCL/DEMP_3") (pintype "input"))
    )
    (net (code "142") (name "Net-(U6A-MD{slash}SDA{slash}MUTE)") (class "Default")
      (node (ref "R71") (pin "2") (pinfunction "2_2") (pintype "passive"))
      (node (ref "U6") (pin "4") (pinfunction "MD/SDA/MUTE_4") (pintype "bidirectional"))
    )
    (net (code "143") (name "Net-(U6A-MSEL)") (class "Default")
      (node (ref "JP2") (pin "2") (pinfunction "2_2") (pintype "passive"))
      (node (ref "U6") (pin "14") (pinfunction "MSEL_14") (pintype "input"))
    )
    (net (code "144") (name "Net-(U6A-SCK)") (class "Default")
      (node (ref "R67") (pin "2") (pinfunction "2_2") (pintype "passive"))
      (node (ref "U6") (pin "5") (pinfunction "SCK_5") (pintype "input"))
    )
    (net (code "145") (name "Net-(U6A-ZR1{slash}ZR1{slash}FMT0)") (class "Default")
      (node (ref "R73") (pin "1") (pinfunction "1_1") (pintype "passive"))
      (node (ref "U6") (pin "1") (pinfunction "ZR1/ZR1/FMT0_1") (pintype "bidirectional"))
    )
    (net (code "146") (name "Net-(U6A-ZR2)") (class "Default")
      (node (ref "R74") (pin "1") (pinfunction "1_1") (pintype "passive"))
      (node (ref "U6") (pin "28") (pinfunction "ZR2_28") (pintype "output"))
    )
    (net (code "147") (name "Net-(U6A-~{MS{slash}ADR{slash}FMT1})") (class "Default")
      (node (ref "R69") (pin "2") (pinfunction "2_2") (pintype "passive"))
      (node (ref "U6") (pin "2") (pinfunction "~{MS/ADR/FMT1}_2") (pintype "input"))
    )
    (net (code "148") (name "Net-(U6B-VCOM)") (class "Default")
      (node (ref "C82") (pin "+") (pinfunction "+_+") (pintype "passive"))
      (node (ref "U6") (pin "25") (pinfunction "VCOM_25") (pintype "power_in"))
    )
    (net (code "149") (name "Net-(U7A-BCK)") (class "Default")
      (node (ref "R75") (pin "2") (pinfunction "2_2") (pintype "passive"))
      (node (ref "U7") (pin "7") (pinfunction "BCK_7") (pintype "input"))
    )
    (net (code "150") (name "Net-(U7A-DATA1)") (class "Default")
      (node (ref "R76") (pin "2") (pinfunction "2_2") (pintype "passive"))
      (node (ref "U7") (pin "6") (pinfunction "DATA1_6") (pintype "input"))
    )
    (net (code "151") (name "Net-(U7A-DATA2)") (class "Default")
      (node (ref "R77") (pin "2") (pinfunction "2_2") (pintype "passive"))
      (node (ref "U7") (pin "11") (pinfunction "DATA2_11") (pintype "input"))
    )
    (net (code "152") (name "Net-(U7A-DATA3)") (class "Default")
      (node (ref "R83") (pin "2") (pinfunction "2_2") (pintype "passive"))
      (node (ref "U7") (pin "12") (pinfunction "DATA3_12") (pintype "input"))
    )
    (net (code "153") (name "Net-(U7A-DATA4)") (class "Default")
      (node (ref "R84") (pin "2") (pinfunction "2_2") (pintype "passive"))
      (node (ref "U7") (pin "13") (pinfunction "DATA4_13") (pintype "input"))
    )
    (net (code "154") (name "Net-(U7A-LRCK)") (class "Default")
      (node (ref "R78") (pin "2") (pinfunction "2_2") (pintype "passive"))
      (node (ref "U7") (pin "8") (pinfunction "LRCK_8") (pintype "input"))
    )
    (net (code "155") (name "Net-(U7A-MC{slash}SCL{slash}DEMP)") (class "Default")
      (node (ref "R81") (pin "2") (pinfunction "2_2") (pintype "passive"))
      (node (ref "U7") (pin "3") (pinfunction "MC/SCL/DEMP_3") (pintype "input"))
    )
    (net (code "156") (name "Net-(U7A-MD{slash}SDA{slash}MUTE)") (class "Default")
      (node (ref "R82") (pin "2") (pinfunction "2_2") (pintype "passive"))
      (node (ref "U7") (pin "4") (pinfunction "MD/SDA/MUTE_4") (pintype "bidirectional"))
    )
    (net (code "157") (name "Net-(U7A-MSEL)") (class "Default")
      (node (ref "JP7") (pin "2") (pinfunction "2_2") (pintype "passive"))
      (node (ref "U7") (pin "14") (pinfunction "MSEL_14") (pintype "input"))
    )
    (net (code "158") (name "Net-(U7A-SCK)") (class "Default")
      (node (ref "R79") (pin "2") (pinfunction "2_2") (pintype "passive"))
      (node (ref "U7") (pin "5") (pinfunction "SCK_5") (pintype "input"))
    )
    (net (code "159") (name "Net-(U7A-VOUT5)") (class "Default")
      (node (ref "R102") (pin "1") (pinfunction "1_1") (pintype "passive"))
      (node (ref "U7") (pin "20") (pinfunction "VOUT5_20") (pintype "output"))
    )
    (net (code "160") (name "Net-(U7A-VOUT6)") (class "Default")
      (node (ref "R103") (pin "1") (pinfunction "1_1") (pintype "passive"))
      (node (ref "U7") (pin "19") (pinfunction "VOUT6_19") (pintype "output"))
    )
    (net (code "161") (name "Net-(U7A-VOUT7)") (class "Default")
      (node (ref "R104") (pin "1") (pinfunction "1_1") (pintype "passive"))
      (node (ref "U7") (pin "16") (pinfunction "VOUT7_16") (pintype "output"))
    )
    (net (code "162") (name "Net-(U7A-VOUT8)") (class "Default")
      (node (ref "R105") (pin "1") (pinfunction "1_1") (pintype "passive"))
      (node (ref "U7") (pin "15") (pinfunction "VOUT8_15") (pintype "output"))
    )
    (net (code "163") (name "Net-(U7A-ZR1{slash}ZR1{slash}FMT0)") (class "Default")
      (node (ref "R85") (pin "1") (pinfunction "1_1") (pintype "passive"))
      (node (ref "U7") (pin "1") (pinfunction "ZR1/ZR1/FMT0_1") (pintype "bidirectional"))
    )
    (net (code "164") (name "Net-(U7A-ZR2)") (class "Default")
      (node (ref "R86") (pin "1") (pinfunction "1_1") (pintype "passive"))
      (node (ref "U7") (pin "28") (pinfunction "ZR2_28") (pintype "output"))
    )
    (net (code "165") (name "Net-(U7A-~{MS{slash}ADR{slash}FMT1})") (class "Default")
      (node (ref "R80") (pin "2") (pinfunction "2_2") (pintype "passive"))
      (node (ref "U7") (pin "2") (pinfunction "~{MS/ADR/FMT1}_2") (pintype "input"))
    )
    (net (code "166") (name "Net-(U7B-VCOM)") (class "Default")
      (node (ref "C88") (pin "+") (pinfunction "+_+") (pintype "passive"))
      (node (ref "U7") (pin "25") (pinfunction "VCOM_25") (pintype "power_in"))
    )
    (net (code "167") (name "Net-(USB_HSB-2)") (class "Default")
      (node (ref "R59") (pin "2") (pinfunction "2_2") (pintype "passive"))
      (node (ref "USB_HS") (pin "P$2") (pinfunction "2_P$2") (pintype "passive"))
    )
    (net (code "168") (name "Net-(USB_HSB-3)") (class "Default")
      (node (ref "R60") (pin "2") (pinfunction "2_2") (pintype "passive"))
      (node (ref "USB_HS") (pin "P$3") (pinfunction "3_P$3") (pintype "passive"))
    )
    (net (code "169") (name "OSC_IN") (class "Default")
      (node (ref "C73") (pin "1") (pinfunction "P$1_1") (pintype "passive"))
      (node (ref "U3") (pin "23") (pinfunction "PH0-OSC_IN_23") (pintype "bidirectional"))
      (node (ref "Y1") (pin "1") (pinfunction "1_1") (pintype "passive"))
    )
    (net (code "170") (name "OSC_OUT") (class "Default")
      (node (ref "C74") (pin "2") (pinfunction "P$2_2") (pintype "passive"))
      (node (ref "U3") (pin "24") (pinfunction "PH1-OSC_OUT_24") (pintype "bidirectional"))
      (node (ref "Y1") (pin "2") (pinfunction "2_2") (pintype "passive"))
    )
    (net (code "171") (name "PUSHBTN") (class "Default")
      (node (ref "C102") (pin "1") (pinfunction "P$1_1") (pintype "passive"))
      (node (ref "U$1") (pin "P$2") (pinfunction "IN1_P$2") (pintype "passive"))
      (node (ref "U$1") (pin "P$5") (pinfunction "IN2_P$5") (pintype "passive"))
      (node (ref "U3") (pin "115") (pinfunction "PD1_115") (pintype "bidirectional"))
    )
    (net (code "172") (name "SAI_BCK") (class "Default")
      (node (ref "R63") (pin "1") (pinfunction "1_1") (pintype "passive"))
      (node (ref "R75") (pin "1") (pinfunction "1_1") (pintype "passive"))
      (node (ref "R90") (pin "2") (pinfunction "2_2") (pintype "passive"))
      (node (ref "TP9") (pin "TP") (pinfunction "TP_TP") (pintype "input"))
    )
    (net (code "173") (name "SAI_DATA1") (class "Default")
      (node (ref "R64") (pin "1") (pinfunction "1_1") (pintype "passive"))
      (node (ref "R91") (pin "2") (pinfunction "2_2") (pintype "passive"))
      (node (ref "TP10") (pin "TP") (pinfunction "TP_TP") (pintype "input"))
    )
    (net (code "174") (name "SAI_DATA2") (class "Default")
      (node (ref "R76") (pin "1") (pinfunction "1_1") (pintype "passive"))
      (node (ref "R88") (pin "2") (pinfunction "2_2") (pintype "passive"))
      (node (ref "TP7") (pin "TP") (pinfunction "TP_TP") (pintype "input"))
    )
    (net (code "175") (name "SAI_LRCK") (class "Default")
      (node (ref "R66") (pin "1") (pinfunction "1_1") (pintype "passive"))
      (node (ref "R78") (pin "1") (pinfunction "1_1") (pintype "passive"))
      (node (ref "R89") (pin "2") (pinfunction "2_2") (pintype "passive"))
      (node (ref "TP8") (pin "TP") (pinfunction "TP_TP") (pintype "input"))
    )
    (net (code "176") (name "SAI_MCLK") (class "Default")
      (node (ref "R67") (pin "1") (pinfunction "1_1") (pintype "passive"))
      (node (ref "R79") (pin "1") (pinfunction "1_1") (pintype "passive"))
      (node (ref "R87") (pin "2") (pinfunction "2_2") (pintype "passive"))
      (node (ref "TP6") (pin "TP") (pinfunction "TP_TP") (pintype "input"))
    )
    (net (code "177") (name "SPI_CLK") (class "Default")
      (node (ref "IC7") (pin "2") (pinfunction "SCK_2") (pintype "input"))
      (node (ref "JP4") (pin "1") (pinfunction "1_1") (pintype "passive"))
      (node (ref "JP9") (pin "1") (pinfunction "1_1") (pintype "passive"))
      (node (ref "TP13") (pin "TP") (pinfunction "TP_TP") (pintype "input"))
      (node (ref "U3") (pin "41") (pinfunction "PA5_41") (pintype "bidirectional"))
    )
    (net (code "178") (name "SPI_CS_DAC1") (class "Default")
      (node (ref "JP3") (pin "1") (pinfunction "1_1") (pintype "passive"))
      (node (ref "TP11") (pin "TP") (pinfunction "TP_TP") (pintype "input"))
      (node (ref "U3") (pin "37") (pinfunction "PA3_37") (pintype "bidirectional"))
    )
    (net (code "179") (name "SPI_CS_DAC2") (class "Default")
      (node (ref "JP8") (pin "1") (pinfunction "1_1") (pintype "passive"))
      (node (ref "TP12") (pin "TP") (pinfunction "TP_TP") (pintype "input"))
      (node (ref "U3") (pin "40") (pinfunction "PA4_40") (pintype "bidirectional"))
    )
    (net (code "180") (name "SPI_CS_FLASH") (class "Default")
      (node (ref "IC7") (pin "4") (pinfunction "~{CS}_4") (pintype "input"))
      (node (ref "U3") (pin "44") (pinfunction "PC4_44") (pintype "bidirectional"))
    )
    (net (code "181") (name "SPI_MISO") (class "Default")
      (node (ref "IC7") (pin "8") (pinfunction "SO_8") (pintype "output"))
      (node (ref "TP14") (pin "TP") (pinfunction "TP_TP") (pintype "input"))
      (node (ref "U3") (pin "42") (pinfunction "PA6_42") (pintype "bidirectional"))
    )
    (net (code "182") (name "SPI_MOSI") (class "Default")
      (node (ref "IC7") (pin "1") (pinfunction "SI_1") (pintype "input"))
      (node (ref "JP10") (pin "1") (pinfunction "1_1") (pintype "passive"))
      (node (ref "JP5") (pin "1") (pinfunction "1_1") (pintype "passive"))
      (node (ref "TP15") (pin "TP") (pinfunction "TP_TP") (pintype "input"))
      (node (ref "U3") (pin "43") (pinfunction "PA7_43") (pintype "bidirectional"))
    )
    (net (code "183") (name "SWCLK") (class "Default")
      (node (ref "TC1") (pin "4") (pinfunction "4_4") (pintype "passive"))
      (node (ref "U3") (pin "109") (pinfunction "PA14_109") (pintype "bidirectional"))
    )
    (net (code "184") (name "SWDIO") (class "Default")
      (node (ref "TC1") (pin "2") (pinfunction "2_2") (pintype "passive"))
      (node (ref "U3") (pin "105") (pinfunction "PA13_105") (pintype "bidirectional"))
    )
    (net (code "185") (name "SWO") (class "Default")
      (node (ref "TC1") (pin "6") (pinfunction "6_6") (pintype "passive"))
      (node (ref "U3") (pin "133") (pinfunction "PB3_133") (pintype "bidirectional"))
    )
    (net (code "186") (name "UART_RX") (class "Default")
      (node (ref "TC1") (pin "8") (pinfunction "8_8") (pintype "passive"))
      (node (ref "U3") (pin "122") (pinfunction "PD6_122") (pintype "bidirectional"))
    )
    (net (code "187") (name "UART_TX") (class "Default")
      (node (ref "TC1") (pin "7") (pinfunction "7_7") (pintype "passive"))
      (node (ref "U3") (pin "119") (pinfunction "PD5_119") (pintype "bidirectional"))
    )
    (net (code "188") (name "USB_FS_N") (class "Default")
      (node (ref "U3") (pin "103") (pinfunction "PA11_103") (pintype "bidirectional"))
      (node (ref "U4") (pin "3") (pinfunction "I/O2_2_3") (pintype "bidirectional"))
    )
    (net (code "189") (name "USB_FS_P") (class "Default")
      (node (ref "U3") (pin "104") (pinfunction "PA12_104") (pintype "bidirectional"))
      (node (ref "U4") (pin "1") (pinfunction "I/O1_2_1") (pintype "bidirectional"))
    )
    (net (code "190") (name "USB_HS_N") (class "Default")
      (node (ref "U3") (pin "77") (pinfunction "PB14_77") (pintype "bidirectional"))
      (node (ref "U5") (pin "3") (pinfunction "I/O2_2_3") (pintype "bidirectional"))
    )
    (net (code "191") (name "USB_HS_P") (class "Default")
      (node (ref "U3") (pin "78") (pinfunction "PB15_78") (pintype "bidirectional"))
      (node (ref "U5") (pin "1") (pinfunction "I/O1_2_1") (pintype "bidirectional"))
    )
    (net (code "192") (name "unconnected-(PL1-G-Pad7)") (class "Default")
      (node (ref "PL1") (pin "7") (pinfunction "G_7") (pintype "bidirectional"))
    )
    (net (code "193") (name "unconnected-(PL1-RNB-Pad4)") (class "Default")
      (node (ref "PL1") (pin "4") (pinfunction "RNB_4") (pintype "bidirectional"))
    )
    (net (code "194") (name "unconnected-(PL1-RNT-Pad3)") (class "Default")
      (node (ref "PL1") (pin "3") (pinfunction "RNT_3") (pintype "bidirectional"))
    )
    (net (code "195") (name "unconnected-(PL1-SNB-Pad6)") (class "Default")
      (node (ref "PL1") (pin "6") (pinfunction "SNB_6") (pintype "bidirectional"))
    )
    (net (code "196") (name "unconnected-(PL1-SNT-Pad5)") (class "Default")
      (node (ref "PL1") (pin "5") (pinfunction "SNT_5") (pintype "bidirectional"))
    )
    (net (code "197") (name "unconnected-(PL1-TNB-Pad2)") (class "Default")
      (node (ref "PL1") (pin "2") (pinfunction "TNB_2") (pintype "bidirectional"))
    )
    (net (code "198") (name "unconnected-(PL1-TNT-Pad1)") (class "Default")
      (node (ref "PL1") (pin "1") (pinfunction "TNT_1") (pintype "bidirectional"))
    )
    (net (code "199") (name "unconnected-(PL2-G-Pad7)") (class "Default")
      (node (ref "PL2") (pin "7") (pinfunction "G_7") (pintype "bidirectional"))
    )
    (net (code "200") (name "unconnected-(PL2-RNB-Pad4)") (class "Default")
      (node (ref "PL2") (pin "4") (pinfunction "RNB_4") (pintype "bidirectional"))
    )
    (net (code "201") (name "unconnected-(PL2-RNT-Pad3)") (class "Default")
      (node (ref "PL2") (pin "3") (pinfunction "RNT_3") (pintype "bidirectional"))
    )
    (net (code "202") (name "unconnected-(PL2-SNB-Pad6)") (class "Default")
      (node (ref "PL2") (pin "6") (pinfunction "SNB_6") (pintype "bidirectional"))
    )
    (net (code "203") (name "unconnected-(PL2-SNT-Pad5)") (class "Default")
      (node (ref "PL2") (pin "5") (pinfunction "SNT_5") (pintype "bidirectional"))
    )
    (net (code "204") (name "unconnected-(PL2-TNB-Pad2)") (class "Default")
      (node (ref "PL2") (pin "2") (pinfunction "TNB_2") (pintype "bidirectional"))
    )
    (net (code "205") (name "unconnected-(PL2-TNT-Pad1)") (class "Default")
      (node (ref "PL2") (pin "1") (pinfunction "TNT_1") (pintype "bidirectional"))
    )
    (net (code "206") (name "unconnected-(PL3-G-Pad7)") (class "Default")
      (node (ref "PL3") (pin "7") (pinfunction "G_7") (pintype "bidirectional"))
    )
    (net (code "207") (name "unconnected-(PL3-RNB-Pad4)") (class "Default")
      (node (ref "PL3") (pin "4") (pinfunction "RNB_4") (pintype "bidirectional"))
    )
    (net (code "208") (name "unconnected-(PL3-RNT-Pad3)") (class "Default")
      (node (ref "PL3") (pin "3") (pinfunction "RNT_3") (pintype "bidirectional"))
    )
    (net (code "209") (name "unconnected-(PL3-SNB-Pad6)") (class "Default")
      (node (ref "PL3") (pin "6") (pinfunction "SNB_6") (pintype "bidirectional"))
    )
    (net (code "210") (name "unconnected-(PL3-SNT-Pad5)") (class "Default")
      (node (ref "PL3") (pin "5") (pinfunction "SNT_5") (pintype "bidirectional"))
    )
    (net (code "211") (name "unconnected-(PL3-TNB-Pad2)") (class "Default")
      (node (ref "PL3") (pin "2") (pinfunction "TNB_2") (pintype "bidirectional"))
    )
    (net (code "212") (name "unconnected-(PL3-TNT-Pad1)") (class "Default")
      (node (ref "PL3") (pin "1") (pinfunction "TNT_1") (pintype "bidirectional"))
    )
    (net (code "213") (name "unconnected-(PL4-G-Pad7)") (class "Default")
      (node (ref "PL4") (pin "7") (pinfunction "G_7") (pintype "bidirectional"))
    )
    (net (code "214") (name "unconnected-(PL4-RNB-Pad4)") (class "Default")
      (node (ref "PL4") (pin "4") (pinfunction "RNB_4") (pintype "bidirectional"))
    )
    (net (code "215") (name "unconnected-(PL4-RNT-Pad3)") (class "Default")
      (node (ref "PL4") (pin "3") (pinfunction "RNT_3") (pintype "bidirectional"))
    )
    (net (code "216") (name "unconnected-(PL4-SNB-Pad6)") (class "Default")
      (node (ref "PL4") (pin "6") (pinfunction "SNB_6") (pintype "bidirectional"))
    )
    (net (code "217") (name "unconnected-(PL4-SNT-Pad5)") (class "Default")
      (node (ref "PL4") (pin "5") (pinfunction "SNT_5") (pintype "bidirectional"))
    )
    (net (code "218") (name "unconnected-(PL4-TNB-Pad2)") (class "Default")
      (node (ref "PL4") (pin "2") (pinfunction "TNB_2") (pintype "bidirectional"))
    )
    (net (code "219") (name "unconnected-(PL4-TNT-Pad1)") (class "Default")
      (node (ref "PL4") (pin "1") (pinfunction "TNT_1") (pintype "bidirectional"))
    )
    (net (code "220") (name "unconnected-(PL5-G-Pad7)") (class "Default")
      (node (ref "PL5") (pin "7") (pinfunction "G_7") (pintype "bidirectional"))
    )
    (net (code "221") (name "unconnected-(PL5-RNB-Pad4)") (class "Default")
      (node (ref "PL5") (pin "4") (pinfunction "RNB_4") (pintype "bidirectional"))
    )
    (net (code "222") (name "unconnected-(PL5-RNT-Pad3)") (class "Default")
      (node (ref "PL5") (pin "3") (pinfunction "RNT_3") (pintype "bidirectional"))
    )
    (net (code "223") (name "unconnected-(PL5-SNB-Pad6)") (class "Default")
      (node (ref "PL5") (pin "6") (pinfunction "SNB_6") (pintype "bidirectional"))
    )
    (net (code "224") (name "unconnected-(PL5-SNT-Pad5)") (class "Default")
      (node (ref "PL5") (pin "5") (pinfunction "SNT_5") (pintype "bidirectional"))
    )
    (net (code "225") (name "unconnected-(PL5-TNB-Pad2)") (class "Default")
      (node (ref "PL5") (pin "2") (pinfunction "TNB_2") (pintype "bidirectional"))
    )
    (net (code "226") (name "unconnected-(PL5-TNT-Pad1)") (class "Default")
      (node (ref "PL5") (pin "1") (pinfunction "TNT_1") (pintype "bidirectional"))
    )
    (net (code "227") (name "unconnected-(PL6-G-Pad7)") (class "Default")
      (node (ref "PL6") (pin "7") (pinfunction "G_7") (pintype "bidirectional"))
    )
    (net (code "228") (name "unconnected-(PL6-RNB-Pad4)") (class "Default")
      (node (ref "PL6") (pin "4") (pinfunction "RNB_4") (pintype "bidirectional"))
    )
    (net (code "229") (name "unconnected-(PL6-RNT-Pad3)") (class "Default")
      (node (ref "PL6") (pin "3") (pinfunction "RNT_3") (pintype "bidirectional"))
    )
    (net (code "230") (name "unconnected-(PL6-SNB-Pad6)") (class "Default")
      (node (ref "PL6") (pin "6") (pinfunction "SNB_6") (pintype "bidirectional"))
    )
    (net (code "231") (name "unconnected-(PL6-SNT-Pad5)") (class "Default")
      (node (ref "PL6") (pin "5") (pinfunction "SNT_5") (pintype "bidirectional"))
    )
    (net (code "232") (name "unconnected-(PL6-TNB-Pad2)") (class "Default")
      (node (ref "PL6") (pin "2") (pinfunction "TNB_2") (pintype "bidirectional"))
    )
    (net (code "233") (name "unconnected-(PL6-TNT-Pad1)") (class "Default")
      (node (ref "PL6") (pin "1") (pinfunction "TNT_1") (pintype "bidirectional"))
    )
    (net (code "234") (name "unconnected-(U$1-OUT1_NC-PadP$1)") (class "Default")
      (node (ref "U$1") (pin "P$1") (pinfunction "OUT1_NC_P$1") (pintype "passive"))
    )
    (net (code "235") (name "unconnected-(U$1-OUT2_NC-PadP$4)") (class "Default")
      (node (ref "U$1") (pin "P$4") (pinfunction "OUT2_NC_P$4") (pintype "passive"))
    )
    (net (code "236") (name "unconnected-(U3A-PA0-WKUP-Pad34)") (class "Default")
      (node (ref "U3") (pin "34") (pinfunction "PA0-WKUP_34") (pintype "bidirectional"))
    )
    (net (code "237") (name "unconnected-(U3A-PA1-Pad35)") (class "Default")
      (node (ref "U3") (pin "35") (pinfunction "PA1_35") (pintype "bidirectional"))
    )
    (net (code "238") (name "unconnected-(U3A-PA2-Pad36)") (class "Default")
      (node (ref "U3") (pin "36") (pinfunction "PA2_36") (pintype "bidirectional"))
    )
    (net (code "239") (name "unconnected-(U3A-PA8-Pad100)") (class "Default")
      (node (ref "U3") (pin "100") (pinfunction "PA8_100") (pintype "bidirectional"))
    )
    (net (code "240") (name "unconnected-(U3A-PA10-Pad102)") (class "Default")
      (node (ref "U3") (pin "102") (pinfunction "PA10_102") (pintype "bidirectional"))
    )
    (net (code "241") (name "unconnected-(U3A-PA15-Pad110)") (class "Default")
      (node (ref "U3") (pin "110") (pinfunction "PA15_110") (pintype "bidirectional"))
    )
    (net (code "242") (name "unconnected-(U3A-PB0-Pad46)") (class "Default")
      (node (ref "U3") (pin "46") (pinfunction "PB0_46") (pintype "bidirectional"))
    )
    (net (code "243") (name "unconnected-(U3A-PB1-Pad47)") (class "Default")
      (node (ref "U3") (pin "47") (pinfunction "PB1_47") (pintype "bidirectional"))
    )
    (net (code "244") (name "unconnected-(U3A-PB2-Pad48)") (class "Default")
      (node (ref "U3") (pin "48") (pinfunction "PB2_48") (pintype "bidirectional"))
    )
    (net (code "245") (name "unconnected-(U3A-PB4-Pad134)") (class "Default")
      (node (ref "U3") (pin "134") (pinfunction "PB4_134") (pintype "bidirectional"))
    )
    (net (code "246") (name "unconnected-(U3A-PB5-Pad135)") (class "Default")
      (node (ref "U3") (pin "135") (pinfunction "PB5_135") (pintype "bidirectional"))
    )
    (net (code "247") (name "unconnected-(U3A-PB6-Pad136)") (class "Default")
      (node (ref "U3") (pin "136") (pinfunction "PB6_136") (pintype "bidirectional"))
    )
    (net (code "248") (name "unconnected-(U3A-PB9-Pad140)") (class "Default")
      (node (ref "U3") (pin "140") (pinfunction "PB9_140") (pintype "bidirectional"))
    )
    (net (code "249") (name "unconnected-(U3A-PB10-Pad69)") (class "Default")
      (node (ref "U3") (pin "69") (pinfunction "PB10_69") (pintype "bidirectional"))
    )
    (net (code "250") (name "unconnected-(U3A-PB11-Pad70)") (class "Default")
      (node (ref "U3") (pin "70") (pinfunction "PB11_70") (pintype "bidirectional"))
    )
    (net (code "251") (name "unconnected-(U3A-PB12-Pad73)") (class "Default")
      (node (ref "U3") (pin "73") (pinfunction "PB12_73") (pintype "bidirectional"))
    )
    (net (code "252") (name "unconnected-(U3A-PC0-Pad26)") (class "Default")
      (node (ref "U3") (pin "26") (pinfunction "PC0_26") (pintype "bidirectional"))
    )
    (net (code "253") (name "unconnected-(U3A-PC1-Pad27)") (class "Default")
      (node (ref "U3") (pin "27") (pinfunction "PC1_27") (pintype "bidirectional"))
    )
    (net (code "254") (name "unconnected-(U3A-PC2-Pad28)") (class "Default")
      (node (ref "U3") (pin "28") (pinfunction "PC2_28") (pintype "bidirectional"))
    )
    (net (code "255") (name "unconnected-(U3A-PC3-Pad29)") (class "Default")
      (node (ref "U3") (pin "29") (pinfunction "PC3_29") (pintype "bidirectional"))
    )
    (net (code "256") (name "unconnected-(U3A-PC5-Pad45)") (class "Default")
      (node (ref "U3") (pin "45") (pinfunction "PC5_45") (pintype "bidirectional"))
    )
    (net (code "257") (name "unconnected-(U3A-PC6-Pad96)") (class "Default")
      (node (ref "U3") (pin "96") (pinfunction "PC6_96") (pintype "bidirectional"))
    )
    (net (code "258") (name "unconnected-(U3A-PC7-Pad97)") (class "Default")
      (node (ref "U3") (pin "97") (pinfunction "PC7_97") (pintype "bidirectional"))
    )
    (net (code "259") (name "unconnected-(U3A-PC8-Pad98)") (class "Default")
      (node (ref "U3") (pin "98") (pinfunction "PC8_98") (pintype "bidirectional"))
    )
    (net (code "260") (name "unconnected-(U3A-PC13-Pad7)") (class "Default")
      (node (ref "U3") (pin "7") (pinfunction "PC13_7") (pintype "bidirectional"))
    )
    (net (code "261") (name "unconnected-(U3A-PC14-OSC32_IN-Pad8)") (class "Default")
      (node (ref "U3") (pin "8") (pinfunction "PC14-OSC32_IN_8") (pintype "bidirectional"))
    )
    (net (code "262") (name "unconnected-(U3A-PC15-OSC32_OUT-Pad9)") (class "Default")
      (node (ref "U3") (pin "9") (pinfunction "PC15-OSC32_OUT_9") (pintype "bidirectional"))
    )
    (net (code "263") (name "unconnected-(U3A-PD2-Pad116)") (class "Default")
      (node (ref "U3") (pin "116") (pinfunction "PD2_116") (pintype "bidirectional"))
    )
    (net (code "264") (name "unconnected-(U3A-PD3-Pad117)") (class "Default")
      (node (ref "U3") (pin "117") (pinfunction "PD3_117") (pintype "bidirectional"))
    )
    (net (code "265") (name "unconnected-(U3A-PD4-Pad118)") (class "Default")
      (node (ref "U3") (pin "118") (pinfunction "PD4_118") (pintype "bidirectional"))
    )
    (net (code "266") (name "unconnected-(U3A-PD7-Pad123)") (class "Default")
      (node (ref "U3") (pin "123") (pinfunction "PD7_123") (pintype "bidirectional"))
    )
    (net (code "267") (name "unconnected-(U3A-PD8-Pad79)") (class "Default")
      (node (ref "U3") (pin "79") (pinfunction "PD8_79") (pintype "bidirectional"))
    )
    (net (code "268") (name "unconnected-(U3A-PD9-Pad80)") (class "Default")
      (node (ref "U3") (pin "80") (pinfunction "PD9_80") (pintype "bidirectional"))
    )
    (net (code "269") (name "unconnected-(U3A-PD10-Pad81)") (class "Default")
      (node (ref "U3") (pin "81") (pinfunction "PD10_81") (pintype "bidirectional"))
    )
    (net (code "270") (name "unconnected-(U3A-PD11-Pad82)") (class "Default")
      (node (ref "U3") (pin "82") (pinfunction "PD11_82") (pintype "bidirectional"))
    )
    (net (code "271") (name "unconnected-(U3A-PD12-Pad83)") (class "Default")
      (node (ref "U3") (pin "83") (pinfunction "PD12_83") (pintype "bidirectional"))
    )
    (net (code "272") (name "unconnected-(U3A-PD13-Pad84)") (class "Default")
      (node (ref "U3") (pin "84") (pinfunction "PD13_84") (pintype "bidirectional"))
    )
    (net (code "273") (name "unconnected-(U3A-PD14-Pad87)") (class "Default")
      (node (ref "U3") (pin "87") (pinfunction "PD14_87") (pintype "bidirectional"))
    )
    (net (code "274") (name "unconnected-(U3A-PD15-Pad88)") (class "Default")
      (node (ref "U3") (pin "88") (pinfunction "PD15_88") (pintype "bidirectional"))
    )
    (net (code "275") (name "unconnected-(U3B-PE0-Pad141)") (class "Default")
      (node (ref "U3") (pin "141") (pinfunction "PE0_141") (pintype "bidirectional"))
    )
    (net (code "276") (name "unconnected-(U3B-PE1-Pad142)") (class "Default")
      (node (ref "U3") (pin "142") (pinfunction "PE1_142") (pintype "bidirectional"))
    )
    (net (code "277") (name "unconnected-(U3B-PE7-Pad58)") (class "Default")
      (node (ref "U3") (pin "58") (pinfunction "PE7_58") (pintype "bidirectional"))
    )
    (net (code "278") (name "unconnected-(U3B-PE8-Pad59)") (class "Default")
      (node (ref "U3") (pin "59") (pinfunction "PE8_59") (pintype "bidirectional"))
    )
    (net (code "279") (name "unconnected-(U3B-PE9-Pad60)") (class "Default")
      (node (ref "U3") (pin "60") (pinfunction "PE9_60") (pintype "bidirectional"))
    )
    (net (code "280") (name "unconnected-(U3B-PE10-Pad63)") (class "Default")
      (node (ref "U3") (pin "63") (pinfunction "PE10_63") (pintype "bidirectional"))
    )
    (net (code "281") (name "unconnected-(U3B-PE11-Pad64)") (class "Default")
      (node (ref "U3") (pin "64") (pinfunction "PE11_64") (pintype "bidirectional"))
    )
    (net (code "282") (name "unconnected-(U3B-PE12-Pad65)") (class "Default")
      (node (ref "U3") (pin "65") (pinfunction "PE12_65") (pintype "bidirectional"))
    )
    (net (code "283") (name "unconnected-(U3B-PE13-Pad66)") (class "Default")
      (node (ref "U3") (pin "66") (pinfunction "PE13_66") (pintype "bidirectional"))
    )
    (net (code "284") (name "unconnected-(U3B-PE14-Pad67)") (class "Default")
      (node (ref "U3") (pin "67") (pinfunction "PE14_67") (pintype "bidirectional"))
    )
    (net (code "285") (name "unconnected-(U3B-PE15-Pad68)") (class "Default")
      (node (ref "U3") (pin "68") (pinfunction "PE15_68") (pintype "bidirectional"))
    )
    (net (code "286") (name "unconnected-(U3B-PF0-Pad10)") (class "Default")
      (node (ref "U3") (pin "10") (pinfunction "PF0_10") (pintype "bidirectional"))
    )
    (net (code "287") (name "unconnected-(U3B-PF1-Pad11)") (class "Default")
      (node (ref "U3") (pin "11") (pinfunction "PF1_11") (pintype "bidirectional"))
    )
    (net (code "288") (name "unconnected-(U3B-PF2-Pad12)") (class "Default")
      (node (ref "U3") (pin "12") (pinfunction "PF2_12") (pintype "bidirectional"))
    )
    (net (code "289") (name "unconnected-(U3B-PF3-Pad13)") (class "Default")
      (node (ref "U3") (pin "13") (pinfunction "PF3_13") (pintype "bidirectional"))
    )
    (net (code "290") (name "unconnected-(U3B-PF4-Pad14)") (class "Default")
      (node (ref "U3") (pin "14") (pinfunction "PF4_14") (pintype "bidirectional"))
    )
    (net (code "291") (name "unconnected-(U3B-PF5-Pad15)") (class "Default")
      (node (ref "U3") (pin "15") (pinfunction "PF5_15") (pintype "bidirectional"))
    )
    (net (code "292") (name "unconnected-(U3B-PF6-Pad18)") (class "Default")
      (node (ref "U3") (pin "18") (pinfunction "PF6_18") (pintype "bidirectional"))
    )
    (net (code "293") (name "unconnected-(U3B-PF7-Pad19)") (class "Default")
      (node (ref "U3") (pin "19") (pinfunction "PF7_19") (pintype "bidirectional"))
    )
    (net (code "294") (name "unconnected-(U3B-PF8-Pad20)") (class "Default")
      (node (ref "U3") (pin "20") (pinfunction "PF8_20") (pintype "bidirectional"))
    )
    (net (code "295") (name "unconnected-(U3B-PF9-Pad21)") (class "Default")
      (node (ref "U3") (pin "21") (pinfunction "PF9_21") (pintype "bidirectional"))
    )
    (net (code "296") (name "unconnected-(U3B-PF10-Pad22)") (class "Default")
      (node (ref "U3") (pin "22") (pinfunction "PF10_22") (pintype "bidirectional"))
    )
    (net (code "297") (name "unconnected-(U3B-PF11-Pad49)") (class "Default")
      (node (ref "U3") (pin "49") (pinfunction "PF11_49") (pintype "bidirectional"))
    )
    (net (code "298") (name "unconnected-(U3B-PF12-Pad50)") (class "Default")
      (node (ref "U3") (pin "50") (pinfunction "PF12_50") (pintype "bidirectional"))
    )
    (net (code "299") (name "unconnected-(U3B-PF13-Pad53)") (class "Default")
      (node (ref "U3") (pin "53") (pinfunction "PF13_53") (pintype "bidirectional"))
    )
    (net (code "300") (name "unconnected-(U3B-PF14-Pad54)") (class "Default")
      (node (ref "U3") (pin "54") (pinfunction "PF14_54") (pintype "bidirectional"))
    )
    (net (code "301") (name "unconnected-(U3B-PF15-Pad55)") (class "Default")
      (node (ref "U3") (pin "55") (pinfunction "PF15_55") (pintype "bidirectional"))
    )
    (net (code "302") (name "unconnected-(U3B-PG0-Pad56)") (class "Default")
      (node (ref "U3") (pin "56") (pinfunction "PG0_56") (pintype "bidirectional"))
    )
    (net (code "303") (name "unconnected-(U3B-PG1-Pad57)") (class "Default")
      (node (ref "U3") (pin "57") (pinfunction "PG1_57") (pintype "bidirectional"))
    )
    (net (code "304") (name "unconnected-(U3B-PG2-Pad89)") (class "Default")
      (node (ref "U3") (pin "89") (pinfunction "PG2_89") (pintype "bidirectional"))
    )
    (net (code "305") (name "unconnected-(U3B-PG3-Pad90)") (class "Default")
      (node (ref "U3") (pin "90") (pinfunction "PG3_90") (pintype "bidirectional"))
    )
    (net (code "306") (name "unconnected-(U3B-PG4-Pad91)") (class "Default")
      (node (ref "U3") (pin "91") (pinfunction "PG4_91") (pintype "bidirectional"))
    )
    (net (code "307") (name "unconnected-(U3B-PG5-Pad92)") (class "Default")
      (node (ref "U3") (pin "92") (pinfunction "PG5_92") (pintype "bidirectional"))
    )
    (net (code "308") (name "unconnected-(U3B-PG8-Pad93)") (class "Default")
      (node (ref "U3") (pin "93") (pinfunction "PG8_93") (pintype "bidirectional"))
    )
    (net (code "309") (name "unconnected-(U3B-PG9-Pad124)") (class "Default")
      (node (ref "U3") (pin "124") (pinfunction "PG9_124") (pintype "bidirectional"))
    )
    (net (code "310") (name "unconnected-(U3B-PG10-Pad125)") (class "Default")
      (node (ref "U3") (pin "125") (pinfunction "PG10_125") (pintype "bidirectional"))
    )
    (net (code "311") (name "unconnected-(U3B-PG11-Pad126)") (class "Default")
      (node (ref "U3") (pin "126") (pinfunction "PG11_126") (pintype "bidirectional"))
    )
    (net (code "312") (name "unconnected-(U3B-PG12-Pad127)") (class "Default")
      (node (ref "U3") (pin "127") (pinfunction "PG12_127") (pintype "bidirectional"))
    )
    (net (code "313") (name "unconnected-(U3B-PG13-Pad128)") (class "Default")
      (node (ref "U3") (pin "128") (pinfunction "PG13_128") (pintype "bidirectional"))
    )
    (net (code "314") (name "unconnected-(U3B-PG14-Pad129)") (class "Default")
      (node (ref "U3") (pin "129") (pinfunction "PG14_129") (pintype "bidirectional"))
    )
    (net (code "315") (name "unconnected-(U3B-PG15-Pad132)") (class "Default")
      (node (ref "U3") (pin "132") (pinfunction "PG15_132") (pintype "bidirectional"))
    )
  )
)
